# PinHeck_Test_Jig.net
KiCad netlist of a schematic drawn in EAGLE
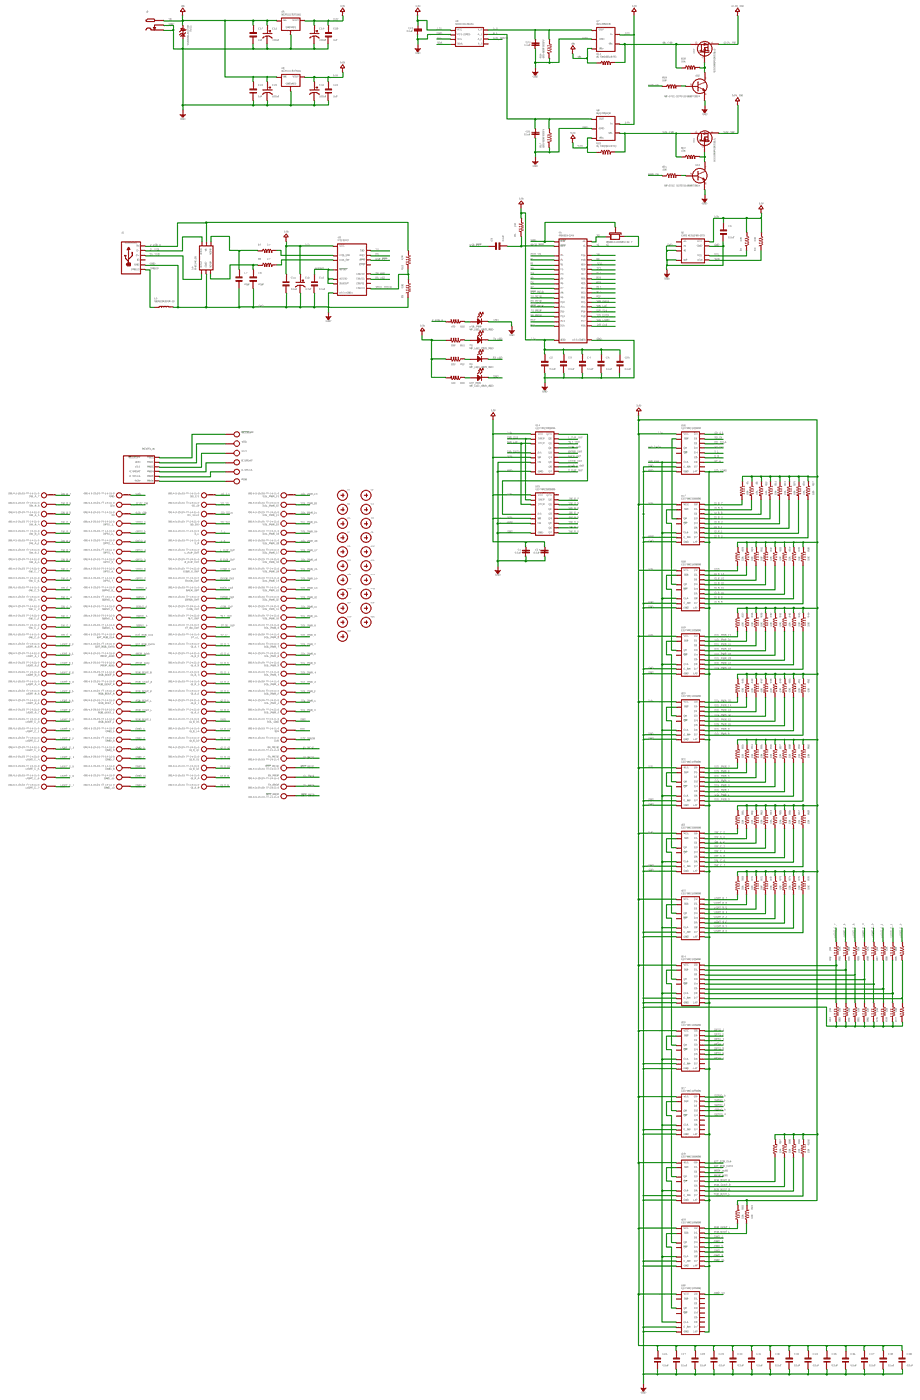
[diagram p0: schematic, sheet 1, overview]
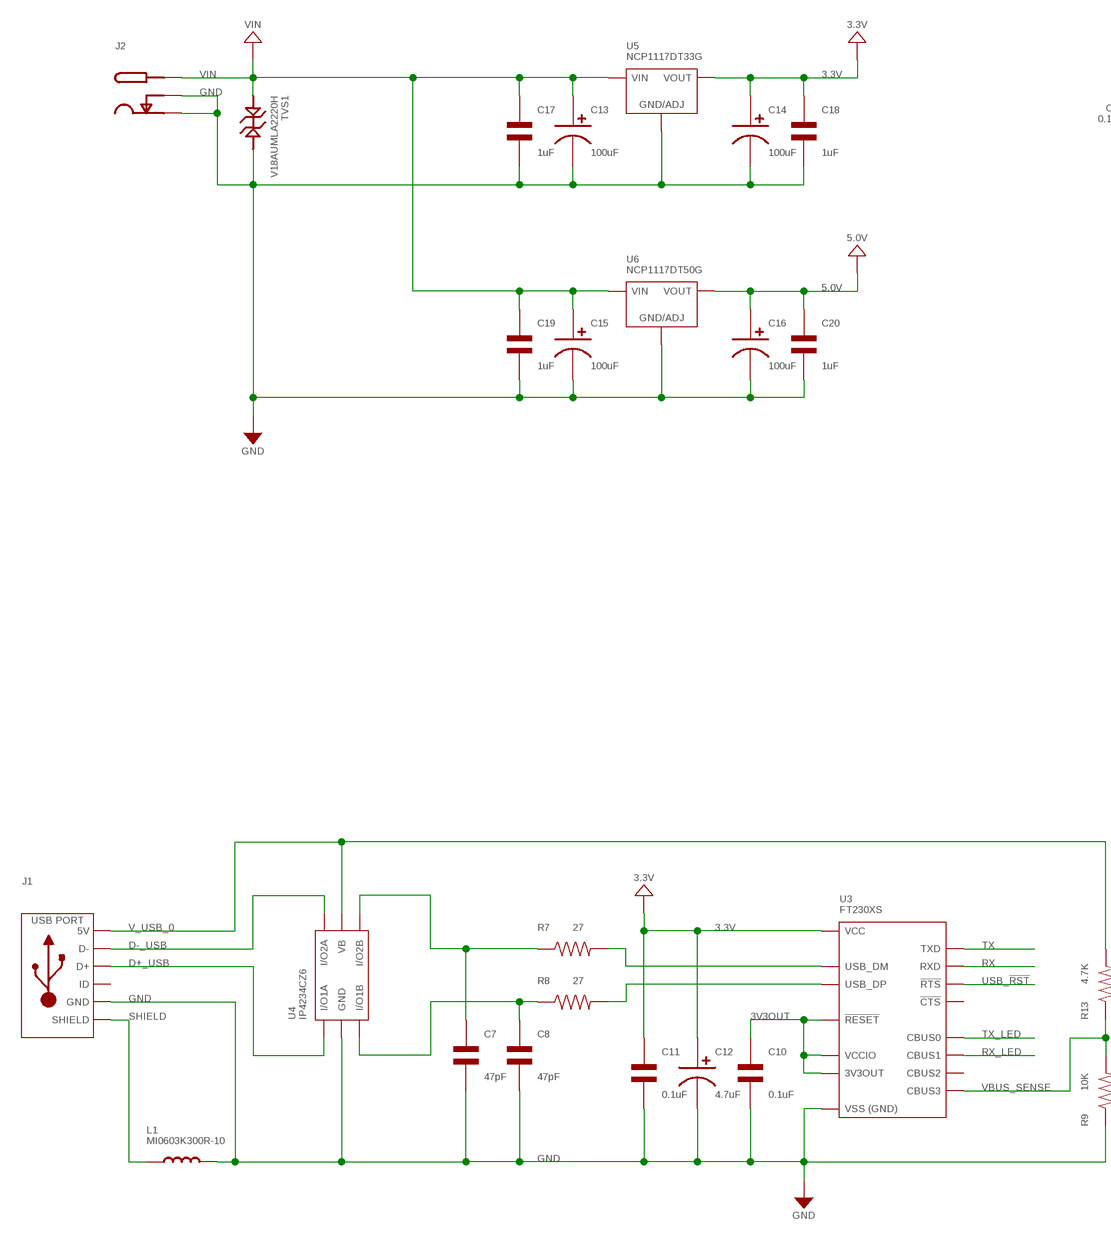
[diagram p1: schematic, sheet 1, part 1 of 7]
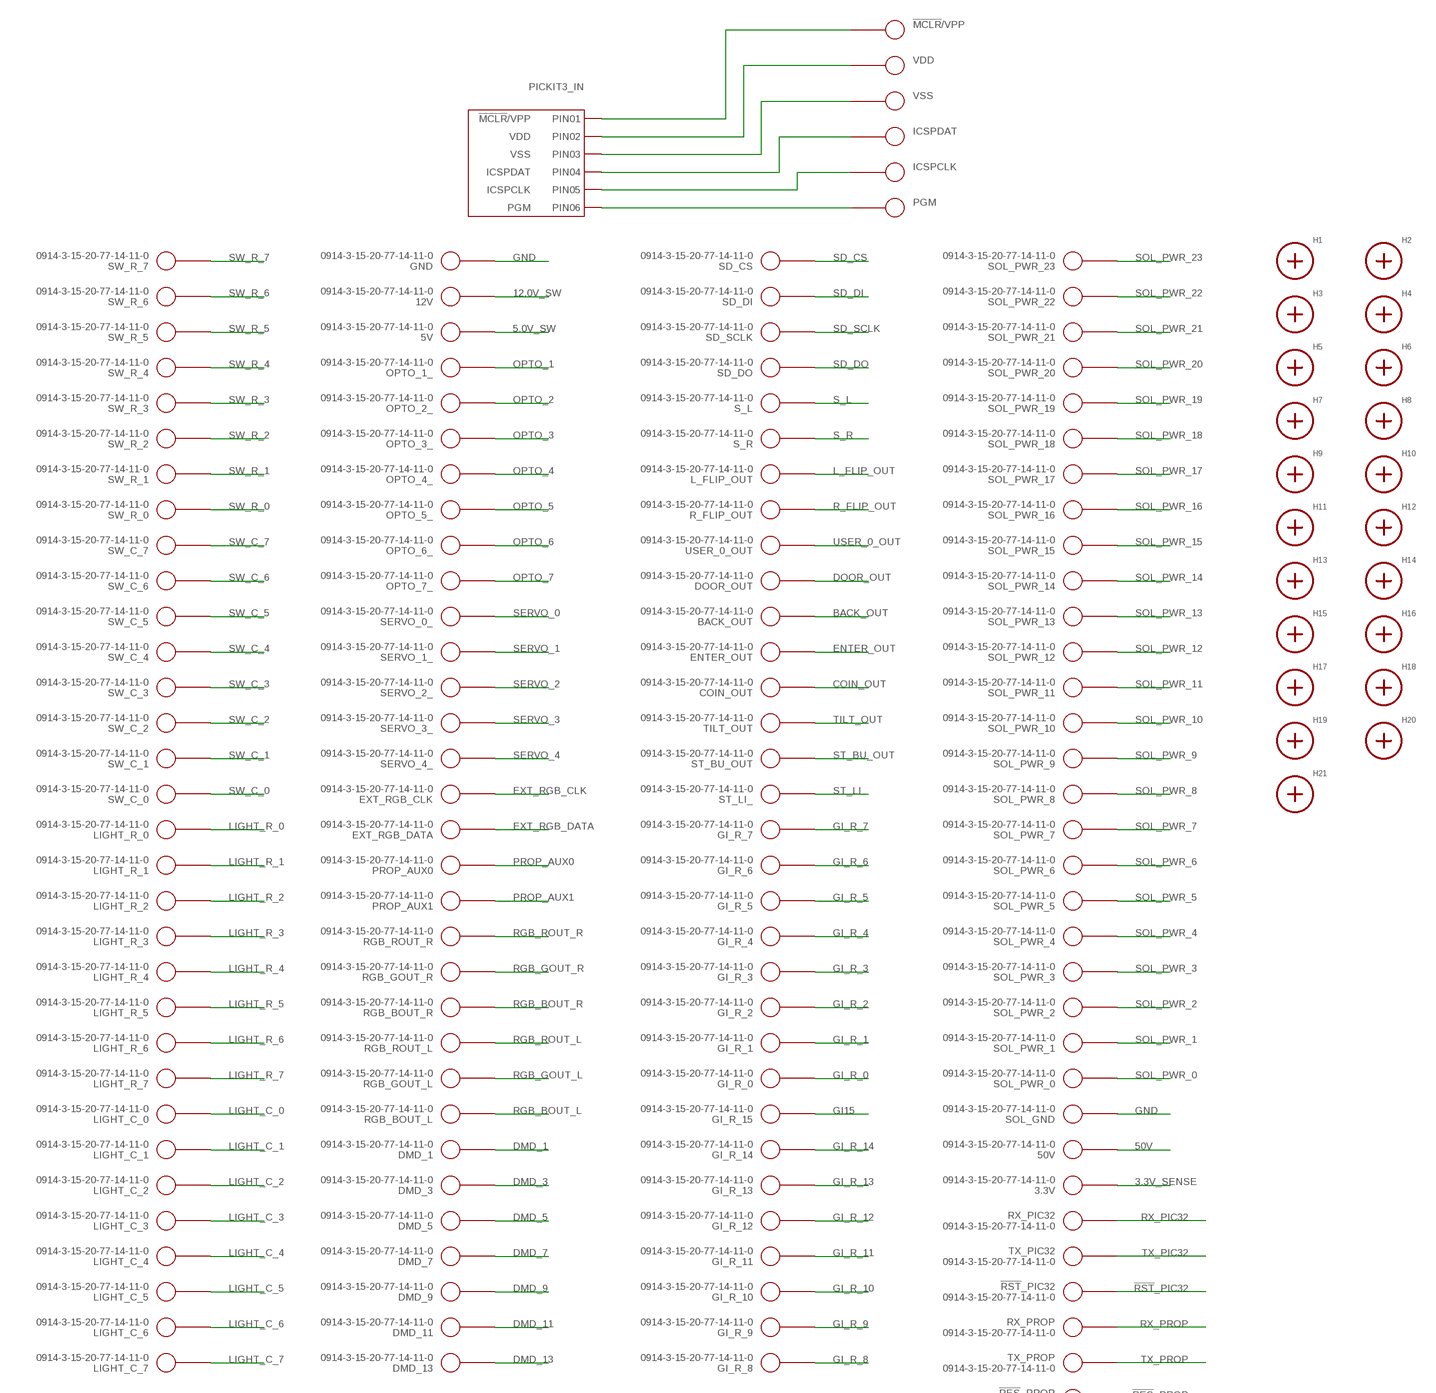
[diagram p2: schematic, sheet 1, part 2 of 7]
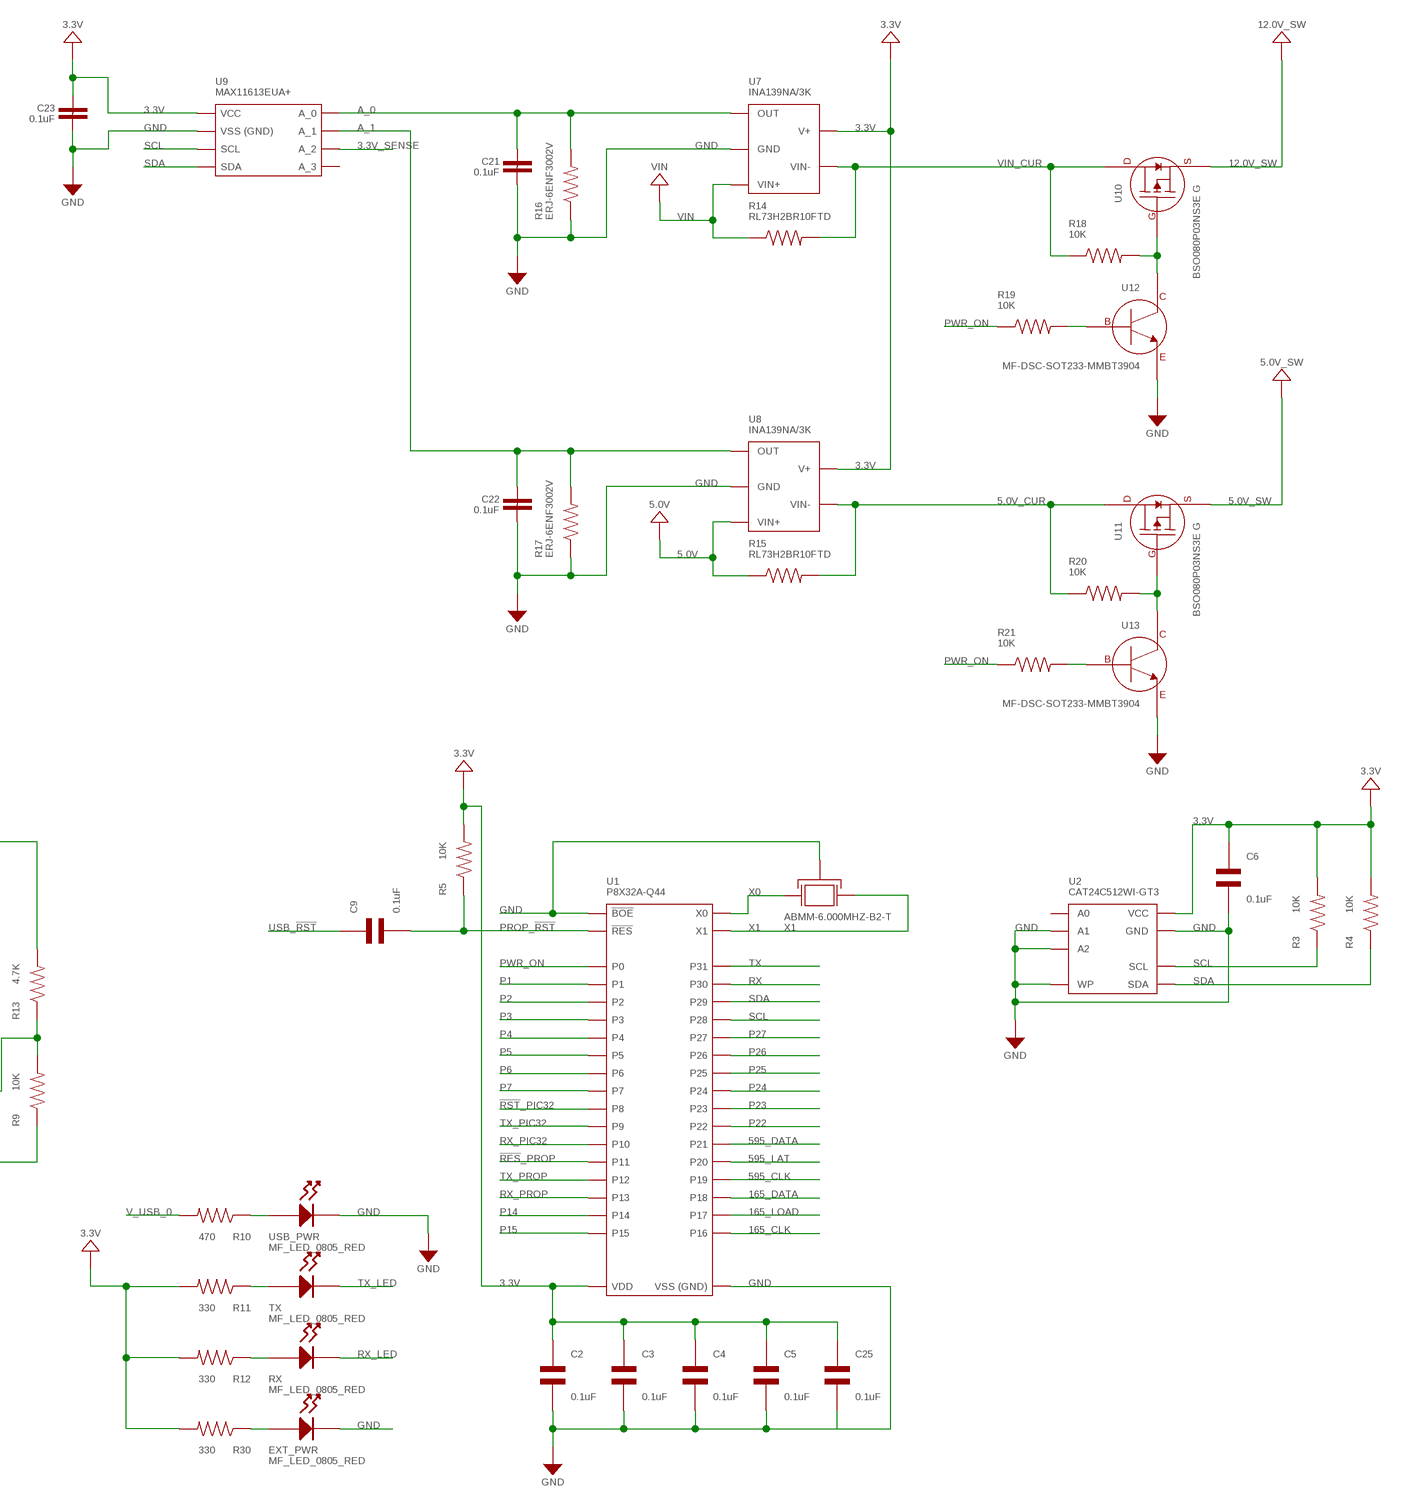
[diagram p3: schematic, sheet 1, part 3 of 7]
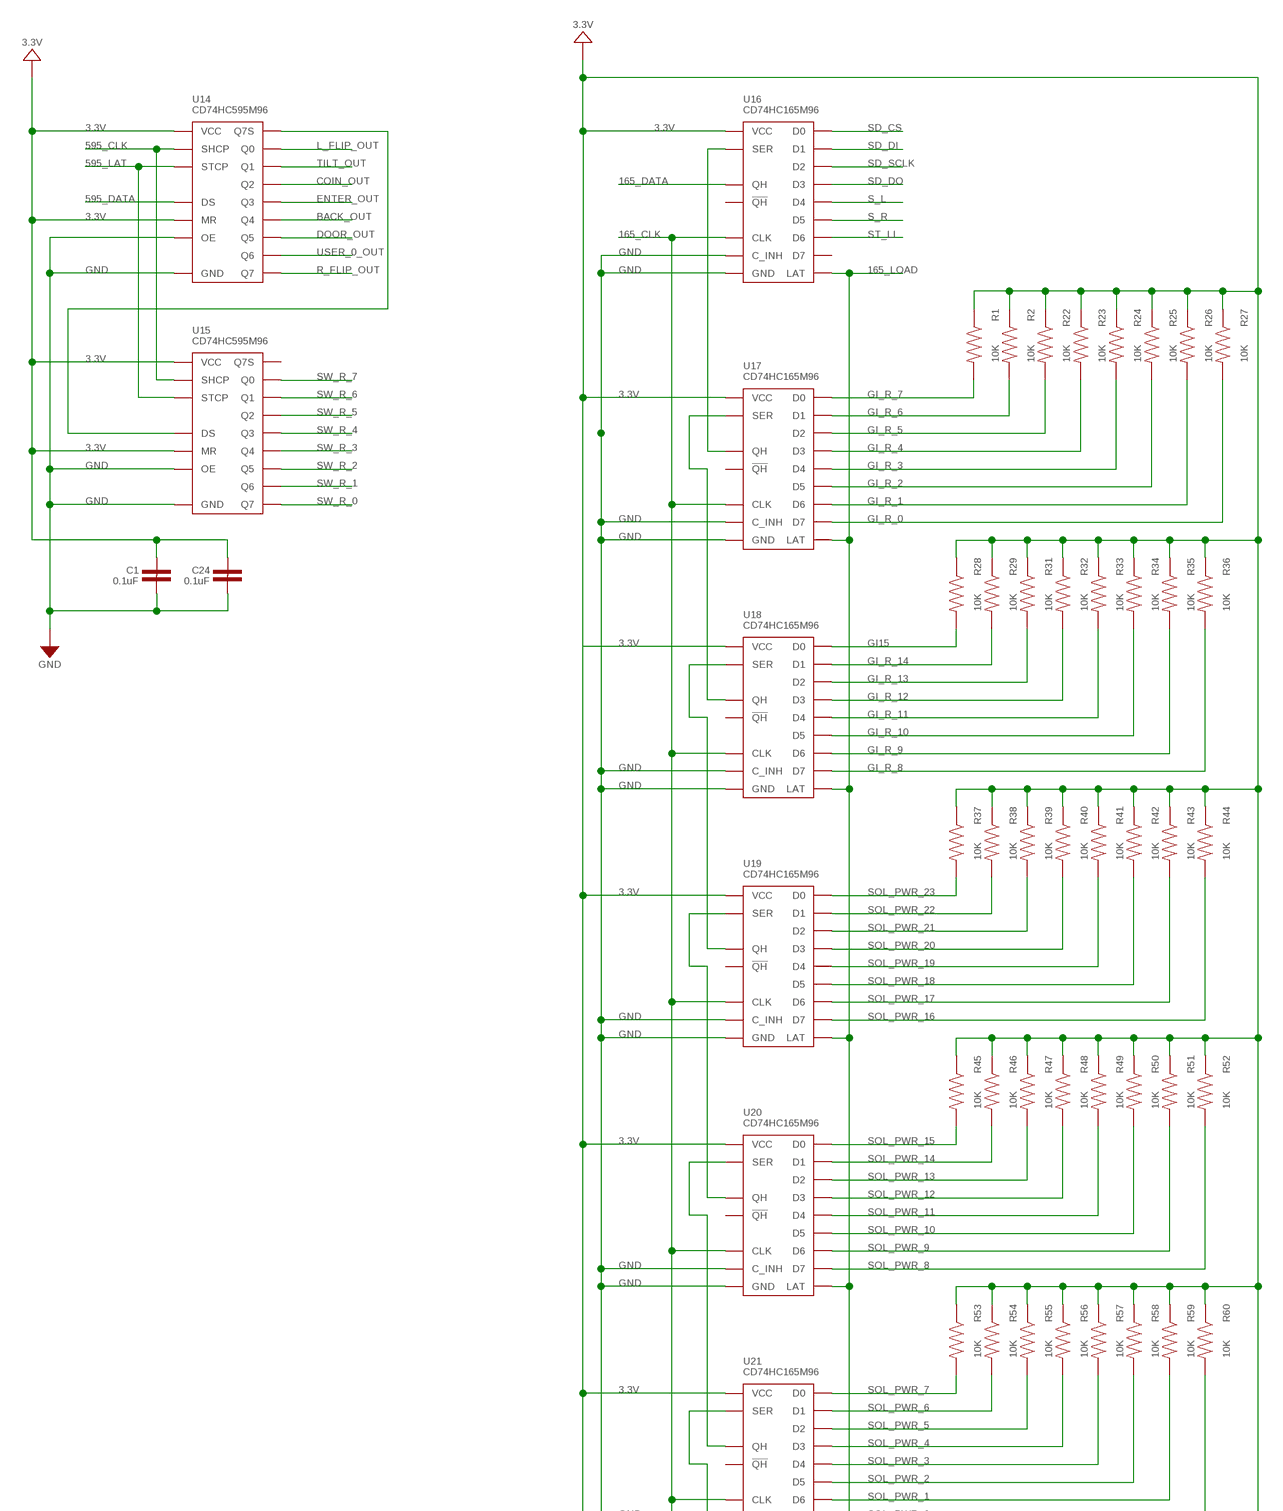
[diagram p4: schematic, sheet 1, part 4 of 7]
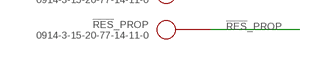
[diagram p5: schematic, sheet 1, part 5 of 7]
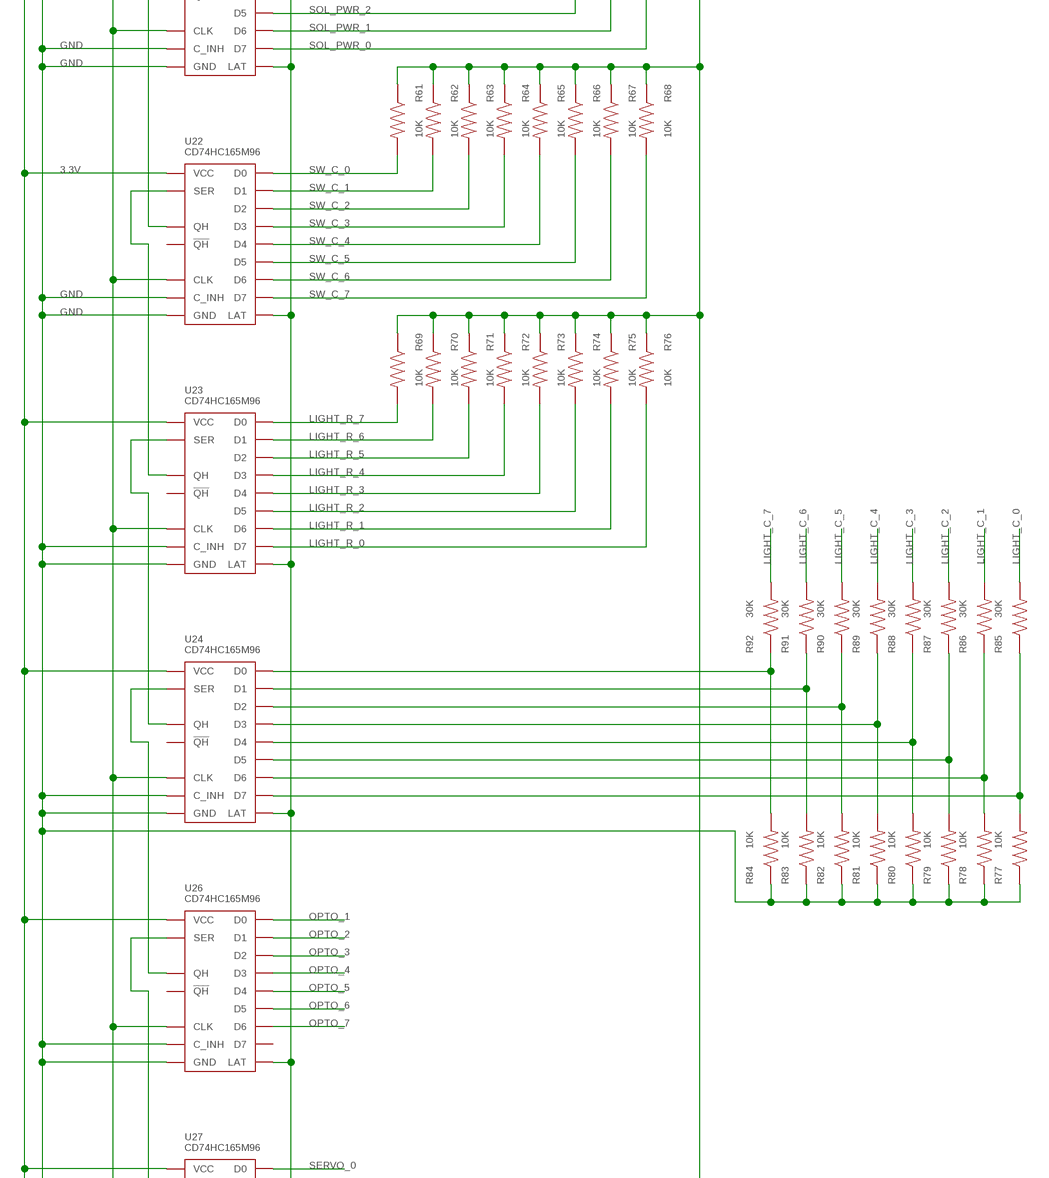
[diagram p6: schematic, sheet 1, part 6 of 7]
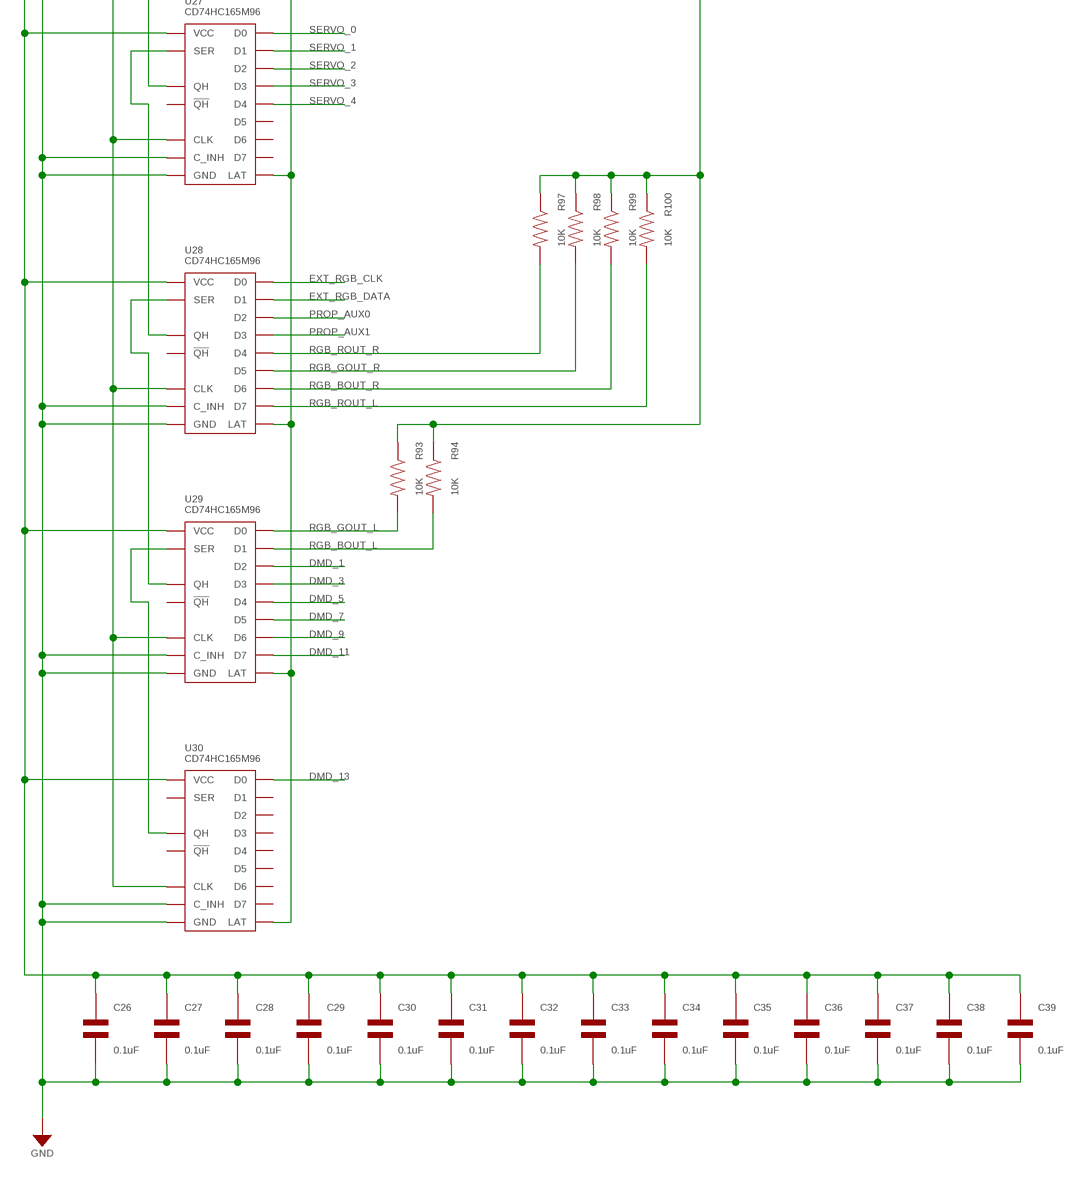
[diagram p7: schematic, sheet 1, part 7 of 7]

(export (version "E")
  (design (tool "Eeschema 10.0.6"))
  (components
    (comp (ref "!MCLR!/VPP")
      (value "POGO_PIN_0914-3-15-20-77-14-11-0")
      (footprint "eagle-import:0914-3-15-20-77-14-11-0")
      (libsource (lib "eagle-import") (part "POGO_PIN_0914-3-15-20-77-14-11-0"))
    )
    (comp (ref "!RES!_PROP")
      (value "0914-3-15-20-77-14-11-0")
      (footprint "eagle-import:0914-3-15-20-77-14-11-0")
      (libsource (lib "eagle-import") (part "POGO_PIN_0914-3-15-20-77-14-11-0"))
    )
    (comp (ref "!RST!_PIC32")
      (value "0914-3-15-20-77-14-11-0")
      (footprint "eagle-import:0914-3-15-20-77-14-11-0")
      (libsource (lib "eagle-import") (part "POGO_PIN_0914-3-15-20-77-14-11-0"))
    )
    (comp (ref "3.3V")
      (value "0914-3-15-20-77-14-11-0")
      (footprint "eagle-import:0914-3-15-20-77-14-11-0")
      (libsource (lib "eagle-import") (part "POGO_PIN_0914-3-15-20-77-14-11-0"))
    )
    (comp (ref "5V")
      (value "0914-3-15-20-77-14-11-0")
      (footprint "eagle-import:0914-3-15-20-77-14-11-0")
      (libsource (lib "eagle-import") (part "POGO_PIN_0914-3-15-20-77-14-11-0"))
    )
    (comp (ref "12V")
      (value "0914-3-15-20-77-14-11-0")
      (footprint "eagle-import:0914-3-15-20-77-14-11-0")
      (libsource (lib "eagle-import") (part "POGO_PIN_0914-3-15-20-77-14-11-0"))
    )
    (comp (ref "50V")
      (value "0914-3-15-20-77-14-11-0")
      (footprint "eagle-import:0914-3-15-20-77-14-11-0")
      (libsource (lib "eagle-import") (part "POGO_PIN_0914-3-15-20-77-14-11-0"))
    )
    (comp (ref "BACK_OUT")
      (value "0914-3-15-20-77-14-11-0")
      (footprint "eagle-import:0914-3-15-20-77-14-11-0")
      (libsource (lib "eagle-import") (part "POGO_PIN_0914-3-15-20-77-14-11-0"))
    )
    (comp (ref "C1")
      (value "0.1uF")
      (footprint "eagle-import:0805")
      (libsource (lib "eagle-import") (part "CAPACITOR_NON_POLAR_0805"))
    )
    (comp (ref "C2")
      (value "0.1uF")
      (footprint "eagle-import:C0603")
      (libsource (lib "eagle-import") (part "CAPACITOR_NP_0603"))
    )
    (comp (ref "C3")
      (value "0.1uF")
      (footprint "eagle-import:C0603")
      (libsource (lib "eagle-import") (part "CAPACITOR_NP_0603"))
    )
    (comp (ref "C4")
      (value "0.1uF")
      (footprint "eagle-import:C0603")
      (libsource (lib "eagle-import") (part "CAPACITOR_NP_0603"))
    )
    (comp (ref "C5")
      (value "0.1uF")
      (footprint "eagle-import:C0603")
      (libsource (lib "eagle-import") (part "CAPACITOR_NP_0603"))
    )
    (comp (ref "C6")
      (value "0.1uF")
      (footprint "eagle-import:C0603")
      (libsource (lib "eagle-import") (part "CAPACITOR_NP_0603"))
    )
    (comp (ref "C7")
      (value "47pF")
      (footprint "eagle-import:C0603")
      (libsource (lib "eagle-import") (part "CAPACITOR_NP_0603"))
    )
    (comp (ref "C8")
      (value "47pF")
      (footprint "eagle-import:C0603")
      (libsource (lib "eagle-import") (part "CAPACITOR_NP_0603"))
    )
    (comp (ref "C9")
      (value "0.1uF")
      (footprint "eagle-import:C0603")
      (libsource (lib "eagle-import") (part "CAPACITOR_NP_0603"))
    )
    (comp (ref "C10")
      (value "0.1uF")
      (footprint "eagle-import:C0603")
      (libsource (lib "eagle-import") (part "CAPACITOR_NP_0603"))
    )
    (comp (ref "C11")
      (value "0.1uF")
      (footprint "eagle-import:C0603")
      (libsource (lib "eagle-import") (part "CAPACITOR_NP_0603"))
    )
    (comp (ref "C12")
      (value "4.7uF")
      (footprint "eagle-import:CP4MM")
      (libsource (lib "eagle-import") (part "CAPACITOR_P_4MM"))
    )
    (comp (ref "C13")
      (value "100uF")
      (footprint "eagle-import:CP6.3MM")
      (libsource (lib "eagle-import") (part "CAPACITOR_P_6.3MM"))
    )
    (comp (ref "C14")
      (value "100uF")
      (footprint "eagle-import:CP6.3MM")
      (libsource (lib "eagle-import") (part "CAPACITOR_P_6.3MM"))
    )
    (comp (ref "C15")
      (value "100uF")
      (footprint "eagle-import:CP6.3MM")
      (libsource (lib "eagle-import") (part "CAPACITOR_P_6.3MM"))
    )
    (comp (ref "C16")
      (value "100uF")
      (footprint "eagle-import:CP6.3MM")
      (libsource (lib "eagle-import") (part "CAPACITOR_P_6.3MM"))
    )
    (comp (ref "C17")
      (value "1uF")
      (footprint "eagle-import:C0805")
      (libsource (lib "eagle-import") (part "CAPACITOR_NP_0805"))
    )
    (comp (ref "C18")
      (value "1uF")
      (footprint "eagle-import:C0805")
      (libsource (lib "eagle-import") (part "CAPACITOR_NP_0805"))
    )
    (comp (ref "C19")
      (value "1uF")
      (footprint "eagle-import:C0805")
      (libsource (lib "eagle-import") (part "CAPACITOR_NP_0805"))
    )
    (comp (ref "C20")
      (value "1uF")
      (footprint "eagle-import:C0805")
      (libsource (lib "eagle-import") (part "CAPACITOR_NP_0805"))
    )
    (comp (ref "C21")
      (value "0.1uF")
      (footprint "eagle-import:0805")
      (libsource (lib "eagle-import") (part "CAPACITOR_NON_POLAR_0805"))
    )
    (comp (ref "C22")
      (value "0.1uF")
      (footprint "eagle-import:0805")
      (libsource (lib "eagle-import") (part "CAPACITOR_NON_POLAR_0805"))
    )
    (comp (ref "C23")
      (value "0.1uF")
      (footprint "eagle-import:0805")
      (libsource (lib "eagle-import") (part "CAPACITOR_NON_POLAR_0805"))
    )
    (comp (ref "C24")
      (value "0.1uF")
      (footprint "eagle-import:0805")
      (libsource (lib "eagle-import") (part "CAPACITOR_NON_POLAR_0805"))
    )
    (comp (ref "C25")
      (value "0.1uF")
      (footprint "eagle-import:C0603")
      (libsource (lib "eagle-import") (part "CAPACITOR_NP_0603"))
    )
    (comp (ref "C26")
      (value "0.1uF")
      (footprint "eagle-import:C0603")
      (libsource (lib "eagle-import") (part "CAPACITOR_NP_0603"))
    )
    (comp (ref "C27")
      (value "0.1uF")
      (footprint "eagle-import:C0603")
      (libsource (lib "eagle-import") (part "CAPACITOR_NP_0603"))
    )
    (comp (ref "C28")
      (value "0.1uF")
      (footprint "eagle-import:C0603")
      (libsource (lib "eagle-import") (part "CAPACITOR_NP_0603"))
    )
    (comp (ref "C29")
      (value "0.1uF")
      (footprint "eagle-import:C0603")
      (libsource (lib "eagle-import") (part "CAPACITOR_NP_0603"))
    )
    (comp (ref "C30")
      (value "0.1uF")
      (footprint "eagle-import:C0603")
      (libsource (lib "eagle-import") (part "CAPACITOR_NP_0603"))
    )
    (comp (ref "C31")
      (value "0.1uF")
      (footprint "eagle-import:C0603")
      (libsource (lib "eagle-import") (part "CAPACITOR_NP_0603"))
    )
    (comp (ref "C32")
      (value "0.1uF")
      (footprint "eagle-import:C0603")
      (libsource (lib "eagle-import") (part "CAPACITOR_NP_0603"))
    )
    (comp (ref "C33")
      (value "0.1uF")
      (footprint "eagle-import:C0603")
      (libsource (lib "eagle-import") (part "CAPACITOR_NP_0603"))
    )
    (comp (ref "C34")
      (value "0.1uF")
      (footprint "eagle-import:C0603")
      (libsource (lib "eagle-import") (part "CAPACITOR_NP_0603"))
    )
    (comp (ref "C35")
      (value "0.1uF")
      (footprint "eagle-import:C0603")
      (libsource (lib "eagle-import") (part "CAPACITOR_NP_0603"))
    )
    (comp (ref "C36")
      (value "0.1uF")
      (footprint "eagle-import:C0603")
      (libsource (lib "eagle-import") (part "CAPACITOR_NP_0603"))
    )
    (comp (ref "C37")
      (value "0.1uF")
      (footprint "eagle-import:C0603")
      (libsource (lib "eagle-import") (part "CAPACITOR_NP_0603"))
    )
    (comp (ref "C38")
      (value "0.1uF")
      (footprint "eagle-import:C0603")
      (libsource (lib "eagle-import") (part "CAPACITOR_NP_0603"))
    )
    (comp (ref "C39")
      (value "0.1uF")
      (footprint "eagle-import:C0603")
      (libsource (lib "eagle-import") (part "CAPACITOR_NP_0603"))
    )
    (comp (ref "COIN_OUT")
      (value "0914-3-15-20-77-14-11-0")
      (footprint "eagle-import:0914-3-15-20-77-14-11-0")
      (libsource (lib "eagle-import") (part "POGO_PIN_0914-3-15-20-77-14-11-0"))
    )
    (comp (ref "DMD_1")
      (value "0914-3-15-20-77-14-11-0")
      (footprint "eagle-import:0914-3-15-20-77-14-11-0")
      (libsource (lib "eagle-import") (part "POGO_PIN_0914-3-15-20-77-14-11-0"))
    )
    (comp (ref "DMD_3")
      (value "0914-3-15-20-77-14-11-0")
      (footprint "eagle-import:0914-3-15-20-77-14-11-0")
      (libsource (lib "eagle-import") (part "POGO_PIN_0914-3-15-20-77-14-11-0"))
    )
    (comp (ref "DMD_5")
      (value "0914-3-15-20-77-14-11-0")
      (footprint "eagle-import:0914-3-15-20-77-14-11-0")
      (libsource (lib "eagle-import") (part "POGO_PIN_0914-3-15-20-77-14-11-0"))
    )
    (comp (ref "DMD_7")
      (value "0914-3-15-20-77-14-11-0")
      (footprint "eagle-import:0914-3-15-20-77-14-11-0")
      (libsource (lib "eagle-import") (part "POGO_PIN_0914-3-15-20-77-14-11-0"))
    )
    (comp (ref "DMD_9")
      (value "0914-3-15-20-77-14-11-0")
      (footprint "eagle-import:0914-3-15-20-77-14-11-0")
      (libsource (lib "eagle-import") (part "POGO_PIN_0914-3-15-20-77-14-11-0"))
    )
    (comp (ref "DMD_11")
      (value "0914-3-15-20-77-14-11-0")
      (footprint "eagle-import:0914-3-15-20-77-14-11-0")
      (libsource (lib "eagle-import") (part "POGO_PIN_0914-3-15-20-77-14-11-0"))
    )
    (comp (ref "DMD_13")
      (value "0914-3-15-20-77-14-11-0")
      (footprint "eagle-import:0914-3-15-20-77-14-11-0")
      (libsource (lib "eagle-import") (part "POGO_PIN_0914-3-15-20-77-14-11-0"))
    )
    (comp (ref "DOOR_OUT")
      (value "0914-3-15-20-77-14-11-0")
      (footprint "eagle-import:0914-3-15-20-77-14-11-0")
      (libsource (lib "eagle-import") (part "POGO_PIN_0914-3-15-20-77-14-11-0"))
    )
    (comp (ref "ENTER_OUT")
      (value "0914-3-15-20-77-14-11-0")
      (footprint "eagle-import:0914-3-15-20-77-14-11-0")
      (libsource (lib "eagle-import") (part "POGO_PIN_0914-3-15-20-77-14-11-0"))
    )
    (comp (ref "EXT_PWR")
      (value "MF_LED_0805_RED")
      (footprint "eagle-import:LED0805")
      (libsource (lib "eagle-import") (part "LED_SINGLE_0805"))
    )
    (comp (ref "EXT_RGB_CLK")
      (value "0914-3-15-20-77-14-11-0")
      (footprint "eagle-import:0914-3-15-20-77-14-11-0")
      (libsource (lib "eagle-import") (part "POGO_PIN_0914-3-15-20-77-14-11-0"))
    )
    (comp (ref "EXT_RGB_DATA")
      (value "0914-3-15-20-77-14-11-0")
      (footprint "eagle-import:0914-3-15-20-77-14-11-0")
      (libsource (lib "eagle-import") (part "POGO_PIN_0914-3-15-20-77-14-11-0"))
    )
    (comp (ref "GI_R_0")
      (value "0914-3-15-20-77-14-11-0")
      (footprint "eagle-import:0914-3-15-20-77-14-11-0")
      (libsource (lib "eagle-import") (part "POGO_PIN_0914-3-15-20-77-14-11-0"))
    )
    (comp (ref "GI_R_1")
      (value "0914-3-15-20-77-14-11-0")
      (footprint "eagle-import:0914-3-15-20-77-14-11-0")
      (libsource (lib "eagle-import") (part "POGO_PIN_0914-3-15-20-77-14-11-0"))
    )
    (comp (ref "GI_R_2")
      (value "0914-3-15-20-77-14-11-0")
      (footprint "eagle-import:0914-3-15-20-77-14-11-0")
      (libsource (lib "eagle-import") (part "POGO_PIN_0914-3-15-20-77-14-11-0"))
    )
    (comp (ref "GI_R_3")
      (value "0914-3-15-20-77-14-11-0")
      (footprint "eagle-import:0914-3-15-20-77-14-11-0")
      (libsource (lib "eagle-import") (part "POGO_PIN_0914-3-15-20-77-14-11-0"))
    )
    (comp (ref "GI_R_4")
      (value "0914-3-15-20-77-14-11-0")
      (footprint "eagle-import:0914-3-15-20-77-14-11-0")
      (libsource (lib "eagle-import") (part "POGO_PIN_0914-3-15-20-77-14-11-0"))
    )
    (comp (ref "GI_R_5")
      (value "0914-3-15-20-77-14-11-0")
      (footprint "eagle-import:0914-3-15-20-77-14-11-0")
      (libsource (lib "eagle-import") (part "POGO_PIN_0914-3-15-20-77-14-11-0"))
    )
    (comp (ref "GI_R_6")
      (value "0914-3-15-20-77-14-11-0")
      (footprint "eagle-import:0914-3-15-20-77-14-11-0")
      (libsource (lib "eagle-import") (part "POGO_PIN_0914-3-15-20-77-14-11-0"))
    )
    (comp (ref "GI_R_7")
      (value "0914-3-15-20-77-14-11-0")
      (footprint "eagle-import:0914-3-15-20-77-14-11-0")
      (libsource (lib "eagle-import") (part "POGO_PIN_0914-3-15-20-77-14-11-0"))
    )
    (comp (ref "GI_R_8")
      (value "0914-3-15-20-77-14-11-0")
      (footprint "eagle-import:0914-3-15-20-77-14-11-0")
      (libsource (lib "eagle-import") (part "POGO_PIN_0914-3-15-20-77-14-11-0"))
    )
    (comp (ref "GI_R_9")
      (value "0914-3-15-20-77-14-11-0")
      (footprint "eagle-import:0914-3-15-20-77-14-11-0")
      (libsource (lib "eagle-import") (part "POGO_PIN_0914-3-15-20-77-14-11-0"))
    )
    (comp (ref "GI_R_10")
      (value "0914-3-15-20-77-14-11-0")
      (footprint "eagle-import:0914-3-15-20-77-14-11-0")
      (libsource (lib "eagle-import") (part "POGO_PIN_0914-3-15-20-77-14-11-0"))
    )
    (comp (ref "GI_R_11")
      (value "0914-3-15-20-77-14-11-0")
      (footprint "eagle-import:0914-3-15-20-77-14-11-0")
      (libsource (lib "eagle-import") (part "POGO_PIN_0914-3-15-20-77-14-11-0"))
    )
    (comp (ref "GI_R_12")
      (value "0914-3-15-20-77-14-11-0")
      (footprint "eagle-import:0914-3-15-20-77-14-11-0")
      (libsource (lib "eagle-import") (part "POGO_PIN_0914-3-15-20-77-14-11-0"))
    )
    (comp (ref "GI_R_13")
      (value "0914-3-15-20-77-14-11-0")
      (footprint "eagle-import:0914-3-15-20-77-14-11-0")
      (libsource (lib "eagle-import") (part "POGO_PIN_0914-3-15-20-77-14-11-0"))
    )
    (comp (ref "GI_R_14")
      (value "0914-3-15-20-77-14-11-0")
      (footprint "eagle-import:0914-3-15-20-77-14-11-0")
      (libsource (lib "eagle-import") (part "POGO_PIN_0914-3-15-20-77-14-11-0"))
    )
    (comp (ref "GI_R_15")
      (value "0914-3-15-20-77-14-11-0")
      (footprint "eagle-import:0914-3-15-20-77-14-11-0")
      (libsource (lib "eagle-import") (part "POGO_PIN_0914-3-15-20-77-14-11-0"))
    )
    (comp (ref "GND")
      (value "0914-3-15-20-77-14-11-0")
      (footprint "eagle-import:0914-3-15-20-77-14-11-0")
      (libsource (lib "eagle-import") (part "POGO_PIN_0914-3-15-20-77-14-11-0"))
    )
    (comp (ref "H1")
      (value "2263-2")
      (footprint "eagle-import:MOUNT_HOLE_120MIL")
      (libsource (lib "eagle-import") (part "MOUNT_HOLE120MIL"))
    )
    (comp (ref "H2")
      (value "2263-2")
      (footprint "eagle-import:MOUNT_HOLE_120MIL")
      (libsource (lib "eagle-import") (part "MOUNT_HOLE120MIL"))
    )
    (comp (ref "H3")
      (value "2263-2")
      (footprint "eagle-import:MOUNT_HOLE_120MIL")
      (libsource (lib "eagle-import") (part "MOUNT_HOLE120MIL"))
    )
    (comp (ref "H4")
      (value "2263-2")
      (footprint "eagle-import:MOUNT_HOLE_120MIL")
      (libsource (lib "eagle-import") (part "MOUNT_HOLE120MIL"))
    )
    (comp (ref "H5")
      (value "2263-2")
      (footprint "eagle-import:MOUNT_HOLE_120MIL")
      (libsource (lib "eagle-import") (part "MOUNT_HOLE120MIL"))
    )
    (comp (ref "H6")
      (value "2263-2")
      (footprint "eagle-import:MOUNT_HOLE_120MIL")
      (libsource (lib "eagle-import") (part "MOUNT_HOLE120MIL"))
    )
    (comp (ref "H7")
      (value "2263-2")
      (footprint "eagle-import:MOUNT_HOLE_120MIL")
      (libsource (lib "eagle-import") (part "MOUNT_HOLE120MIL"))
    )
    (comp (ref "H8")
      (value "2263-2")
      (footprint "eagle-import:MOUNT_HOLE_120MIL")
      (libsource (lib "eagle-import") (part "MOUNT_HOLE120MIL"))
    )
    (comp (ref "H9")
      (value "2263-2")
      (footprint "eagle-import:MOUNT_HOLE_120MIL")
      (libsource (lib "eagle-import") (part "MOUNT_HOLE120MIL"))
    )
    (comp (ref "H10")
      (value "2263-2")
      (footprint "eagle-import:MOUNT_HOLE_120MIL")
      (libsource (lib "eagle-import") (part "MOUNT_HOLE120MIL"))
    )
    (comp (ref "H11")
      (value "2263-2")
      (footprint "eagle-import:MOUNT_HOLE_120MIL")
      (libsource (lib "eagle-import") (part "MOUNT_HOLE120MIL"))
    )
    (comp (ref "H12")
      (value "2263-2")
      (footprint "eagle-import:MOUNT_HOLE_120MIL")
      (libsource (lib "eagle-import") (part "MOUNT_HOLE120MIL"))
    )
    (comp (ref "H13")
      (value "2263-2")
      (footprint "eagle-import:MOUNT_HOLE_120MIL")
      (libsource (lib "eagle-import") (part "MOUNT_HOLE120MIL"))
    )
    (comp (ref "H14")
      (value "2263-2")
      (footprint "eagle-import:MOUNT_HOLE_120MIL")
      (libsource (lib "eagle-import") (part "MOUNT_HOLE120MIL"))
    )
    (comp (ref "H15")
      (value "2263-2")
      (footprint "eagle-import:MOUNT_HOLE_120MIL")
      (libsource (lib "eagle-import") (part "MOUNT_HOLE120MIL"))
    )
    (comp (ref "H16")
      (value "2263-2")
      (footprint "eagle-import:MOUNT_HOLE_120MIL")
      (libsource (lib "eagle-import") (part "MOUNT_HOLE120MIL"))
    )
    (comp (ref "H17")
      (value "2263-2")
      (footprint "eagle-import:MOUNT_HOLE_120MIL")
      (libsource (lib "eagle-import") (part "MOUNT_HOLE120MIL"))
    )
    (comp (ref "H18")
      (value "2263-2")
      (footprint "eagle-import:MOUNT_HOLE_120MIL")
      (libsource (lib "eagle-import") (part "MOUNT_HOLE120MIL"))
    )
    (comp (ref "H19")
      (value "2263-2")
      (footprint "eagle-import:MOUNT_HOLE_120MIL")
      (libsource (lib "eagle-import") (part "MOUNT_HOLE120MIL"))
    )
    (comp (ref "H20")
      (value "2263-2")
      (footprint "eagle-import:MOUNT_HOLE_120MIL")
      (libsource (lib "eagle-import") (part "MOUNT_HOLE120MIL"))
    )
    (comp (ref "H21")
      (value "2263-2")
      (footprint "eagle-import:MOUNT_HOLE_120MIL")
      (libsource (lib "eagle-import") (part "MOUNT_HOLE120MIL"))
    )
    (comp (ref "ICSPCLK")
      (value "POGO_PIN_0914-3-15-20-77-14-11-0")
      (footprint "eagle-import:0914-3-15-20-77-14-11-0")
      (libsource (lib "eagle-import") (part "POGO_PIN_0914-3-15-20-77-14-11-0"))
    )
    (comp (ref "ICSPDAT")
      (value "POGO_PIN_0914-3-15-20-77-14-11-0")
      (footprint "eagle-import:0914-3-15-20-77-14-11-0")
      (libsource (lib "eagle-import") (part "POGO_PIN_0914-3-15-20-77-14-11-0"))
    )
    (comp (ref "J1")
      (value "USB_MICRO_RIGHT")
      (footprint "eagle-import:MICROUSB-RIGHT")
      (libsource (lib "eagle-import") (part "USB_MICRO_RIGHT"))
    )
    (comp (ref "J2")
      (value "DC_PWR_JACK_2.5MM_RIGHT")
      (footprint "eagle-import:DC_PWR_JACK")
      (libsource (lib "eagle-import") (part "DC_PWR_JACK_2.5MM_RIGHT"))
    )
    (comp (ref "L1")
      (value "MI0603K300R-10")
      (footprint "eagle-import:L0603")
      (libsource (lib "eagle-import") (part "INDUCTOR_0603"))
    )
    (comp (ref "LIGHT_C_0")
      (value "0914-3-15-20-77-14-11-0")
      (footprint "eagle-import:0914-3-15-20-77-14-11-0")
      (libsource (lib "eagle-import") (part "POGO_PIN_0914-3-15-20-77-14-11-0"))
    )
    (comp (ref "LIGHT_C_1")
      (value "0914-3-15-20-77-14-11-0")
      (footprint "eagle-import:0914-3-15-20-77-14-11-0")
      (libsource (lib "eagle-import") (part "POGO_PIN_0914-3-15-20-77-14-11-0"))
    )
    (comp (ref "LIGHT_C_2")
      (value "0914-3-15-20-77-14-11-0")
      (footprint "eagle-import:0914-3-15-20-77-14-11-0")
      (libsource (lib "eagle-import") (part "POGO_PIN_0914-3-15-20-77-14-11-0"))
    )
    (comp (ref "LIGHT_C_3")
      (value "0914-3-15-20-77-14-11-0")
      (footprint "eagle-import:0914-3-15-20-77-14-11-0")
      (libsource (lib "eagle-import") (part "POGO_PIN_0914-3-15-20-77-14-11-0"))
    )
    (comp (ref "LIGHT_C_4")
      (value "0914-3-15-20-77-14-11-0")
      (footprint "eagle-import:0914-3-15-20-77-14-11-0")
      (libsource (lib "eagle-import") (part "POGO_PIN_0914-3-15-20-77-14-11-0"))
    )
    (comp (ref "LIGHT_C_5")
      (value "0914-3-15-20-77-14-11-0")
      (footprint "eagle-import:0914-3-15-20-77-14-11-0")
      (libsource (lib "eagle-import") (part "POGO_PIN_0914-3-15-20-77-14-11-0"))
    )
    (comp (ref "LIGHT_C_6")
      (value "0914-3-15-20-77-14-11-0")
      (footprint "eagle-import:0914-3-15-20-77-14-11-0")
      (libsource (lib "eagle-import") (part "POGO_PIN_0914-3-15-20-77-14-11-0"))
    )
    (comp (ref "LIGHT_C_7")
      (value "0914-3-15-20-77-14-11-0")
      (footprint "eagle-import:0914-3-15-20-77-14-11-0")
      (libsource (lib "eagle-import") (part "POGO_PIN_0914-3-15-20-77-14-11-0"))
    )
    (comp (ref "LIGHT_R_0")
      (value "0914-3-15-20-77-14-11-0")
      (footprint "eagle-import:0914-3-15-20-77-14-11-0")
      (libsource (lib "eagle-import") (part "POGO_PIN_0914-3-15-20-77-14-11-0"))
    )
    (comp (ref "LIGHT_R_1")
      (value "0914-3-15-20-77-14-11-0")
      (footprint "eagle-import:0914-3-15-20-77-14-11-0")
      (libsource (lib "eagle-import") (part "POGO_PIN_0914-3-15-20-77-14-11-0"))
    )
    (comp (ref "LIGHT_R_2")
      (value "0914-3-15-20-77-14-11-0")
      (footprint "eagle-import:0914-3-15-20-77-14-11-0")
      (libsource (lib "eagle-import") (part "POGO_PIN_0914-3-15-20-77-14-11-0"))
    )
    (comp (ref "LIGHT_R_3")
      (value "0914-3-15-20-77-14-11-0")
      (footprint "eagle-import:0914-3-15-20-77-14-11-0")
      (libsource (lib "eagle-import") (part "POGO_PIN_0914-3-15-20-77-14-11-0"))
    )
    (comp (ref "LIGHT_R_4")
      (value "0914-3-15-20-77-14-11-0")
      (footprint "eagle-import:0914-3-15-20-77-14-11-0")
      (libsource (lib "eagle-import") (part "POGO_PIN_0914-3-15-20-77-14-11-0"))
    )
    (comp (ref "LIGHT_R_5")
      (value "0914-3-15-20-77-14-11-0")
      (footprint "eagle-import:0914-3-15-20-77-14-11-0")
      (libsource (lib "eagle-import") (part "POGO_PIN_0914-3-15-20-77-14-11-0"))
    )
    (comp (ref "LIGHT_R_6")
      (value "0914-3-15-20-77-14-11-0")
      (footprint "eagle-import:0914-3-15-20-77-14-11-0")
      (libsource (lib "eagle-import") (part "POGO_PIN_0914-3-15-20-77-14-11-0"))
    )
    (comp (ref "LIGHT_R_7")
      (value "0914-3-15-20-77-14-11-0")
      (footprint "eagle-import:0914-3-15-20-77-14-11-0")
      (libsource (lib "eagle-import") (part "POGO_PIN_0914-3-15-20-77-14-11-0"))
    )
    (comp (ref "L_FLIP_OUT")
      (value "0914-3-15-20-77-14-11-0")
      (footprint "eagle-import:0914-3-15-20-77-14-11-0")
      (libsource (lib "eagle-import") (part "POGO_PIN_0914-3-15-20-77-14-11-0"))
    )
    (comp (ref "OPTO_1_")
      (value "0914-3-15-20-77-14-11-0")
      (footprint "eagle-import:0914-3-15-20-77-14-11-0")
      (libsource (lib "eagle-import") (part "POGO_PIN_0914-3-15-20-77-14-11-0"))
    )
    (comp (ref "OPTO_2_")
      (value "0914-3-15-20-77-14-11-0")
      (footprint "eagle-import:0914-3-15-20-77-14-11-0")
      (libsource (lib "eagle-import") (part "POGO_PIN_0914-3-15-20-77-14-11-0"))
    )
    (comp (ref "OPTO_3_")
      (value "0914-3-15-20-77-14-11-0")
      (footprint "eagle-import:0914-3-15-20-77-14-11-0")
      (libsource (lib "eagle-import") (part "POGO_PIN_0914-3-15-20-77-14-11-0"))
    )
    (comp (ref "OPTO_4_")
      (value "0914-3-15-20-77-14-11-0")
      (footprint "eagle-import:0914-3-15-20-77-14-11-0")
      (libsource (lib "eagle-import") (part "POGO_PIN_0914-3-15-20-77-14-11-0"))
    )
    (comp (ref "OPTO_5_")
      (value "0914-3-15-20-77-14-11-0")
      (footprint "eagle-import:0914-3-15-20-77-14-11-0")
      (libsource (lib "eagle-import") (part "POGO_PIN_0914-3-15-20-77-14-11-0"))
    )
    (comp (ref "OPTO_6_")
      (value "0914-3-15-20-77-14-11-0")
      (footprint "eagle-import:0914-3-15-20-77-14-11-0")
      (libsource (lib "eagle-import") (part "POGO_PIN_0914-3-15-20-77-14-11-0"))
    )
    (comp (ref "OPTO_7_")
      (value "0914-3-15-20-77-14-11-0")
      (footprint "eagle-import:0914-3-15-20-77-14-11-0")
      (libsource (lib "eagle-import") (part "POGO_PIN_0914-3-15-20-77-14-11-0"))
    )
    (comp (ref "PGM")
      (value "POGO_PIN_0914-3-15-20-77-14-11-0")
      (footprint "eagle-import:0914-3-15-20-77-14-11-0")
      (libsource (lib "eagle-import") (part "POGO_PIN_0914-3-15-20-77-14-11-0"))
    )
    (comp (ref "PICKIT3_IN")
      (value "CON_01X06_2.54MM_PIN_HEADER")
      (footprint "eagle-import:2.54MM_01X06_PIN_HEADER")
      (fields
        (field (name "LABEL01") "!MCLR!/VPP")
        (field (name "LABEL02") "VDD")
        (field (name "LABEL03") "VSS")
        (field (name "LABEL04") "ICSPDAT")
        (field (name "LABEL05") "ICSPCLK")
        (field (name "LABEL06") "PGM")
      )
      (libsource (lib "eagle-import") (part "CON_01X06_2.54MM_PIN_HEADER"))
    )
    (comp (ref "PROP_AUX0")
      (value "0914-3-15-20-77-14-11-0")
      (footprint "eagle-import:0914-3-15-20-77-14-11-0")
      (libsource (lib "eagle-import") (part "POGO_PIN_0914-3-15-20-77-14-11-0"))
    )
    (comp (ref "PROP_AUX1")
      (value "0914-3-15-20-77-14-11-0")
      (footprint "eagle-import:0914-3-15-20-77-14-11-0")
      (libsource (lib "eagle-import") (part "POGO_PIN_0914-3-15-20-77-14-11-0"))
    )
    (comp (ref "R1")
      (value "10K")
      (footprint "eagle-import:R0603")
      (libsource (lib "eagle-import") (part "RESISTOR_0603"))
    )
    (comp (ref "R2")
      (value "10K")
      (footprint "eagle-import:R0603")
      (libsource (lib "eagle-import") (part "RESISTOR_0603"))
    )
    (comp (ref "R3")
      (value "10K")
      (footprint "eagle-import:R0603")
      (libsource (lib "eagle-import") (part "RESISTOR_0603"))
    )
    (comp (ref "R4")
      (value "10K")
      (footprint "eagle-import:R0603")
      (libsource (lib "eagle-import") (part "RESISTOR_0603"))
    )
    (comp (ref "R5")
      (value "10K")
      (footprint "eagle-import:R0603")
      (libsource (lib "eagle-import") (part "RESISTOR_0603"))
    )
    (comp (ref "R7")
      (value "27")
      (footprint "eagle-import:R0603")
      (libsource (lib "eagle-import") (part "RESISTOR_0603"))
    )
    (comp (ref "R8")
      (value "27")
      (footprint "eagle-import:R0603")
      (libsource (lib "eagle-import") (part "RESISTOR_0603"))
    )
    (comp (ref "R9")
      (value "10K")
      (footprint "eagle-import:R0603")
      (libsource (lib "eagle-import") (part "RESISTOR_0603"))
    )
    (comp (ref "R10")
      (value "470")
      (footprint "eagle-import:R0603")
      (libsource (lib "eagle-import") (part "RESISTOR_0603"))
    )
    (comp (ref "R11")
      (value "330")
      (footprint "eagle-import:R0603")
      (libsource (lib "eagle-import") (part "RESISTOR_0603"))
    )
    (comp (ref "R12")
      (value "330")
      (footprint "eagle-import:R0603")
      (libsource (lib "eagle-import") (part "RESISTOR_0603"))
    )
    (comp (ref "R13")
      (value "4.7K")
      (footprint "eagle-import:R0603")
      (libsource (lib "eagle-import") (part "RESISTOR_0603"))
    )
    (comp (ref "R14")
      (value "RL73H2BR10FTD")
      (footprint "eagle-import:1206")
      (libsource (lib "eagle-import") (part "PP_Passives_RESISTOR_1206"))
    )
    (comp (ref "R15")
      (value "RL73H2BR10FTD")
      (footprint "eagle-import:1206")
      (libsource (lib "eagle-import") (part "PP_Passives_RESISTOR_1206"))
    )
    (comp (ref "R16")
      (value "ERJ-6ENF3002V")
      (footprint "eagle-import:0805")
      (libsource (lib "eagle-import") (part "PP_Passives_RESISTOR_0805"))
    )
    (comp (ref "R17")
      (value "ERJ-6ENF3002V")
      (footprint "eagle-import:0805")
      (libsource (lib "eagle-import") (part "PP_Passives_RESISTOR_0805"))
    )
    (comp (ref "R18")
      (value "10K")
      (footprint "eagle-import:0805")
      (libsource (lib "eagle-import") (part "PP_Passives_RESISTOR_0805"))
    )
    (comp (ref "R19")
      (value "10K")
      (footprint "eagle-import:0805")
      (libsource (lib "eagle-import") (part "PP_Passives_RESISTOR_0805"))
    )
    (comp (ref "R20")
      (value "10K")
      (footprint "eagle-import:0805")
      (libsource (lib "eagle-import") (part "PP_Passives_RESISTOR_0805"))
    )
    (comp (ref "R21")
      (value "10K")
      (footprint "eagle-import:0805")
      (libsource (lib "eagle-import") (part "PP_Passives_RESISTOR_0805"))
    )
    (comp (ref "R22")
      (value "10K")
      (footprint "eagle-import:R0603")
      (libsource (lib "eagle-import") (part "RESISTOR_0603"))
    )
    (comp (ref "R23")
      (value "10K")
      (footprint "eagle-import:R0603")
      (libsource (lib "eagle-import") (part "RESISTOR_0603"))
    )
    (comp (ref "R24")
      (value "10K")
      (footprint "eagle-import:R0603")
      (libsource (lib "eagle-import") (part "RESISTOR_0603"))
    )
    (comp (ref "R25")
      (value "10K")
      (footprint "eagle-import:R0603")
      (libsource (lib "eagle-import") (part "RESISTOR_0603"))
    )
    (comp (ref "R26")
      (value "10K")
      (footprint "eagle-import:R0603")
      (libsource (lib "eagle-import") (part "RESISTOR_0603"))
    )
    (comp (ref "R27")
      (value "10K")
      (footprint "eagle-import:R0603")
      (libsource (lib "eagle-import") (part "RESISTOR_0603"))
    )
    (comp (ref "R28")
      (value "10K")
      (footprint "eagle-import:R0603")
      (libsource (lib "eagle-import") (part "RESISTOR_0603"))
    )
    (comp (ref "R29")
      (value "10K")
      (footprint "eagle-import:R0603")
      (libsource (lib "eagle-import") (part "RESISTOR_0603"))
    )
    (comp (ref "R30")
      (value "330")
      (footprint "eagle-import:R0603")
      (libsource (lib "eagle-import") (part "RESISTOR_0603"))
    )
    (comp (ref "R31")
      (value "10K")
      (footprint "eagle-import:R0603")
      (libsource (lib "eagle-import") (part "RESISTOR_0603"))
    )
    (comp (ref "R32")
      (value "10K")
      (footprint "eagle-import:R0603")
      (libsource (lib "eagle-import") (part "RESISTOR_0603"))
    )
    (comp (ref "R33")
      (value "10K")
      (footprint "eagle-import:R0603")
      (libsource (lib "eagle-import") (part "RESISTOR_0603"))
    )
    (comp (ref "R34")
      (value "10K")
      (footprint "eagle-import:R0603")
      (libsource (lib "eagle-import") (part "RESISTOR_0603"))
    )
    (comp (ref "R35")
      (value "10K")
      (footprint "eagle-import:R0603")
      (libsource (lib "eagle-import") (part "RESISTOR_0603"))
    )
    (comp (ref "R36")
      (value "10K")
      (footprint "eagle-import:R0603")
      (libsource (lib "eagle-import") (part "RESISTOR_0603"))
    )
    (comp (ref "R37")
      (value "10K")
      (footprint "eagle-import:R0603")
      (libsource (lib "eagle-import") (part "RESISTOR_0603"))
    )
    (comp (ref "R38")
      (value "10K")
      (footprint "eagle-import:R0603")
      (libsource (lib "eagle-import") (part "RESISTOR_0603"))
    )
    (comp (ref "R39")
      (value "10K")
      (footprint "eagle-import:R0603")
      (libsource (lib "eagle-import") (part "RESISTOR_0603"))
    )
    (comp (ref "R40")
      (value "10K")
      (footprint "eagle-import:R0603")
      (libsource (lib "eagle-import") (part "RESISTOR_0603"))
    )
    (comp (ref "R41")
      (value "10K")
      (footprint "eagle-import:R0603")
      (libsource (lib "eagle-import") (part "RESISTOR_0603"))
    )
    (comp (ref "R42")
      (value "10K")
      (footprint "eagle-import:R0603")
      (libsource (lib "eagle-import") (part "RESISTOR_0603"))
    )
    (comp (ref "R43")
      (value "10K")
      (footprint "eagle-import:R0603")
      (libsource (lib "eagle-import") (part "RESISTOR_0603"))
    )
    (comp (ref "R44")
      (value "10K")
      (footprint "eagle-import:R0603")
      (libsource (lib "eagle-import") (part "RESISTOR_0603"))
    )
    (comp (ref "R45")
      (value "10K")
      (footprint "eagle-import:R0603")
      (libsource (lib "eagle-import") (part "RESISTOR_0603"))
    )
    (comp (ref "R46")
      (value "10K")
      (footprint "eagle-import:R0603")
      (libsource (lib "eagle-import") (part "RESISTOR_0603"))
    )
    (comp (ref "R47")
      (value "10K")
      (footprint "eagle-import:R0603")
      (libsource (lib "eagle-import") (part "RESISTOR_0603"))
    )
    (comp (ref "R48")
      (value "10K")
      (footprint "eagle-import:R0603")
      (libsource (lib "eagle-import") (part "RESISTOR_0603"))
    )
    (comp (ref "R49")
      (value "10K")
      (footprint "eagle-import:R0603")
      (libsource (lib "eagle-import") (part "RESISTOR_0603"))
    )
    (comp (ref "R50")
      (value "10K")
      (footprint "eagle-import:R0603")
      (libsource (lib "eagle-import") (part "RESISTOR_0603"))
    )
    (comp (ref "R51")
      (value "10K")
      (footprint "eagle-import:R0603")
      (libsource (lib "eagle-import") (part "RESISTOR_0603"))
    )
    (comp (ref "R52")
      (value "10K")
      (footprint "eagle-import:R0603")
      (libsource (lib "eagle-import") (part "RESISTOR_0603"))
    )
    (comp (ref "R53")
      (value "10K")
      (footprint "eagle-import:R0603")
      (libsource (lib "eagle-import") (part "RESISTOR_0603"))
    )
    (comp (ref "R54")
      (value "10K")
      (footprint "eagle-import:R0603")
      (libsource (lib "eagle-import") (part "RESISTOR_0603"))
    )
    (comp (ref "R55")
      (value "10K")
      (footprint "eagle-import:R0603")
      (libsource (lib "eagle-import") (part "RESISTOR_0603"))
    )
    (comp (ref "R56")
      (value "10K")
      (footprint "eagle-import:R0603")
      (libsource (lib "eagle-import") (part "RESISTOR_0603"))
    )
    (comp (ref "R57")
      (value "10K")
      (footprint "eagle-import:R0603")
      (libsource (lib "eagle-import") (part "RESISTOR_0603"))
    )
    (comp (ref "R58")
      (value "10K")
      (footprint "eagle-import:R0603")
      (libsource (lib "eagle-import") (part "RESISTOR_0603"))
    )
    (comp (ref "R59")
      (value "10K")
      (footprint "eagle-import:R0603")
      (libsource (lib "eagle-import") (part "RESISTOR_0603"))
    )
    (comp (ref "R60")
      (value "10K")
      (footprint "eagle-import:R0603")
      (libsource (lib "eagle-import") (part "RESISTOR_0603"))
    )
    (comp (ref "R61")
      (value "10K")
      (footprint "eagle-import:R0603")
      (libsource (lib "eagle-import") (part "RESISTOR_0603"))
    )
    (comp (ref "R62")
      (value "10K")
      (footprint "eagle-import:R0603")
      (libsource (lib "eagle-import") (part "RESISTOR_0603"))
    )
    (comp (ref "R63")
      (value "10K")
      (footprint "eagle-import:R0603")
      (libsource (lib "eagle-import") (part "RESISTOR_0603"))
    )
    (comp (ref "R64")
      (value "10K")
      (footprint "eagle-import:R0603")
      (libsource (lib "eagle-import") (part "RESISTOR_0603"))
    )
    (comp (ref "R65")
      (value "10K")
      (footprint "eagle-import:R0603")
      (libsource (lib "eagle-import") (part "RESISTOR_0603"))
    )
    (comp (ref "R66")
      (value "10K")
      (footprint "eagle-import:R0603")
      (libsource (lib "eagle-import") (part "RESISTOR_0603"))
    )
    (comp (ref "R67")
      (value "10K")
      (footprint "eagle-import:R0603")
      (libsource (lib "eagle-import") (part "RESISTOR_0603"))
    )
    (comp (ref "R68")
      (value "10K")
      (footprint "eagle-import:R0603")
      (libsource (lib "eagle-import") (part "RESISTOR_0603"))
    )
    (comp (ref "R69")
      (value "10K")
      (footprint "eagle-import:R0603")
      (libsource (lib "eagle-import") (part "RESISTOR_0603"))
    )
    (comp (ref "R70")
      (value "10K")
      (footprint "eagle-import:R0603")
      (libsource (lib "eagle-import") (part "RESISTOR_0603"))
    )
    (comp (ref "R71")
      (value "10K")
      (footprint "eagle-import:R0603")
      (libsource (lib "eagle-import") (part "RESISTOR_0603"))
    )
    (comp (ref "R72")
      (value "10K")
      (footprint "eagle-import:R0603")
      (libsource (lib "eagle-import") (part "RESISTOR_0603"))
    )
    (comp (ref "R73")
      (value "10K")
      (footprint "eagle-import:R0603")
      (libsource (lib "eagle-import") (part "RESISTOR_0603"))
    )
    (comp (ref "R74")
      (value "10K")
      (footprint "eagle-import:R0603")
      (libsource (lib "eagle-import") (part "RESISTOR_0603"))
    )
    (comp (ref "R75")
      (value "10K")
      (footprint "eagle-import:R0603")
      (libsource (lib "eagle-import") (part "RESISTOR_0603"))
    )
    (comp (ref "R76")
      (value "10K")
      (footprint "eagle-import:R0603")
      (libsource (lib "eagle-import") (part "RESISTOR_0603"))
    )
    (comp (ref "R77")
      (value "10K")
      (footprint "eagle-import:R0603")
      (libsource (lib "eagle-import") (part "RESISTOR_0603"))
    )
    (comp (ref "R78")
      (value "10K")
      (footprint "eagle-import:R0603")
      (libsource (lib "eagle-import") (part "RESISTOR_0603"))
    )
    (comp (ref "R79")
      (value "10K")
      (footprint "eagle-import:R0603")
      (libsource (lib "eagle-import") (part "RESISTOR_0603"))
    )
    (comp (ref "R80")
      (value "10K")
      (footprint "eagle-import:R0603")
      (libsource (lib "eagle-import") (part "RESISTOR_0603"))
    )
    (comp (ref "R81")
      (value "10K")
      (footprint "eagle-import:R0603")
      (libsource (lib "eagle-import") (part "RESISTOR_0603"))
    )
    (comp (ref "R82")
      (value "10K")
      (footprint "eagle-import:R0603")
      (libsource (lib "eagle-import") (part "RESISTOR_0603"))
    )
    (comp (ref "R83")
      (value "10K")
      (footprint "eagle-import:R0603")
      (libsource (lib "eagle-import") (part "RESISTOR_0603"))
    )
    (comp (ref "R84")
      (value "10K")
      (footprint "eagle-import:R0603")
      (libsource (lib "eagle-import") (part "RESISTOR_0603"))
    )
    (comp (ref "R85")
      (value "30K")
      (footprint "eagle-import:R0603")
      (libsource (lib "eagle-import") (part "RESISTOR_0603"))
    )
    (comp (ref "R86")
      (value "30K")
      (footprint "eagle-import:R0603")
      (libsource (lib "eagle-import") (part "RESISTOR_0603"))
    )
    (comp (ref "R87")
      (value "30K")
      (footprint "eagle-import:R0603")
      (libsource (lib "eagle-import") (part "RESISTOR_0603"))
    )
    (comp (ref "R88")
      (value "30K")
      (footprint "eagle-import:R0603")
      (libsource (lib "eagle-import") (part "RESISTOR_0603"))
    )
    (comp (ref "R89")
      (value "30K")
      (footprint "eagle-import:R0603")
      (libsource (lib "eagle-import") (part "RESISTOR_0603"))
    )
    (comp (ref "R90")
      (value "30K")
      (footprint "eagle-import:R0603")
      (libsource (lib "eagle-import") (part "RESISTOR_0603"))
    )
    (comp (ref "R91")
      (value "30K")
      (footprint "eagle-import:R0603")
      (libsource (lib "eagle-import") (part "RESISTOR_0603"))
    )
    (comp (ref "R92")
      (value "30K")
      (footprint "eagle-import:R0603")
      (libsource (lib "eagle-import") (part "RESISTOR_0603"))
    )
    (comp (ref "R93")
      (value "10K")
      (footprint "eagle-import:R0603")
      (libsource (lib "eagle-import") (part "RESISTOR_0603"))
    )
    (comp (ref "R94")
      (value "10K")
      (footprint "eagle-import:R0603")
      (libsource (lib "eagle-import") (part "RESISTOR_0603"))
    )
    (comp (ref "R97")
      (value "10K")
      (footprint "eagle-import:R0603")
      (libsource (lib "eagle-import") (part "RESISTOR_0603"))
    )
    (comp (ref "R98")
      (value "10K")
      (footprint "eagle-import:R0603")
      (libsource (lib "eagle-import") (part "RESISTOR_0603"))
    )
    (comp (ref "R99")
      (value "10K")
      (footprint "eagle-import:R0603")
      (libsource (lib "eagle-import") (part "RESISTOR_0603"))
    )
    (comp (ref "R100")
      (value "10K")
      (footprint "eagle-import:R0603")
      (libsource (lib "eagle-import") (part "RESISTOR_0603"))
    )
    (comp (ref "RGB_BOUT_L")
      (value "0914-3-15-20-77-14-11-0")
      (footprint "eagle-import:0914-3-15-20-77-14-11-0")
      (libsource (lib "eagle-import") (part "POGO_PIN_0914-3-15-20-77-14-11-0"))
    )
    (comp (ref "RGB_BOUT_R")
      (value "0914-3-15-20-77-14-11-0")
      (footprint "eagle-import:0914-3-15-20-77-14-11-0")
      (libsource (lib "eagle-import") (part "POGO_PIN_0914-3-15-20-77-14-11-0"))
    )
    (comp (ref "RGB_GOUT_L")
      (value "0914-3-15-20-77-14-11-0")
      (footprint "eagle-import:0914-3-15-20-77-14-11-0")
      (libsource (lib "eagle-import") (part "POGO_PIN_0914-3-15-20-77-14-11-0"))
    )
    (comp (ref "RGB_GOUT_R")
      (value "0914-3-15-20-77-14-11-0")
      (footprint "eagle-import:0914-3-15-20-77-14-11-0")
      (libsource (lib "eagle-import") (part "POGO_PIN_0914-3-15-20-77-14-11-0"))
    )
    (comp (ref "RGB_ROUT_L")
      (value "0914-3-15-20-77-14-11-0")
      (footprint "eagle-import:0914-3-15-20-77-14-11-0")
      (libsource (lib "eagle-import") (part "POGO_PIN_0914-3-15-20-77-14-11-0"))
    )
    (comp (ref "RGB_ROUT_R")
      (value "0914-3-15-20-77-14-11-0")
      (footprint "eagle-import:0914-3-15-20-77-14-11-0")
      (libsource (lib "eagle-import") (part "POGO_PIN_0914-3-15-20-77-14-11-0"))
    )
    (comp (ref "RX")
      (value "MF_LED_0805_RED")
      (footprint "eagle-import:LED0805")
      (libsource (lib "eagle-import") (part "LED_SINGLE_0805"))
    )
    (comp (ref "RX_PIC32")
      (value "0914-3-15-20-77-14-11-0")
      (footprint "eagle-import:0914-3-15-20-77-14-11-0")
      (libsource (lib "eagle-import") (part "POGO_PIN_0914-3-15-20-77-14-11-0"))
    )
    (comp (ref "RX_PROP")
      (value "0914-3-15-20-77-14-11-0")
      (footprint "eagle-import:0914-3-15-20-77-14-11-0")
      (libsource (lib "eagle-import") (part "POGO_PIN_0914-3-15-20-77-14-11-0"))
    )
    (comp (ref "R_FLIP_OUT")
      (value "0914-3-15-20-77-14-11-0")
      (footprint "eagle-import:0914-3-15-20-77-14-11-0")
      (libsource (lib "eagle-import") (part "POGO_PIN_0914-3-15-20-77-14-11-0"))
    )
    (comp (ref "SD_CS")
      (value "0914-3-15-20-77-14-11-0")
      (footprint "eagle-import:0914-3-15-20-77-14-11-0")
      (libsource (lib "eagle-import") (part "POGO_PIN_0914-3-15-20-77-14-11-0"))
    )
    (comp (ref "SD_DI")
      (value "0914-3-15-20-77-14-11-0")
      (footprint "eagle-import:0914-3-15-20-77-14-11-0")
      (libsource (lib "eagle-import") (part "POGO_PIN_0914-3-15-20-77-14-11-0"))
    )
    (comp (ref "SD_DO")
      (value "0914-3-15-20-77-14-11-0")
      (footprint "eagle-import:0914-3-15-20-77-14-11-0")
      (libsource (lib "eagle-import") (part "POGO_PIN_0914-3-15-20-77-14-11-0"))
    )
    (comp (ref "SD_SCLK")
      (value "0914-3-15-20-77-14-11-0")
      (footprint "eagle-import:0914-3-15-20-77-14-11-0")
      (libsource (lib "eagle-import") (part "POGO_PIN_0914-3-15-20-77-14-11-0"))
    )
    (comp (ref "SERVO_0_")
      (value "0914-3-15-20-77-14-11-0")
      (footprint "eagle-import:0914-3-15-20-77-14-11-0")
      (libsource (lib "eagle-import") (part "POGO_PIN_0914-3-15-20-77-14-11-0"))
    )
    (comp (ref "SERVO_1_")
      (value "0914-3-15-20-77-14-11-0")
      (footprint "eagle-import:0914-3-15-20-77-14-11-0")
      (libsource (lib "eagle-import") (part "POGO_PIN_0914-3-15-20-77-14-11-0"))
    )
    (comp (ref "SERVO_2_")
      (value "0914-3-15-20-77-14-11-0")
      (footprint "eagle-import:0914-3-15-20-77-14-11-0")
      (libsource (lib "eagle-import") (part "POGO_PIN_0914-3-15-20-77-14-11-0"))
    )
    (comp (ref "SERVO_3_")
      (value "0914-3-15-20-77-14-11-0")
      (footprint "eagle-import:0914-3-15-20-77-14-11-0")
      (libsource (lib "eagle-import") (part "POGO_PIN_0914-3-15-20-77-14-11-0"))
    )
    (comp (ref "SERVO_4_")
      (value "0914-3-15-20-77-14-11-0")
      (footprint "eagle-import:0914-3-15-20-77-14-11-0")
      (libsource (lib "eagle-import") (part "POGO_PIN_0914-3-15-20-77-14-11-0"))
    )
    (comp (ref "SOL_GND")
      (value "0914-3-15-20-77-14-11-0")
      (footprint "eagle-import:0914-3-15-20-77-14-11-0")
      (libsource (lib "eagle-import") (part "POGO_PIN_0914-3-15-20-77-14-11-0"))
    )
    (comp (ref "SOL_PWR_0")
      (value "0914-3-15-20-77-14-11-0")
      (footprint "eagle-import:0914-3-15-20-77-14-11-0")
      (libsource (lib "eagle-import") (part "POGO_PIN_0914-3-15-20-77-14-11-0"))
    )
    (comp (ref "SOL_PWR_1")
      (value "0914-3-15-20-77-14-11-0")
      (footprint "eagle-import:0914-3-15-20-77-14-11-0")
      (libsource (lib "eagle-import") (part "POGO_PIN_0914-3-15-20-77-14-11-0"))
    )
    (comp (ref "SOL_PWR_2")
      (value "0914-3-15-20-77-14-11-0")
      (footprint "eagle-import:0914-3-15-20-77-14-11-0")
      (libsource (lib "eagle-import") (part "POGO_PIN_0914-3-15-20-77-14-11-0"))
    )
    (comp (ref "SOL_PWR_3")
      (value "0914-3-15-20-77-14-11-0")
      (footprint "eagle-import:0914-3-15-20-77-14-11-0")
      (libsource (lib "eagle-import") (part "POGO_PIN_0914-3-15-20-77-14-11-0"))
    )
    (comp (ref "SOL_PWR_4")
      (value "0914-3-15-20-77-14-11-0")
      (footprint "eagle-import:0914-3-15-20-77-14-11-0")
      (libsource (lib "eagle-import") (part "POGO_PIN_0914-3-15-20-77-14-11-0"))
    )
    (comp (ref "SOL_PWR_5")
      (value "0914-3-15-20-77-14-11-0")
      (footprint "eagle-import:0914-3-15-20-77-14-11-0")
      (libsource (lib "eagle-import") (part "POGO_PIN_0914-3-15-20-77-14-11-0"))
    )
    (comp (ref "SOL_PWR_6")
      (value "0914-3-15-20-77-14-11-0")
      (footprint "eagle-import:0914-3-15-20-77-14-11-0")
      (libsource (lib "eagle-import") (part "POGO_PIN_0914-3-15-20-77-14-11-0"))
    )
    (comp (ref "SOL_PWR_7")
      (value "0914-3-15-20-77-14-11-0")
      (footprint "eagle-import:0914-3-15-20-77-14-11-0")
      (libsource (lib "eagle-import") (part "POGO_PIN_0914-3-15-20-77-14-11-0"))
    )
    (comp (ref "SOL_PWR_8")
      (value "0914-3-15-20-77-14-11-0")
      (footprint "eagle-import:0914-3-15-20-77-14-11-0")
      (libsource (lib "eagle-import") (part "POGO_PIN_0914-3-15-20-77-14-11-0"))
    )
    (comp (ref "SOL_PWR_9")
      (value "0914-3-15-20-77-14-11-0")
      (footprint "eagle-import:0914-3-15-20-77-14-11-0")
      (libsource (lib "eagle-import") (part "POGO_PIN_0914-3-15-20-77-14-11-0"))
    )
    (comp (ref "SOL_PWR_10")
      (value "0914-3-15-20-77-14-11-0")
      (footprint "eagle-import:0914-3-15-20-77-14-11-0")
      (libsource (lib "eagle-import") (part "POGO_PIN_0914-3-15-20-77-14-11-0"))
    )
    (comp (ref "SOL_PWR_11")
      (value "0914-3-15-20-77-14-11-0")
      (footprint "eagle-import:0914-3-15-20-77-14-11-0")
      (libsource (lib "eagle-import") (part "POGO_PIN_0914-3-15-20-77-14-11-0"))
    )
    (comp (ref "SOL_PWR_12")
      (value "0914-3-15-20-77-14-11-0")
      (footprint "eagle-import:0914-3-15-20-77-14-11-0")
      (libsource (lib "eagle-import") (part "POGO_PIN_0914-3-15-20-77-14-11-0"))
    )
    (comp (ref "SOL_PWR_13")
      (value "0914-3-15-20-77-14-11-0")
      (footprint "eagle-import:0914-3-15-20-77-14-11-0")
      (libsource (lib "eagle-import") (part "POGO_PIN_0914-3-15-20-77-14-11-0"))
    )
    (comp (ref "SOL_PWR_14")
      (value "0914-3-15-20-77-14-11-0")
      (footprint "eagle-import:0914-3-15-20-77-14-11-0")
      (libsource (lib "eagle-import") (part "POGO_PIN_0914-3-15-20-77-14-11-0"))
    )
    (comp (ref "SOL_PWR_15")
      (value "0914-3-15-20-77-14-11-0")
      (footprint "eagle-import:0914-3-15-20-77-14-11-0")
      (libsource (lib "eagle-import") (part "POGO_PIN_0914-3-15-20-77-14-11-0"))
    )
    (comp (ref "SOL_PWR_16")
      (value "0914-3-15-20-77-14-11-0")
      (footprint "eagle-import:0914-3-15-20-77-14-11-0")
      (libsource (lib "eagle-import") (part "POGO_PIN_0914-3-15-20-77-14-11-0"))
    )
    (comp (ref "SOL_PWR_17")
      (value "0914-3-15-20-77-14-11-0")
      (footprint "eagle-import:0914-3-15-20-77-14-11-0")
      (libsource (lib "eagle-import") (part "POGO_PIN_0914-3-15-20-77-14-11-0"))
    )
    (comp (ref "SOL_PWR_18")
      (value "0914-3-15-20-77-14-11-0")
      (footprint "eagle-import:0914-3-15-20-77-14-11-0")
      (libsource (lib "eagle-import") (part "POGO_PIN_0914-3-15-20-77-14-11-0"))
    )
    (comp (ref "SOL_PWR_19")
      (value "0914-3-15-20-77-14-11-0")
      (footprint "eagle-import:0914-3-15-20-77-14-11-0")
      (libsource (lib "eagle-import") (part "POGO_PIN_0914-3-15-20-77-14-11-0"))
    )
    (comp (ref "SOL_PWR_20")
      (value "0914-3-15-20-77-14-11-0")
      (footprint "eagle-import:0914-3-15-20-77-14-11-0")
      (libsource (lib "eagle-import") (part "POGO_PIN_0914-3-15-20-77-14-11-0"))
    )
    (comp (ref "SOL_PWR_21")
      (value "0914-3-15-20-77-14-11-0")
      (footprint "eagle-import:0914-3-15-20-77-14-11-0")
      (libsource (lib "eagle-import") (part "POGO_PIN_0914-3-15-20-77-14-11-0"))
    )
    (comp (ref "SOL_PWR_22")
      (value "0914-3-15-20-77-14-11-0")
      (footprint "eagle-import:0914-3-15-20-77-14-11-0")
      (libsource (lib "eagle-import") (part "POGO_PIN_0914-3-15-20-77-14-11-0"))
    )
    (comp (ref "SOL_PWR_23")
      (value "0914-3-15-20-77-14-11-0")
      (footprint "eagle-import:0914-3-15-20-77-14-11-0")
      (libsource (lib "eagle-import") (part "POGO_PIN_0914-3-15-20-77-14-11-0"))
    )
    (comp (ref "ST_BU_OUT")
      (value "0914-3-15-20-77-14-11-0")
      (footprint "eagle-import:0914-3-15-20-77-14-11-0")
      (libsource (lib "eagle-import") (part "POGO_PIN_0914-3-15-20-77-14-11-0"))
    )
    (comp (ref "ST_LI_")
      (value "0914-3-15-20-77-14-11-0")
      (footprint "eagle-import:0914-3-15-20-77-14-11-0")
      (libsource (lib "eagle-import") (part "POGO_PIN_0914-3-15-20-77-14-11-0"))
    )
    (comp (ref "SW_C_0")
      (value "0914-3-15-20-77-14-11-0")
      (footprint "eagle-import:0914-3-15-20-77-14-11-0")
      (libsource (lib "eagle-import") (part "POGO_PIN_0914-3-15-20-77-14-11-0"))
    )
    (comp (ref "SW_C_1")
      (value "0914-3-15-20-77-14-11-0")
      (footprint "eagle-import:0914-3-15-20-77-14-11-0")
      (libsource (lib "eagle-import") (part "POGO_PIN_0914-3-15-20-77-14-11-0"))
    )
    (comp (ref "SW_C_2")
      (value "0914-3-15-20-77-14-11-0")
      (footprint "eagle-import:0914-3-15-20-77-14-11-0")
      (libsource (lib "eagle-import") (part "POGO_PIN_0914-3-15-20-77-14-11-0"))
    )
    (comp (ref "SW_C_3")
      (value "0914-3-15-20-77-14-11-0")
      (footprint "eagle-import:0914-3-15-20-77-14-11-0")
      (libsource (lib "eagle-import") (part "POGO_PIN_0914-3-15-20-77-14-11-0"))
    )
    (comp (ref "SW_C_4")
      (value "0914-3-15-20-77-14-11-0")
      (footprint "eagle-import:0914-3-15-20-77-14-11-0")
      (libsource (lib "eagle-import") (part "POGO_PIN_0914-3-15-20-77-14-11-0"))
    )
    (comp (ref "SW_C_5")
      (value "0914-3-15-20-77-14-11-0")
      (footprint "eagle-import:0914-3-15-20-77-14-11-0")
      (libsource (lib "eagle-import") (part "POGO_PIN_0914-3-15-20-77-14-11-0"))
    )
    (comp (ref "SW_C_6")
      (value "0914-3-15-20-77-14-11-0")
      (footprint "eagle-import:0914-3-15-20-77-14-11-0")
      (libsource (lib "eagle-import") (part "POGO_PIN_0914-3-15-20-77-14-11-0"))
    )
    (comp (ref "SW_C_7")
      (value "0914-3-15-20-77-14-11-0")
      (footprint "eagle-import:0914-3-15-20-77-14-11-0")
      (libsource (lib "eagle-import") (part "POGO_PIN_0914-3-15-20-77-14-11-0"))
    )
    (comp (ref "SW_R_0")
      (value "0914-3-15-20-77-14-11-0")
      (footprint "eagle-import:0914-3-15-20-77-14-11-0")
      (libsource (lib "eagle-import") (part "POGO_PIN_0914-3-15-20-77-14-11-0"))
    )
    (comp (ref "SW_R_1")
      (value "0914-3-15-20-77-14-11-0")
      (footprint "eagle-import:0914-3-15-20-77-14-11-0")
      (libsource (lib "eagle-import") (part "POGO_PIN_0914-3-15-20-77-14-11-0"))
    )
    (comp (ref "SW_R_2")
      (value "0914-3-15-20-77-14-11-0")
      (footprint "eagle-import:0914-3-15-20-77-14-11-0")
      (libsource (lib "eagle-import") (part "POGO_PIN_0914-3-15-20-77-14-11-0"))
    )
    (comp (ref "SW_R_3")
      (value "0914-3-15-20-77-14-11-0")
      (footprint "eagle-import:0914-3-15-20-77-14-11-0")
      (libsource (lib "eagle-import") (part "POGO_PIN_0914-3-15-20-77-14-11-0"))
    )
    (comp (ref "SW_R_4")
      (value "0914-3-15-20-77-14-11-0")
      (footprint "eagle-import:0914-3-15-20-77-14-11-0")
      (libsource (lib "eagle-import") (part "POGO_PIN_0914-3-15-20-77-14-11-0"))
    )
    (comp (ref "SW_R_5")
      (value "0914-3-15-20-77-14-11-0")
      (footprint "eagle-import:0914-3-15-20-77-14-11-0")
      (libsource (lib "eagle-import") (part "POGO_PIN_0914-3-15-20-77-14-11-0"))
    )
    (comp (ref "SW_R_6")
      (value "0914-3-15-20-77-14-11-0")
      (footprint "eagle-import:0914-3-15-20-77-14-11-0")
      (libsource (lib "eagle-import") (part "POGO_PIN_0914-3-15-20-77-14-11-0"))
    )
    (comp (ref "SW_R_7")
      (value "0914-3-15-20-77-14-11-0")
      (footprint "eagle-import:0914-3-15-20-77-14-11-0")
      (libsource (lib "eagle-import") (part "POGO_PIN_0914-3-15-20-77-14-11-0"))
    )
    (comp (ref "S_L")
      (value "0914-3-15-20-77-14-11-0")
      (footprint "eagle-import:0914-3-15-20-77-14-11-0")
      (libsource (lib "eagle-import") (part "POGO_PIN_0914-3-15-20-77-14-11-0"))
    )
    (comp (ref "S_R")
      (value "0914-3-15-20-77-14-11-0")
      (footprint "eagle-import:0914-3-15-20-77-14-11-0")
      (libsource (lib "eagle-import") (part "POGO_PIN_0914-3-15-20-77-14-11-0"))
    )
    (comp (ref "TILT_OUT")
      (value "0914-3-15-20-77-14-11-0")
      (footprint "eagle-import:0914-3-15-20-77-14-11-0")
      (libsource (lib "eagle-import") (part "POGO_PIN_0914-3-15-20-77-14-11-0"))
    )
    (comp (ref "TVS1")
      (value "V18AUMLA2220H")
      (footprint "eagle-import:2220")
      (libsource (lib "eagle-import") (part "TVS_DIODE_2220"))
    )
    (comp (ref "TX")
      (value "MF_LED_0805_RED")
      (footprint "eagle-import:LED0805")
      (libsource (lib "eagle-import") (part "LED_SINGLE_0805"))
    )
    (comp (ref "TX_PIC32")
      (value "0914-3-15-20-77-14-11-0")
      (footprint "eagle-import:0914-3-15-20-77-14-11-0")
      (libsource (lib "eagle-import") (part "POGO_PIN_0914-3-15-20-77-14-11-0"))
    )
    (comp (ref "TX_PROP")
      (value "0914-3-15-20-77-14-11-0")
      (footprint "eagle-import:0914-3-15-20-77-14-11-0")
      (libsource (lib "eagle-import") (part "POGO_PIN_0914-3-15-20-77-14-11-0"))
    )
    (comp (ref "U1")
      (value "P8X32A-Q44")
      (footprint "eagle-import:LQFP44")
      (libsource (lib "eagle-import") (part "P8X32A-Q44"))
    )
    (comp (ref "U2")
      (value "CAT24C512WI-GT3")
      (footprint "eagle-import:SOIC-8_W")
      (libsource (lib "eagle-import") (part "EEPROM_I2CSOIC-8_W"))
    )
    (comp (ref "U3")
      (value "FT230XS")
      (footprint "eagle-import:SSOP16")
      (libsource (lib "eagle-import") (part "FT230XS"))
    )
    (comp (ref "U4")
      (value "IP4234CZ6")
      (footprint "eagle-import:IP4234CZ6_SOT-457-6")
      (libsource (lib "eagle-import") (part "IP4234CZ6"))
    )
    (comp (ref "U5")
      (value "NCP1117DT33G")
      (footprint "eagle-import:NCP1117DT_DPAK-3")
      (libsource (lib "eagle-import") (part "LINEAR_VOTLAGE_REGULATORS_NCP1117DT"))
    )
    (comp (ref "U6")
      (value "NCP1117DT50G")
      (footprint "eagle-import:NCP1117DT_DPAK-3")
      (libsource (lib "eagle-import") (part "LINEAR_VOTLAGE_REGULATORS_NCP1117DT"))
    )
    (comp (ref "U7")
      (value "INA139NA/3K")
      (footprint "eagle-import:INA169NA_250_SOT-23-5")
      (libsource (lib "eagle-import") (part "INA169SOT-23-5"))
    )
    (comp (ref "U8")
      (value "INA139NA/3K")
      (footprint "eagle-import:INA169NA_250_SOT-23-5")
      (libsource (lib "eagle-import") (part "INA169SOT-23-5"))
    )
    (comp (ref "U9")
      (value "MAX11613EUA+")
      (footprint "eagle-import:MAX11613_UMAX-8")
      (libsource (lib "eagle-import") (part "MAX11613EUA+"))
    )
    (comp (ref "U10")
      (value "BSO080P03NS3E G")
      (footprint "eagle-import:DSO-8")
      (libsource (lib "eagle-import") (part "MOSFET_P-CHANNEL_SINGLE_P3-POWER"))
    )
    (comp (ref "U11")
      (value "BSO080P03NS3E G")
      (footprint "eagle-import:DSO-8")
      (libsource (lib "eagle-import") (part "MOSFET_P-CHANNEL_SINGLE_P3-POWER"))
    )
    (comp (ref "U12")
      (value "MF-DSC-SOT233-MMBT3904")
      (footprint "eagle-import:SOT-23-3")
      (libsource (lib "eagle-import") (part "BJT_NPN_SINGLE_SOT-23"))
    )
    (comp (ref "U13")
      (value "MF-DSC-SOT233-MMBT3904")
      (footprint "eagle-import:SOT-23-3")
      (libsource (lib "eagle-import") (part "BJT_NPN_SINGLE_SOT-23"))
    )
    (comp (ref "U14")
      (value "CD74HC595M96")
      (footprint "eagle-import:CD74HC595_SOIC-16")
      (libsource (lib "eagle-import") (part "CD74HC595M96"))
    )
    (comp (ref "U15")
      (value "CD74HC595M96")
      (footprint "eagle-import:CD74HC595_SOIC-16")
      (libsource (lib "eagle-import") (part "CD74HC595M96"))
    )
    (comp (ref "U16")
      (value "CD74HC165M96")
      (footprint "eagle-import:CD74HC165_SOIC-16")
      (libsource (lib "eagle-import") (part "CD74HC165M96"))
    )
    (comp (ref "U17")
      (value "CD74HC165M96")
      (footprint "eagle-import:CD74HC165_SOIC-16")
      (libsource (lib "eagle-import") (part "CD74HC165M96"))
    )
    (comp (ref "U18")
      (value "CD74HC165M96")
      (footprint "eagle-import:CD74HC165_SOIC-16")
      (libsource (lib "eagle-import") (part "CD74HC165M96"))
    )
    (comp (ref "U19")
      (value "CD74HC165M96")
      (footprint "eagle-import:CD74HC165_SOIC-16")
      (libsource (lib "eagle-import") (part "CD74HC165M96"))
    )
    (comp (ref "U20")
      (value "CD74HC165M96")
      (footprint "eagle-import:CD74HC165_SOIC-16")
      (libsource (lib "eagle-import") (part "CD74HC165M96"))
    )
    (comp (ref "U21")
      (value "CD74HC165M96")
      (footprint "eagle-import:CD74HC165_SOIC-16")
      (libsource (lib "eagle-import") (part "CD74HC165M96"))
    )
    (comp (ref "U22")
      (value "CD74HC165M96")
      (footprint "eagle-import:CD74HC165_SOIC-16")
      (libsource (lib "eagle-import") (part "CD74HC165M96"))
    )
    (comp (ref "U23")
      (value "CD74HC165M96")
      (footprint "eagle-import:CD74HC165_SOIC-16")
      (libsource (lib "eagle-import") (part "CD74HC165M96"))
    )
    (comp (ref "U24")
      (value "CD74HC165M96")
      (footprint "eagle-import:CD74HC165_SOIC-16")
      (libsource (lib "eagle-import") (part "CD74HC165M96"))
    )
    (comp (ref "U26")
      (value "CD74HC165M96")
      (footprint "eagle-import:CD74HC165_SOIC-16")
      (libsource (lib "eagle-import") (part "CD74HC165M96"))
    )
    (comp (ref "U27")
      (value "CD74HC165M96")
      (footprint "eagle-import:CD74HC165_SOIC-16")
      (libsource (lib "eagle-import") (part "CD74HC165M96"))
    )
    (comp (ref "U28")
      (value "CD74HC165M96")
      (footprint "eagle-import:CD74HC165_SOIC-16")
      (libsource (lib "eagle-import") (part "CD74HC165M96"))
    )
    (comp (ref "U29")
      (value "CD74HC165M96")
      (footprint "eagle-import:CD74HC165_SOIC-16")
      (libsource (lib "eagle-import") (part "CD74HC165M96"))
    )
    (comp (ref "U30")
      (value "CD74HC165M96")
      (footprint "eagle-import:CD74HC165_SOIC-16")
      (libsource (lib "eagle-import") (part "CD74HC165M96"))
    )
    (comp (ref "USB_PWR")
      (value "MF_LED_0805_RED")
      (footprint "eagle-import:LED0805")
      (libsource (lib "eagle-import") (part "LED_SINGLE_0805"))
    )
    (comp (ref "USER_0_OUT")
      (value "0914-3-15-20-77-14-11-0")
      (footprint "eagle-import:0914-3-15-20-77-14-11-0")
      (libsource (lib "eagle-import") (part "POGO_PIN_0914-3-15-20-77-14-11-0"))
    )
    (comp (ref "VDD")
      (value "POGO_PIN_0914-3-15-20-77-14-11-0")
      (footprint "eagle-import:0914-3-15-20-77-14-11-0")
      (libsource (lib "eagle-import") (part "POGO_PIN_0914-3-15-20-77-14-11-0"))
    )
    (comp (ref "VSS")
      (value "POGO_PIN_0914-3-15-20-77-14-11-0")
      (footprint "eagle-import:0914-3-15-20-77-14-11-0")
      (libsource (lib "eagle-import") (part "POGO_PIN_0914-3-15-20-77-14-11-0"))
    )
    (comp (ref "X1")
      (value "ABMM-6.000MHZ-B2-T")
      (footprint "eagle-import:7MMX5MM")
      (libsource (lib "eagle-import") (part "XTL_7MMX5MM"))
    )
  )
  (nets
    (net (code "1") (name "/3.3V_SENSE") (class "Default")
      (node (ref "3.3V") (pin "P$1") (pinfunction "P$1_P$1") (pintype "bidirectional"))
      (node (ref "U9") (pin "P$3") (pinfunction "A_2_P$3") (pintype "bidirectional"))
    )
    (net (code "2") (name "/3V3OUT") (class "Default")
      (node (ref "C10") (pin "P$1") (pinfunction "P$1_P$1") (pintype "passive"))
      (node (ref "U3") (pin "10") (pinfunction "3V3OUT_10") (pintype "bidirectional"))
      (node (ref "U3") (pin "11") (pinfunction "~{RESET}_11") (pintype "bidirectional"))
      (node (ref "U3") (pin "3") (pinfunction "VCCIO_3") (pintype "bidirectional"))
    )
    (net (code "3") (name "/5.0V_CUR") (class "Default")
      (node (ref "R15") (pin "2") (pinfunction "2_2") (pintype "passive"))
      (node (ref "R20") (pin "1") (pinfunction "1_1") (pintype "passive"))
      (node (ref "U11") (pin "5") (pinfunction "DRAIN_5") (pintype "bidirectional"))
      (node (ref "U11") (pin "6") (pinfunction "DRAIN_6") (pintype "bidirectional"))
      (node (ref "U11") (pin "7") (pinfunction "DRAIN_7") (pintype "bidirectional"))
      (node (ref "U11") (pin "8") (pinfunction "DRAIN_8") (pintype "bidirectional"))
      (node (ref "U8") (pin "4") (pinfunction "VIN-_4") (pintype "bidirectional"))
    )
    (net (code "4") (name "/50V") (class "Default")
      (node (ref "50V") (pin "P$1") (pinfunction "P$1_P$1") (pintype "bidirectional"))
    )
    (net (code "5") (name "/165_CLK") (class "Default")
      (node (ref "U1") (pin "19") (pinfunction "P16_19") (pintype "bidirectional"))
      (node (ref "U16") (pin "2") (pinfunction "CLK_2") (pintype "bidirectional"))
      (node (ref "U17") (pin "2") (pinfunction "CLK_2") (pintype "bidirectional"))
      (node (ref "U18") (pin "2") (pinfunction "CLK_2") (pintype "bidirectional"))
      (node (ref "U19") (pin "2") (pinfunction "CLK_2") (pintype "bidirectional"))
      (node (ref "U20") (pin "2") (pinfunction "CLK_2") (pintype "bidirectional"))
      (node (ref "U21") (pin "2") (pinfunction "CLK_2") (pintype "bidirectional"))
      (node (ref "U22") (pin "2") (pinfunction "CLK_2") (pintype "bidirectional"))
      (node (ref "U23") (pin "2") (pinfunction "CLK_2") (pintype "bidirectional"))
      (node (ref "U24") (pin "2") (pinfunction "CLK_2") (pintype "bidirectional"))
      (node (ref "U26") (pin "2") (pinfunction "CLK_2") (pintype "bidirectional"))
      (node (ref "U27") (pin "2") (pinfunction "CLK_2") (pintype "bidirectional"))
      (node (ref "U28") (pin "2") (pinfunction "CLK_2") (pintype "bidirectional"))
      (node (ref "U29") (pin "2") (pinfunction "CLK_2") (pintype "bidirectional"))
      (node (ref "U30") (pin "2") (pinfunction "CLK_2") (pintype "bidirectional"))
    )
    (net (code "6") (name "/165_DATA") (class "Default")
      (node (ref "U1") (pin "21") (pinfunction "P18_21") (pintype "bidirectional"))
      (node (ref "U16") (pin "9") (pinfunction "QH_9") (pintype "bidirectional"))
    )
    (net (code "7") (name "/165_LOAD") (class "Default")
      (node (ref "U1") (pin "20") (pinfunction "P17_20") (pintype "bidirectional"))
      (node (ref "U16") (pin "1") (pinfunction "LAT_1") (pintype "bidirectional"))
      (node (ref "U17") (pin "1") (pinfunction "LAT_1") (pintype "bidirectional"))
      (node (ref "U18") (pin "1") (pinfunction "LAT_1") (pintype "bidirectional"))
      (node (ref "U19") (pin "1") (pinfunction "LAT_1") (pintype "bidirectional"))
      (node (ref "U20") (pin "1") (pinfunction "LAT_1") (pintype "bidirectional"))
      (node (ref "U21") (pin "1") (pinfunction "LAT_1") (pintype "bidirectional"))
      (node (ref "U22") (pin "1") (pinfunction "LAT_1") (pintype "bidirectional"))
      (node (ref "U23") (pin "1") (pinfunction "LAT_1") (pintype "bidirectional"))
      (node (ref "U24") (pin "1") (pinfunction "LAT_1") (pintype "bidirectional"))
      (node (ref "U26") (pin "1") (pinfunction "LAT_1") (pintype "bidirectional"))
      (node (ref "U27") (pin "1") (pinfunction "LAT_1") (pintype "bidirectional"))
      (node (ref "U28") (pin "1") (pinfunction "LAT_1") (pintype "bidirectional"))
      (node (ref "U29") (pin "1") (pinfunction "LAT_1") (pintype "bidirectional"))
      (node (ref "U30") (pin "1") (pinfunction "LAT_1") (pintype "bidirectional"))
    )
    (net (code "8") (name "/595_CLK") (class "Default")
      (node (ref "U1") (pin "22") (pinfunction "P19_22") (pintype "bidirectional"))
      (node (ref "U14") (pin "11") (pinfunction "SHCP_11") (pintype "bidirectional"))
      (node (ref "U15") (pin "11") (pinfunction "SHCP_11") (pintype "bidirectional"))
    )
    (net (code "9") (name "/595_DATA") (class "Default")
      (node (ref "U1") (pin "24") (pinfunction "P21_24") (pintype "bidirectional"))
      (node (ref "U14") (pin "14") (pinfunction "DS_14") (pintype "bidirectional"))
    )
    (net (code "10") (name "/595_LAT") (class "Default")
      (node (ref "U1") (pin "23") (pinfunction "P20_23") (pintype "bidirectional"))
      (node (ref "U14") (pin "12") (pinfunction "STCP_12") (pintype "bidirectional"))
      (node (ref "U15") (pin "12") (pinfunction "STCP_12") (pintype "bidirectional"))
    )
    (net (code "11") (name "/A_0") (class "Default")
      (node (ref "C21") (pin "1") (pinfunction "1_1") (pintype "passive"))
      (node (ref "R16") (pin "2") (pinfunction "2_2") (pintype "passive"))
      (node (ref "U7") (pin "1") (pinfunction "OUT_1") (pintype "bidirectional"))
      (node (ref "U9") (pin "P$1") (pinfunction "A_0_P$1") (pintype "bidirectional"))
    )
    (net (code "12") (name "/A_1") (class "Default")
      (node (ref "C22") (pin "1") (pinfunction "1_1") (pintype "passive"))
      (node (ref "R17") (pin "2") (pinfunction "2_2") (pintype "passive"))
      (node (ref "U8") (pin "1") (pinfunction "OUT_1") (pintype "bidirectional"))
      (node (ref "U9") (pin "P$2") (pinfunction "A_1_P$2") (pintype "bidirectional"))
    )
    (net (code "13") (name "/BACK_OUT") (class "Default")
      (node (ref "BACK_OUT") (pin "P$1") (pinfunction "P$1_P$1") (pintype "bidirectional"))
      (node (ref "U14") (pin "4") (pinfunction "Q4_4") (pintype "bidirectional"))
    )
    (net (code "14") (name "/COIN_OUT") (class "Default")
      (node (ref "COIN_OUT") (pin "P$1") (pinfunction "P$1_P$1") (pintype "bidirectional"))
      (node (ref "U14") (pin "2") (pinfunction "Q2_2") (pintype "bidirectional"))
    )
    (net (code "15") (name "/D+_USB") (class "Default")
      (node (ref "J1") (pin "3") (pinfunction "D+_3") (pintype "bidirectional"))
      (node (ref "U4") (pin "1") (pinfunction "I/O1A_1") (pintype "bidirectional"))
    )
    (net (code "16") (name "/D-_USB") (class "Default")
      (node (ref "J1") (pin "2") (pinfunction "D-_2") (pintype "bidirectional"))
      (node (ref "U4") (pin "6") (pinfunction "I/O2A_6") (pintype "bidirectional"))
    )
    (net (code "17") (name "/DMD_1") (class "Default")
      (node (ref "DMD_1") (pin "P$1") (pinfunction "P$1_P$1") (pintype "bidirectional"))
      (node (ref "U29") (pin "13") (pinfunction "D2_13") (pintype "bidirectional"))
    )
    (net (code "18") (name "/DMD_3") (class "Default")
      (node (ref "DMD_3") (pin "P$1") (pinfunction "P$1_P$1") (pintype "bidirectional"))
      (node (ref "U29") (pin "14") (pinfunction "D3_14") (pintype "bidirectional"))
    )
    (net (code "19") (name "/DMD_5") (class "Default")
      (node (ref "DMD_5") (pin "P$1") (pinfunction "P$1_P$1") (pintype "bidirectional"))
      (node (ref "U29") (pin "3") (pinfunction "D4_3") (pintype "bidirectional"))
    )
    (net (code "20") (name "/DMD_7") (class "Default")
      (node (ref "DMD_7") (pin "P$1") (pinfunction "P$1_P$1") (pintype "bidirectional"))
      (node (ref "U29") (pin "4") (pinfunction "D5_4") (pintype "bidirectional"))
    )
    (net (code "21") (name "/DMD_9") (class "Default")
      (node (ref "DMD_9") (pin "P$1") (pinfunction "P$1_P$1") (pintype "bidirectional"))
      (node (ref "U29") (pin "5") (pinfunction "D6_5") (pintype "bidirectional"))
    )
    (net (code "22") (name "/DMD_11") (class "Default")
      (node (ref "DMD_11") (pin "P$1") (pinfunction "P$1_P$1") (pintype "bidirectional"))
      (node (ref "U29") (pin "6") (pinfunction "D7_6") (pintype "bidirectional"))
    )
    (net (code "23") (name "/DMD_13") (class "Default")
      (node (ref "DMD_13") (pin "P$1") (pinfunction "P$1_P$1") (pintype "bidirectional"))
      (node (ref "U30") (pin "11") (pinfunction "D0_11") (pintype "bidirectional"))
    )
    (net (code "24") (name "/DOOR_OUT") (class "Default")
      (node (ref "DOOR_OUT") (pin "P$1") (pinfunction "P$1_P$1") (pintype "bidirectional"))
      (node (ref "U14") (pin "5") (pinfunction "Q5_5") (pintype "bidirectional"))
    )
    (net (code "25") (name "/ENTER_OUT") (class "Default")
      (node (ref "ENTER_OUT") (pin "P$1") (pinfunction "P$1_P$1") (pintype "bidirectional"))
      (node (ref "U14") (pin "3") (pinfunction "Q3_3") (pintype "bidirectional"))
    )
    (net (code "26") (name "/EXT_RGB_CLK") (class "Default")
      (node (ref "EXT_RGB_CLK") (pin "P$1") (pinfunction "P$1_P$1") (pintype "bidirectional"))
      (node (ref "U28") (pin "11") (pinfunction "D0_11") (pintype "bidirectional"))
    )
    (net (code "27") (name "/EXT_RGB_DATA") (class "Default")
      (node (ref "EXT_RGB_DATA") (pin "P$1") (pinfunction "P$1_P$1") (pintype "bidirectional"))
      (node (ref "U28") (pin "12") (pinfunction "D1_12") (pintype "bidirectional"))
    )
    (net (code "28") (name "/GI15") (class "Default")
      (node (ref "GI_R_15") (pin "P$1") (pinfunction "P$1_P$1") (pintype "bidirectional"))
      (node (ref "R28") (pin "P$2") (pinfunction "P$2_P$2") (pintype "passive"))
      (node (ref "U18") (pin "11") (pinfunction "D0_11") (pintype "bidirectional"))
    )
    (net (code "29") (name "/GI_R_0") (class "Default")
      (node (ref "GI_R_0") (pin "P$1") (pinfunction "P$1_P$1") (pintype "bidirectional"))
      (node (ref "R27") (pin "P$2") (pinfunction "P$2_P$2") (pintype "passive"))
      (node (ref "U17") (pin "6") (pinfunction "D7_6") (pintype "bidirectional"))
    )
    (net (code "30") (name "/GI_R_1") (class "Default")
      (node (ref "GI_R_1") (pin "P$1") (pinfunction "P$1_P$1") (pintype "bidirectional"))
      (node (ref "R26") (pin "P$2") (pinfunction "P$2_P$2") (pintype "passive"))
      (node (ref "U17") (pin "5") (pinfunction "D6_5") (pintype "bidirectional"))
    )
    (net (code "31") (name "/GI_R_2") (class "Default")
      (node (ref "GI_R_2") (pin "P$1") (pinfunction "P$1_P$1") (pintype "bidirectional"))
      (node (ref "R25") (pin "P$2") (pinfunction "P$2_P$2") (pintype "passive"))
      (node (ref "U17") (pin "4") (pinfunction "D5_4") (pintype "bidirectional"))
    )
    (net (code "32") (name "/GI_R_3") (class "Default")
      (node (ref "GI_R_3") (pin "P$1") (pinfunction "P$1_P$1") (pintype "bidirectional"))
      (node (ref "R24") (pin "P$2") (pinfunction "P$2_P$2") (pintype "passive"))
      (node (ref "U17") (pin "3") (pinfunction "D4_3") (pintype "bidirectional"))
    )
    (net (code "33") (name "/GI_R_4") (class "Default")
      (node (ref "GI_R_4") (pin "P$1") (pinfunction "P$1_P$1") (pintype "bidirectional"))
      (node (ref "R23") (pin "P$2") (pinfunction "P$2_P$2") (pintype "passive"))
      (node (ref "U17") (pin "14") (pinfunction "D3_14") (pintype "bidirectional"))
    )
    (net (code "34") (name "/GI_R_5") (class "Default")
      (node (ref "GI_R_5") (pin "P$1") (pinfunction "P$1_P$1") (pintype "bidirectional"))
      (node (ref "R22") (pin "P$2") (pinfunction "P$2_P$2") (pintype "passive"))
      (node (ref "U17") (pin "13") (pinfunction "D2_13") (pintype "bidirectional"))
    )
    (net (code "35") (name "/GI_R_6") (class "Default")
      (node (ref "GI_R_6") (pin "P$1") (pinfunction "P$1_P$1") (pintype "bidirectional"))
      (node (ref "R2") (pin "P$2") (pinfunction "P$2_P$2") (pintype "passive"))
      (node (ref "U17") (pin "12") (pinfunction "D1_12") (pintype "bidirectional"))
    )
    (net (code "36") (name "/GI_R_7") (class "Default")
      (node (ref "GI_R_7") (pin "P$1") (pinfunction "P$1_P$1") (pintype "bidirectional"))
      (node (ref "R1") (pin "P$2") (pinfunction "P$2_P$2") (pintype "passive"))
      (node (ref "U17") (pin "11") (pinfunction "D0_11") (pintype "bidirectional"))
    )
    (net (code "37") (name "/GI_R_8") (class "Default")
      (node (ref "GI_R_8") (pin "P$1") (pinfunction "P$1_P$1") (pintype "bidirectional"))
      (node (ref "R36") (pin "P$2") (pinfunction "P$2_P$2") (pintype "passive"))
      (node (ref "U18") (pin "6") (pinfunction "D7_6") (pintype "bidirectional"))
    )
    (net (code "38") (name "/GI_R_9") (class "Default")
      (node (ref "GI_R_9") (pin "P$1") (pinfunction "P$1_P$1") (pintype "bidirectional"))
      (node (ref "R35") (pin "P$2") (pinfunction "P$2_P$2") (pintype "passive"))
      (node (ref "U18") (pin "5") (pinfunction "D6_5") (pintype "bidirectional"))
    )
    (net (code "39") (name "/GI_R_10") (class "Default")
      (node (ref "GI_R_10") (pin "P$1") (pinfunction "P$1_P$1") (pintype "bidirectional"))
      (node (ref "R34") (pin "P$2") (pinfunction "P$2_P$2") (pintype "passive"))
      (node (ref "U18") (pin "4") (pinfunction "D5_4") (pintype "bidirectional"))
    )
    (net (code "40") (name "/GI_R_11") (class "Default")
      (node (ref "GI_R_11") (pin "P$1") (pinfunction "P$1_P$1") (pintype "bidirectional"))
      (node (ref "R33") (pin "P$2") (pinfunction "P$2_P$2") (pintype "passive"))
      (node (ref "U18") (pin "3") (pinfunction "D4_3") (pintype "bidirectional"))
    )
    (net (code "41") (name "/GI_R_12") (class "Default")
      (node (ref "GI_R_12") (pin "P$1") (pinfunction "P$1_P$1") (pintype "bidirectional"))
      (node (ref "R32") (pin "P$2") (pinfunction "P$2_P$2") (pintype "passive"))
      (node (ref "U18") (pin "14") (pinfunction "D3_14") (pintype "bidirectional"))
    )
    (net (code "42") (name "/GI_R_13") (class "Default")
      (node (ref "GI_R_13") (pin "P$1") (pinfunction "P$1_P$1") (pintype "bidirectional"))
      (node (ref "R31") (pin "P$2") (pinfunction "P$2_P$2") (pintype "passive"))
      (node (ref "U18") (pin "13") (pinfunction "D2_13") (pintype "bidirectional"))
    )
    (net (code "43") (name "/GI_R_14") (class "Default")
      (node (ref "GI_R_14") (pin "P$1") (pinfunction "P$1_P$1") (pintype "bidirectional"))
      (node (ref "R29") (pin "P$2") (pinfunction "P$2_P$2") (pintype "passive"))
      (node (ref "U18") (pin "12") (pinfunction "D1_12") (pintype "bidirectional"))
    )
    (net (code "44") (name "/LIGHT_C_0") (class "Default")
      (node (ref "LIGHT_C_0") (pin "P$1") (pinfunction "P$1_P$1") (pintype "bidirectional"))
      (node (ref "R85") (pin "P$2") (pinfunction "P$2_P$2") (pintype "passive"))
    )
    (net (code "45") (name "/LIGHT_C_1") (class "Default")
      (node (ref "LIGHT_C_1") (pin "P$1") (pinfunction "P$1_P$1") (pintype "bidirectional"))
      (node (ref "R86") (pin "P$2") (pinfunction "P$2_P$2") (pintype "passive"))
    )
    (net (code "46") (name "/LIGHT_C_2") (class "Default")
      (node (ref "LIGHT_C_2") (pin "P$1") (pinfunction "P$1_P$1") (pintype "bidirectional"))
      (node (ref "R87") (pin "P$2") (pinfunction "P$2_P$2") (pintype "passive"))
    )
    (net (code "47") (name "/LIGHT_C_3") (class "Default")
      (node (ref "LIGHT_C_3") (pin "P$1") (pinfunction "P$1_P$1") (pintype "bidirectional"))
      (node (ref "R88") (pin "P$2") (pinfunction "P$2_P$2") (pintype "passive"))
    )
    (net (code "48") (name "/LIGHT_C_4") (class "Default")
      (node (ref "LIGHT_C_4") (pin "P$1") (pinfunction "P$1_P$1") (pintype "bidirectional"))
      (node (ref "R89") (pin "P$2") (pinfunction "P$2_P$2") (pintype "passive"))
    )
    (net (code "49") (name "/LIGHT_C_5") (class "Default")
      (node (ref "LIGHT_C_5") (pin "P$1") (pinfunction "P$1_P$1") (pintype "bidirectional"))
      (node (ref "R90") (pin "P$2") (pinfunction "P$2_P$2") (pintype "passive"))
    )
    (net (code "50") (name "/LIGHT_C_6") (class "Default")
      (node (ref "LIGHT_C_6") (pin "P$1") (pinfunction "P$1_P$1") (pintype "bidirectional"))
      (node (ref "R91") (pin "P$2") (pinfunction "P$2_P$2") (pintype "passive"))
    )
    (net (code "51") (name "/LIGHT_C_7") (class "Default")
      (node (ref "LIGHT_C_7") (pin "P$1") (pinfunction "P$1_P$1") (pintype "bidirectional"))
      (node (ref "R92") (pin "P$2") (pinfunction "P$2_P$2") (pintype "passive"))
    )
    (net (code "52") (name "/LIGHT_R_0") (class "Default")
      (node (ref "LIGHT_R_0") (pin "P$1") (pinfunction "P$1_P$1") (pintype "bidirectional"))
      (node (ref "R76") (pin "P$2") (pinfunction "P$2_P$2") (pintype "passive"))
      (node (ref "U23") (pin "6") (pinfunction "D7_6") (pintype "bidirectional"))
    )
    (net (code "53") (name "/LIGHT_R_1") (class "Default")
      (node (ref "LIGHT_R_1") (pin "P$1") (pinfunction "P$1_P$1") (pintype "bidirectional"))
      (node (ref "R75") (pin "P$2") (pinfunction "P$2_P$2") (pintype "passive"))
      (node (ref "U23") (pin "5") (pinfunction "D6_5") (pintype "bidirectional"))
    )
    (net (code "54") (name "/LIGHT_R_2") (class "Default")
      (node (ref "LIGHT_R_2") (pin "P$1") (pinfunction "P$1_P$1") (pintype "bidirectional"))
      (node (ref "R74") (pin "P$2") (pinfunction "P$2_P$2") (pintype "passive"))
      (node (ref "U23") (pin "4") (pinfunction "D5_4") (pintype "bidirectional"))
    )
    (net (code "55") (name "/LIGHT_R_3") (class "Default")
      (node (ref "LIGHT_R_3") (pin "P$1") (pinfunction "P$1_P$1") (pintype "bidirectional"))
      (node (ref "R73") (pin "P$2") (pinfunction "P$2_P$2") (pintype "passive"))
      (node (ref "U23") (pin "3") (pinfunction "D4_3") (pintype "bidirectional"))
    )
    (net (code "56") (name "/LIGHT_R_4") (class "Default")
      (node (ref "LIGHT_R_4") (pin "P$1") (pinfunction "P$1_P$1") (pintype "bidirectional"))
      (node (ref "R72") (pin "P$2") (pinfunction "P$2_P$2") (pintype "passive"))
      (node (ref "U23") (pin "14") (pinfunction "D3_14") (pintype "bidirectional"))
    )
    (net (code "57") (name "/LIGHT_R_5") (class "Default")
      (node (ref "LIGHT_R_5") (pin "P$1") (pinfunction "P$1_P$1") (pintype "bidirectional"))
      (node (ref "R71") (pin "P$2") (pinfunction "P$2_P$2") (pintype "passive"))
      (node (ref "U23") (pin "13") (pinfunction "D2_13") (pintype "bidirectional"))
    )
    (net (code "58") (name "/LIGHT_R_6") (class "Default")
      (node (ref "LIGHT_R_6") (pin "P$1") (pinfunction "P$1_P$1") (pintype "bidirectional"))
      (node (ref "R70") (pin "P$2") (pinfunction "P$2_P$2") (pintype "passive"))
      (node (ref "U23") (pin "12") (pinfunction "D1_12") (pintype "bidirectional"))
    )
    (net (code "59") (name "/LIGHT_R_7") (class "Default")
      (node (ref "LIGHT_R_7") (pin "P$1") (pinfunction "P$1_P$1") (pintype "bidirectional"))
      (node (ref "R69") (pin "P$2") (pinfunction "P$2_P$2") (pintype "passive"))
      (node (ref "U23") (pin "11") (pinfunction "D0_11") (pintype "bidirectional"))
    )
    (net (code "60") (name "/L_FLIP_OUT") (class "Default")
      (node (ref "L_FLIP_OUT") (pin "P$1") (pinfunction "P$1_P$1") (pintype "bidirectional"))
      (node (ref "U14") (pin "15") (pinfunction "Q0_15") (pintype "bidirectional"))
    )
    (net (code "61") (name "/OPTO_1") (class "Default")
      (node (ref "OPTO_1_") (pin "P$1") (pinfunction "P$1_P$1") (pintype "bidirectional"))
      (node (ref "U26") (pin "11") (pinfunction "D0_11") (pintype "bidirectional"))
    )
    (net (code "62") (name "/OPTO_2") (class "Default")
      (node (ref "OPTO_2_") (pin "P$1") (pinfunction "P$1_P$1") (pintype "bidirectional"))
      (node (ref "U26") (pin "12") (pinfunction "D1_12") (pintype "bidirectional"))
    )
    (net (code "63") (name "/OPTO_3") (class "Default")
      (node (ref "OPTO_3_") (pin "P$1") (pinfunction "P$1_P$1") (pintype "bidirectional"))
      (node (ref "U26") (pin "13") (pinfunction "D2_13") (pintype "bidirectional"))
    )
    (net (code "64") (name "/OPTO_4") (class "Default")
      (node (ref "OPTO_4_") (pin "P$1") (pinfunction "P$1_P$1") (pintype "bidirectional"))
      (node (ref "U26") (pin "14") (pinfunction "D3_14") (pintype "bidirectional"))
    )
    (net (code "65") (name "/OPTO_5") (class "Default")
      (node (ref "OPTO_5_") (pin "P$1") (pinfunction "P$1_P$1") (pintype "bidirectional"))
      (node (ref "U26") (pin "3") (pinfunction "D4_3") (pintype "bidirectional"))
    )
    (net (code "66") (name "/OPTO_6") (class "Default")
      (node (ref "OPTO_6_") (pin "P$1") (pinfunction "P$1_P$1") (pintype "bidirectional"))
      (node (ref "U26") (pin "4") (pinfunction "D5_4") (pintype "bidirectional"))
    )
    (net (code "67") (name "/OPTO_7") (class "Default")
      (node (ref "OPTO_7_") (pin "P$1") (pinfunction "P$1_P$1") (pintype "bidirectional"))
      (node (ref "U26") (pin "5") (pinfunction "D6_5") (pintype "bidirectional"))
    )
    (net (code "68") (name "/P1") (class "Default")
      (node (ref "U1") (pin "42") (pinfunction "P1_42") (pintype "bidirectional"))
    )
    (net (code "69") (name "/P2") (class "Default")
      (node (ref "U1") (pin "43") (pinfunction "P2_43") (pintype "bidirectional"))
    )
    (net (code "70") (name "/P3") (class "Default")
      (node (ref "U1") (pin "44") (pinfunction "P3_44") (pintype "bidirectional"))
    )
    (net (code "71") (name "/P4") (class "Default")
      (node (ref "U1") (pin "1") (pinfunction "P4_1") (pintype "bidirectional"))
    )
    (net (code "72") (name "/P5") (class "Default")
      (node (ref "U1") (pin "2") (pinfunction "P5_2") (pintype "bidirectional"))
    )
    (net (code "73") (name "/P6") (class "Default")
      (node (ref "U1") (pin "3") (pinfunction "P6_3") (pintype "bidirectional"))
    )
    (net (code "74") (name "/P7") (class "Default")
      (node (ref "U1") (pin "4") (pinfunction "P7_4") (pintype "bidirectional"))
    )
    (net (code "75") (name "/P14") (class "Default")
      (node (ref "U1") (pin "15") (pinfunction "P14_15") (pintype "bidirectional"))
    )
    (net (code "76") (name "/P15") (class "Default")
      (node (ref "U1") (pin "16") (pinfunction "P15_16") (pintype "bidirectional"))
    )
    (net (code "77") (name "/P22") (class "Default")
      (node (ref "U1") (pin "25") (pinfunction "P22_25") (pintype "bidirectional"))
    )
    (net (code "78") (name "/P23") (class "Default")
      (node (ref "U1") (pin "26") (pinfunction "P23_26") (pintype "bidirectional"))
    )
    (net (code "79") (name "/P24") (class "Default")
      (node (ref "U1") (pin "31") (pinfunction "P24_31") (pintype "bidirectional"))
    )
    (net (code "80") (name "/P25") (class "Default")
      (node (ref "U1") (pin "32") (pinfunction "P25_32") (pintype "bidirectional"))
    )
    (net (code "81") (name "/P26") (class "Default")
      (node (ref "U1") (pin "33") (pinfunction "P26_33") (pintype "bidirectional"))
    )
    (net (code "82") (name "/P27") (class "Default")
      (node (ref "U1") (pin "34") (pinfunction "P27_34") (pintype "bidirectional"))
    )
    (net (code "83") (name "/PROP_AUX0") (class "Default")
      (node (ref "PROP_AUX0") (pin "P$1") (pinfunction "P$1_P$1") (pintype "bidirectional"))
      (node (ref "U28") (pin "13") (pinfunction "D2_13") (pintype "bidirectional"))
    )
    (net (code "84") (name "/PROP_AUX1") (class "Default")
      (node (ref "PROP_AUX1") (pin "P$1") (pinfunction "P$1_P$1") (pintype "bidirectional"))
      (node (ref "U28") (pin "14") (pinfunction "D3_14") (pintype "bidirectional"))
    )
    (net (code "85") (name "/PROP_~{RST}") (class "Default")
      (node (ref "C9") (pin "P$2") (pinfunction "P$2_P$2") (pintype "passive"))
      (node (ref "R5") (pin "P$1") (pinfunction "P$1_P$1") (pintype "passive"))
      (node (ref "U1") (pin "7") (pinfunction "RES'_7") (pintype "bidirectional"))
    )
    (net (code "86") (name "/PWR_ON") (class "Default")
      (node (ref "R19") (pin "1") (pinfunction "1_1") (pintype "passive"))
      (node (ref "R21") (pin "1") (pinfunction "1_1") (pintype "passive"))
      (node (ref "U1") (pin "41") (pinfunction "P0_41") (pintype "bidirectional"))
    )
    (net (code "87") (name "/RGB_BOUT_L") (class "Default")
      (node (ref "R94") (pin "P$2") (pinfunction "P$2_P$2") (pintype "passive"))
      (node (ref "RGB_BOUT_L") (pin "P$1") (pinfunction "P$1_P$1") (pintype "bidirectional"))
      (node (ref "U29") (pin "12") (pinfunction "D1_12") (pintype "bidirectional"))
    )
    (net (code "88") (name "/RGB_BOUT_R") (class "Default")
      (node (ref "R99") (pin "P$2") (pinfunction "P$2_P$2") (pintype "passive"))
      (node (ref "RGB_BOUT_R") (pin "P$1") (pinfunction "P$1_P$1") (pintype "bidirectional"))
      (node (ref "U28") (pin "5") (pinfunction "D6_5") (pintype "bidirectional"))
    )
    (net (code "89") (name "/RGB_GOUT_L") (class "Default")
      (node (ref "R93") (pin "P$2") (pinfunction "P$2_P$2") (pintype "passive"))
      (node (ref "RGB_GOUT_L") (pin "P$1") (pinfunction "P$1_P$1") (pintype "bidirectional"))
      (node (ref "U29") (pin "11") (pinfunction "D0_11") (pintype "bidirectional"))
    )
    (net (code "90") (name "/RGB_GOUT_R") (class "Default")
      (node (ref "R98") (pin "P$2") (pinfunction "P$2_P$2") (pintype "passive"))
      (node (ref "RGB_GOUT_R") (pin "P$1") (pinfunction "P$1_P$1") (pintype "bidirectional"))
      (node (ref "U28") (pin "4") (pinfunction "D5_4") (pintype "bidirectional"))
    )
    (net (code "91") (name "/RGB_ROUT_L") (class "Default")
      (node (ref "R100") (pin "P$2") (pinfunction "P$2_P$2") (pintype "passive"))
      (node (ref "RGB_ROUT_L") (pin "P$1") (pinfunction "P$1_P$1") (pintype "bidirectional"))
      (node (ref "U28") (pin "6") (pinfunction "D7_6") (pintype "bidirectional"))
    )
    (net (code "92") (name "/RGB_ROUT_R") (class "Default")
      (node (ref "R97") (pin "P$2") (pinfunction "P$2_P$2") (pintype "passive"))
      (node (ref "RGB_ROUT_R") (pin "P$1") (pinfunction "P$1_P$1") (pintype "bidirectional"))
      (node (ref "U28") (pin "3") (pinfunction "D4_3") (pintype "bidirectional"))
    )
    (net (code "93") (name "/RX") (class "Default")
      (node (ref "U1") (pin "37") (pinfunction "P30_37") (pintype "bidirectional"))
      (node (ref "U3") (pin "4") (pinfunction "RXD_4") (pintype "bidirectional"))
    )
    (net (code "94") (name "/RX_LED") (class "Default")
      (node (ref "RX") (pin "CATHODE") (pinfunction "CATHODE_CATHODE") (pintype "power_in"))
      (node (ref "U3") (pin "14") (pinfunction "CBUS1_14") (pintype "bidirectional"))
    )
    (net (code "95") (name "/RX_PIC32") (class "Default")
      (node (ref "RX_PIC32") (pin "P$1") (pinfunction "P$1_P$1") (pintype "bidirectional"))
      (node (ref "U1") (pin "11") (pinfunction "P10_11") (pintype "bidirectional"))
    )
    (net (code "96") (name "/RX_PROP") (class "Default")
      (node (ref "RX_PROP") (pin "P$1") (pinfunction "P$1_P$1") (pintype "bidirectional"))
      (node (ref "U1") (pin "14") (pinfunction "P13_14") (pintype "bidirectional"))
    )
    (net (code "97") (name "/R_FLIP_OUT") (class "Default")
      (node (ref "R_FLIP_OUT") (pin "P$1") (pinfunction "P$1_P$1") (pintype "bidirectional"))
      (node (ref "U14") (pin "7") (pinfunction "Q7_7") (pintype "bidirectional"))
    )
    (net (code "98") (name "/SCL") (class "Default")
      (node (ref "R3") (pin "P$1") (pinfunction "P$1_P$1") (pintype "passive"))
      (node (ref "U1") (pin "35") (pinfunction "P28_35") (pintype "bidirectional"))
      (node (ref "U2") (pin "6") (pinfunction "SCL_6") (pintype "bidirectional"))
      (node (ref "U9") (pin "P$5") (pinfunction "SCL_P$5") (pintype "bidirectional"))
    )
    (net (code "99") (name "/SDA") (class "Default")
      (node (ref "R4") (pin "P$1") (pinfunction "P$1_P$1") (pintype "passive"))
      (node (ref "U1") (pin "36") (pinfunction "P29_36") (pintype "bidirectional"))
      (node (ref "U2") (pin "5") (pinfunction "SDA_5") (pintype "bidirectional"))
      (node (ref "U9") (pin "P$6") (pinfunction "SDA_P$6") (pintype "bidirectional"))
    )
    (net (code "100") (name "/SD_CS") (class "Default")
      (node (ref "SD_CS") (pin "P$1") (pinfunction "P$1_P$1") (pintype "bidirectional"))
      (node (ref "U16") (pin "11") (pinfunction "D0_11") (pintype "bidirectional"))
    )
    (net (code "101") (name "/SD_DI") (class "Default")
      (node (ref "SD_DI") (pin "P$1") (pinfunction "P$1_P$1") (pintype "bidirectional"))
      (node (ref "U16") (pin "12") (pinfunction "D1_12") (pintype "bidirectional"))
    )
    (net (code "102") (name "/SD_DO") (class "Default")
      (node (ref "SD_DO") (pin "P$1") (pinfunction "P$1_P$1") (pintype "bidirectional"))
      (node (ref "U16") (pin "14") (pinfunction "D3_14") (pintype "bidirectional"))
    )
    (net (code "103") (name "/SD_SCLK") (class "Default")
      (node (ref "SD_SCLK") (pin "P$1") (pinfunction "P$1_P$1") (pintype "bidirectional"))
      (node (ref "U16") (pin "13") (pinfunction "D2_13") (pintype "bidirectional"))
    )
    (net (code "104") (name "/SERVO_0") (class "Default")
      (node (ref "SERVO_0_") (pin "P$1") (pinfunction "P$1_P$1") (pintype "bidirectional"))
      (node (ref "U27") (pin "11") (pinfunction "D0_11") (pintype "bidirectional"))
    )
    (net (code "105") (name "/SERVO_1") (class "Default")
      (node (ref "SERVO_1_") (pin "P$1") (pinfunction "P$1_P$1") (pintype "bidirectional"))
      (node (ref "U27") (pin "12") (pinfunction "D1_12") (pintype "bidirectional"))
    )
    (net (code "106") (name "/SERVO_2") (class "Default")
      (node (ref "SERVO_2_") (pin "P$1") (pinfunction "P$1_P$1") (pintype "bidirectional"))
      (node (ref "U27") (pin "13") (pinfunction "D2_13") (pintype "bidirectional"))
    )
    (net (code "107") (name "/SERVO_3") (class "Default")
      (node (ref "SERVO_3_") (pin "P$1") (pinfunction "P$1_P$1") (pintype "bidirectional"))
      (node (ref "U27") (pin "14") (pinfunction "D3_14") (pintype "bidirectional"))
    )
    (net (code "108") (name "/SERVO_4") (class "Default")
      (node (ref "SERVO_4_") (pin "P$1") (pinfunction "P$1_P$1") (pintype "bidirectional"))
      (node (ref "U27") (pin "3") (pinfunction "D4_3") (pintype "bidirectional"))
    )
    (net (code "109") (name "/SHIELD") (class "Default")
      (node (ref "J1") (pin "S3") (pinfunction "SLD_S3") (pintype "power_in"))
      (node (ref "J1") (pin "S4") (pinfunction "SLD_S4") (pintype "power_in"))
      (node (ref "J1") (pin "S5") (pinfunction "SLD_S5") (pintype "power_in"))
      (node (ref "J1") (pin "S6") (pinfunction "SLD_S6") (pintype "power_in"))
      (node (ref "L1") (pin "P$1") (pinfunction "P$1_P$1") (pintype "passive"))
    )
    (net (code "110") (name "/SOL_PWR_0") (class "Default")
      (node (ref "R60") (pin "P$2") (pinfunction "P$2_P$2") (pintype "passive"))
      (node (ref "SOL_PWR_0") (pin "P$1") (pinfunction "P$1_P$1") (pintype "bidirectional"))
      (node (ref "U21") (pin "6") (pinfunction "D7_6") (pintype "bidirectional"))
    )
    (net (code "111") (name "/SOL_PWR_1") (class "Default")
      (node (ref "R59") (pin "P$2") (pinfunction "P$2_P$2") (pintype "passive"))
      (node (ref "SOL_PWR_1") (pin "P$1") (pinfunction "P$1_P$1") (pintype "bidirectional"))
      (node (ref "U21") (pin "5") (pinfunction "D6_5") (pintype "bidirectional"))
    )
    (net (code "112") (name "/SOL_PWR_2") (class "Default")
      (node (ref "R58") (pin "P$2") (pinfunction "P$2_P$2") (pintype "passive"))
      (node (ref "SOL_PWR_2") (pin "P$1") (pinfunction "P$1_P$1") (pintype "bidirectional"))
      (node (ref "U21") (pin "4") (pinfunction "D5_4") (pintype "bidirectional"))
    )
    (net (code "113") (name "/SOL_PWR_3") (class "Default")
      (node (ref "R57") (pin "P$2") (pinfunction "P$2_P$2") (pintype "passive"))
      (node (ref "SOL_PWR_3") (pin "P$1") (pinfunction "P$1_P$1") (pintype "bidirectional"))
      (node (ref "U21") (pin "3") (pinfunction "D4_3") (pintype "bidirectional"))
    )
    (net (code "114") (name "/SOL_PWR_4") (class "Default")
      (node (ref "R56") (pin "P$2") (pinfunction "P$2_P$2") (pintype "passive"))
      (node (ref "SOL_PWR_4") (pin "P$1") (pinfunction "P$1_P$1") (pintype "bidirectional"))
      (node (ref "U21") (pin "14") (pinfunction "D3_14") (pintype "bidirectional"))
    )
    (net (code "115") (name "/SOL_PWR_5") (class "Default")
      (node (ref "R55") (pin "P$2") (pinfunction "P$2_P$2") (pintype "passive"))
      (node (ref "SOL_PWR_5") (pin "P$1") (pinfunction "P$1_P$1") (pintype "bidirectional"))
      (node (ref "U21") (pin "13") (pinfunction "D2_13") (pintype "bidirectional"))
    )
    (net (code "116") (name "/SOL_PWR_6") (class "Default")
      (node (ref "R54") (pin "P$2") (pinfunction "P$2_P$2") (pintype "passive"))
      (node (ref "SOL_PWR_6") (pin "P$1") (pinfunction "P$1_P$1") (pintype "bidirectional"))
      (node (ref "U21") (pin "12") (pinfunction "D1_12") (pintype "bidirectional"))
    )
    (net (code "117") (name "/SOL_PWR_7") (class "Default")
      (node (ref "R53") (pin "P$2") (pinfunction "P$2_P$2") (pintype "passive"))
      (node (ref "SOL_PWR_7") (pin "P$1") (pinfunction "P$1_P$1") (pintype "bidirectional"))
      (node (ref "U21") (pin "11") (pinfunction "D0_11") (pintype "bidirectional"))
    )
    (net (code "118") (name "/SOL_PWR_8") (class "Default")
      (node (ref "R52") (pin "P$2") (pinfunction "P$2_P$2") (pintype "passive"))
      (node (ref "SOL_PWR_8") (pin "P$1") (pinfunction "P$1_P$1") (pintype "bidirectional"))
      (node (ref "U20") (pin "6") (pinfunction "D7_6") (pintype "bidirectional"))
    )
    (net (code "119") (name "/SOL_PWR_9") (class "Default")
      (node (ref "R51") (pin "P$2") (pinfunction "P$2_P$2") (pintype "passive"))
      (node (ref "SOL_PWR_9") (pin "P$1") (pinfunction "P$1_P$1") (pintype "bidirectional"))
      (node (ref "U20") (pin "5") (pinfunction "D6_5") (pintype "bidirectional"))
    )
    (net (code "120") (name "/SOL_PWR_10") (class "Default")
      (node (ref "R50") (pin "P$2") (pinfunction "P$2_P$2") (pintype "passive"))
      (node (ref "SOL_PWR_10") (pin "P$1") (pinfunction "P$1_P$1") (pintype "bidirectional"))
      (node (ref "U20") (pin "4") (pinfunction "D5_4") (pintype "bidirectional"))
    )
    (net (code "121") (name "/SOL_PWR_11") (class "Default")
      (node (ref "R49") (pin "P$2") (pinfunction "P$2_P$2") (pintype "passive"))
      (node (ref "SOL_PWR_11") (pin "P$1") (pinfunction "P$1_P$1") (pintype "bidirectional"))
      (node (ref "U20") (pin "3") (pinfunction "D4_3") (pintype "bidirectional"))
    )
    (net (code "122") (name "/SOL_PWR_12") (class "Default")
      (node (ref "R48") (pin "P$2") (pinfunction "P$2_P$2") (pintype "passive"))
      (node (ref "SOL_PWR_12") (pin "P$1") (pinfunction "P$1_P$1") (pintype "bidirectional"))
      (node (ref "U20") (pin "14") (pinfunction "D3_14") (pintype "bidirectional"))
    )
    (net (code "123") (name "/SOL_PWR_13") (class "Default")
      (node (ref "R47") (pin "P$2") (pinfunction "P$2_P$2") (pintype "passive"))
      (node (ref "SOL_PWR_13") (pin "P$1") (pinfunction "P$1_P$1") (pintype "bidirectional"))
      (node (ref "U20") (pin "13") (pinfunction "D2_13") (pintype "bidirectional"))
    )
    (net (code "124") (name "/SOL_PWR_14") (class "Default")
      (node (ref "R46") (pin "P$2") (pinfunction "P$2_P$2") (pintype "passive"))
      (node (ref "SOL_PWR_14") (pin "P$1") (pinfunction "P$1_P$1") (pintype "bidirectional"))
      (node (ref "U20") (pin "12") (pinfunction "D1_12") (pintype "bidirectional"))
    )
    (net (code "125") (name "/SOL_PWR_15") (class "Default")
      (node (ref "R45") (pin "P$2") (pinfunction "P$2_P$2") (pintype "passive"))
      (node (ref "SOL_PWR_15") (pin "P$1") (pinfunction "P$1_P$1") (pintype "bidirectional"))
      (node (ref "U20") (pin "11") (pinfunction "D0_11") (pintype "bidirectional"))
    )
    (net (code "126") (name "/SOL_PWR_16") (class "Default")
      (node (ref "R44") (pin "P$2") (pinfunction "P$2_P$2") (pintype "passive"))
      (node (ref "SOL_PWR_16") (pin "P$1") (pinfunction "P$1_P$1") (pintype "bidirectional"))
      (node (ref "U19") (pin "6") (pinfunction "D7_6") (pintype "bidirectional"))
    )
    (net (code "127") (name "/SOL_PWR_17") (class "Default")
      (node (ref "R43") (pin "P$2") (pinfunction "P$2_P$2") (pintype "passive"))
      (node (ref "SOL_PWR_17") (pin "P$1") (pinfunction "P$1_P$1") (pintype "bidirectional"))
      (node (ref "U19") (pin "5") (pinfunction "D6_5") (pintype "bidirectional"))
    )
    (net (code "128") (name "/SOL_PWR_18") (class "Default")
      (node (ref "R42") (pin "P$2") (pinfunction "P$2_P$2") (pintype "passive"))
      (node (ref "SOL_PWR_18") (pin "P$1") (pinfunction "P$1_P$1") (pintype "bidirectional"))
      (node (ref "U19") (pin "4") (pinfunction "D5_4") (pintype "bidirectional"))
    )
    (net (code "129") (name "/SOL_PWR_19") (class "Default")
      (node (ref "R41") (pin "P$2") (pinfunction "P$2_P$2") (pintype "passive"))
      (node (ref "SOL_PWR_19") (pin "P$1") (pinfunction "P$1_P$1") (pintype "bidirectional"))
      (node (ref "U19") (pin "3") (pinfunction "D4_3") (pintype "bidirectional"))
    )
    (net (code "130") (name "/SOL_PWR_20") (class "Default")
      (node (ref "R40") (pin "P$2") (pinfunction "P$2_P$2") (pintype "passive"))
      (node (ref "SOL_PWR_20") (pin "P$1") (pinfunction "P$1_P$1") (pintype "bidirectional"))
      (node (ref "U19") (pin "14") (pinfunction "D3_14") (pintype "bidirectional"))
    )
    (net (code "131") (name "/SOL_PWR_21") (class "Default")
      (node (ref "R39") (pin "P$2") (pinfunction "P$2_P$2") (pintype "passive"))
      (node (ref "SOL_PWR_21") (pin "P$1") (pinfunction "P$1_P$1") (pintype "bidirectional"))
      (node (ref "U19") (pin "13") (pinfunction "D2_13") (pintype "bidirectional"))
    )
    (net (code "132") (name "/SOL_PWR_22") (class "Default")
      (node (ref "R38") (pin "P$2") (pinfunction "P$2_P$2") (pintype "passive"))
      (node (ref "SOL_PWR_22") (pin "P$1") (pinfunction "P$1_P$1") (pintype "bidirectional"))
      (node (ref "U19") (pin "12") (pinfunction "D1_12") (pintype "bidirectional"))
    )
    (net (code "133") (name "/SOL_PWR_23") (class "Default")
      (node (ref "R37") (pin "P$2") (pinfunction "P$2_P$2") (pintype "passive"))
      (node (ref "SOL_PWR_23") (pin "P$1") (pinfunction "P$1_P$1") (pintype "bidirectional"))
      (node (ref "U19") (pin "11") (pinfunction "D0_11") (pintype "bidirectional"))
    )
    (net (code "134") (name "/ST_BU_OUT") (class "Default")
      (node (ref "ST_BU_OUT") (pin "P$1") (pinfunction "P$1_P$1") (pintype "bidirectional"))
    )
    (net (code "135") (name "/ST_LI") (class "Default")
      (node (ref "ST_LI_") (pin "P$1") (pinfunction "P$1_P$1") (pintype "bidirectional"))
      (node (ref "U16") (pin "5") (pinfunction "D6_5") (pintype "bidirectional"))
    )
    (net (code "136") (name "/SW_C_0") (class "Default")
      (node (ref "R61") (pin "P$2") (pinfunction "P$2_P$2") (pintype "passive"))
      (node (ref "SW_C_0") (pin "P$1") (pinfunction "P$1_P$1") (pintype "bidirectional"))
      (node (ref "U22") (pin "11") (pinfunction "D0_11") (pintype "bidirectional"))
    )
    (net (code "137") (name "/SW_C_1") (class "Default")
      (node (ref "R62") (pin "P$2") (pinfunction "P$2_P$2") (pintype "passive"))
      (node (ref "SW_C_1") (pin "P$1") (pinfunction "P$1_P$1") (pintype "bidirectional"))
      (node (ref "U22") (pin "12") (pinfunction "D1_12") (pintype "bidirectional"))
    )
    (net (code "138") (name "/SW_C_2") (class "Default")
      (node (ref "R63") (pin "P$2") (pinfunction "P$2_P$2") (pintype "passive"))
      (node (ref "SW_C_2") (pin "P$1") (pinfunction "P$1_P$1") (pintype "bidirectional"))
      (node (ref "U22") (pin "13") (pinfunction "D2_13") (pintype "bidirectional"))
    )
    (net (code "139") (name "/SW_C_3") (class "Default")
      (node (ref "R64") (pin "P$2") (pinfunction "P$2_P$2") (pintype "passive"))
      (node (ref "SW_C_3") (pin "P$1") (pinfunction "P$1_P$1") (pintype "bidirectional"))
      (node (ref "U22") (pin "14") (pinfunction "D3_14") (pintype "bidirectional"))
    )
    (net (code "140") (name "/SW_C_4") (class "Default")
      (node (ref "R65") (pin "P$2") (pinfunction "P$2_P$2") (pintype "passive"))
      (node (ref "SW_C_4") (pin "P$1") (pinfunction "P$1_P$1") (pintype "bidirectional"))
      (node (ref "U22") (pin "3") (pinfunction "D4_3") (pintype "bidirectional"))
    )
    (net (code "141") (name "/SW_C_5") (class "Default")
      (node (ref "R66") (pin "P$2") (pinfunction "P$2_P$2") (pintype "passive"))
      (node (ref "SW_C_5") (pin "P$1") (pinfunction "P$1_P$1") (pintype "bidirectional"))
      (node (ref "U22") (pin "4") (pinfunction "D5_4") (pintype "bidirectional"))
    )
    (net (code "142") (name "/SW_C_6") (class "Default")
      (node (ref "R67") (pin "P$2") (pinfunction "P$2_P$2") (pintype "passive"))
      (node (ref "SW_C_6") (pin "P$1") (pinfunction "P$1_P$1") (pintype "bidirectional"))
      (node (ref "U22") (pin "5") (pinfunction "D6_5") (pintype "bidirectional"))
    )
    (net (code "143") (name "/SW_C_7") (class "Default")
      (node (ref "R68") (pin "P$2") (pinfunction "P$2_P$2") (pintype "passive"))
      (node (ref "SW_C_7") (pin "P$1") (pinfunction "P$1_P$1") (pintype "bidirectional"))
      (node (ref "U22") (pin "6") (pinfunction "D7_6") (pintype "bidirectional"))
    )
    (net (code "144") (name "/SW_R_0") (class "Default")
      (node (ref "SW_R_0") (pin "P$1") (pinfunction "P$1_P$1") (pintype "bidirectional"))
      (node (ref "U15") (pin "7") (pinfunction "Q7_7") (pintype "bidirectional"))
    )
    (net (code "145") (name "/SW_R_1") (class "Default")
      (node (ref "SW_R_1") (pin "P$1") (pinfunction "P$1_P$1") (pintype "bidirectional"))
      (node (ref "U15") (pin "6") (pinfunction "Q6_6") (pintype "bidirectional"))
    )
    (net (code "146") (name "/SW_R_2") (class "Default")
      (node (ref "SW_R_2") (pin "P$1") (pinfunction "P$1_P$1") (pintype "bidirectional"))
      (node (ref "U15") (pin "5") (pinfunction "Q5_5") (pintype "bidirectional"))
    )
    (net (code "147") (name "/SW_R_3") (class "Default")
      (node (ref "SW_R_3") (pin "P$1") (pinfunction "P$1_P$1") (pintype "bidirectional"))
      (node (ref "U15") (pin "4") (pinfunction "Q4_4") (pintype "bidirectional"))
    )
    (net (code "148") (name "/SW_R_4") (class "Default")
      (node (ref "SW_R_4") (pin "P$1") (pinfunction "P$1_P$1") (pintype "bidirectional"))
      (node (ref "U15") (pin "3") (pinfunction "Q3_3") (pintype "bidirectional"))
    )
    (net (code "149") (name "/SW_R_5") (class "Default")
      (node (ref "SW_R_5") (pin "P$1") (pinfunction "P$1_P$1") (pintype "bidirectional"))
      (node (ref "U15") (pin "2") (pinfunction "Q2_2") (pintype "bidirectional"))
    )
    (net (code "150") (name "/SW_R_6") (class "Default")
      (node (ref "SW_R_6") (pin "P$1") (pinfunction "P$1_P$1") (pintype "bidirectional"))
      (node (ref "U15") (pin "1") (pinfunction "Q1_1") (pintype "bidirectional"))
    )
    (net (code "151") (name "/SW_R_7") (class "Default")
      (node (ref "SW_R_7") (pin "P$1") (pinfunction "P$1_P$1") (pintype "bidirectional"))
      (node (ref "U15") (pin "15") (pinfunction "Q0_15") (pintype "bidirectional"))
    )
    (net (code "152") (name "/S_L") (class "Default")
      (node (ref "S_L") (pin "P$1") (pinfunction "P$1_P$1") (pintype "bidirectional"))
      (node (ref "U16") (pin "3") (pinfunction "D4_3") (pintype "bidirectional"))
    )
    (net (code "153") (name "/S_R") (class "Default")
      (node (ref "S_R") (pin "P$1") (pinfunction "P$1_P$1") (pintype "bidirectional"))
      (node (ref "U16") (pin "4") (pinfunction "D5_4") (pintype "bidirectional"))
    )
    (net (code "154") (name "/TILT_OUT") (class "Default")
      (node (ref "TILT_OUT") (pin "P$1") (pinfunction "P$1_P$1") (pintype "bidirectional"))
      (node (ref "U14") (pin "1") (pinfunction "Q1_1") (pintype "bidirectional"))
    )
    (net (code "155") (name "/TX") (class "Default")
      (node (ref "U1") (pin "38") (pinfunction "P31_38") (pintype "bidirectional"))
      (node (ref "U3") (pin "1") (pinfunction "TXD_1") (pintype "bidirectional"))
    )
    (net (code "156") (name "/TX_LED") (class "Default")
      (node (ref "TX") (pin "CATHODE") (pinfunction "CATHODE_CATHODE") (pintype "power_in"))
      (node (ref "U3") (pin "15") (pinfunction "CBUS0_15") (pintype "bidirectional"))
    )
    (net (code "157") (name "/TX_PIC32") (class "Default")
      (node (ref "TX_PIC32") (pin "P$1") (pinfunction "P$1_P$1") (pintype "bidirectional"))
      (node (ref "U1") (pin "10") (pinfunction "P9_10") (pintype "bidirectional"))
    )
    (net (code "158") (name "/TX_PROP") (class "Default")
      (node (ref "TX_PROP") (pin "P$1") (pinfunction "P$1_P$1") (pintype "bidirectional"))
      (node (ref "U1") (pin "13") (pinfunction "P12_13") (pintype "bidirectional"))
    )
    (net (code "159") (name "/USB_~{RST}") (class "Default")
      (node (ref "C9") (pin "P$1") (pinfunction "P$1_P$1") (pintype "passive"))
      (node (ref "U3") (pin "2") (pinfunction "~{RTS}_2") (pintype "bidirectional"))
    )
    (net (code "160") (name "/USER_0_OUT") (class "Default")
      (node (ref "U14") (pin "6") (pinfunction "Q6_6") (pintype "bidirectional"))
      (node (ref "USER_0_OUT") (pin "P$1") (pinfunction "P$1_P$1") (pintype "bidirectional"))
    )
    (net (code "161") (name "/VBUS_SENSE") (class "Default")
      (node (ref "R13") (pin "P$1") (pinfunction "P$1_P$1") (pintype "passive"))
      (node (ref "R9") (pin "P$2") (pinfunction "P$2_P$2") (pintype "passive"))
      (node (ref "U3") (pin "16") (pinfunction "CBUS3_16") (pintype "bidirectional"))
    )
    (net (code "162") (name "/VIN_CUR") (class "Default")
      (node (ref "R14") (pin "2") (pinfunction "2_2") (pintype "passive"))
      (node (ref "R18") (pin "1") (pinfunction "1_1") (pintype "passive"))
      (node (ref "U10") (pin "5") (pinfunction "DRAIN_5") (pintype "bidirectional"))
      (node (ref "U10") (pin "6") (pinfunction "DRAIN_6") (pintype "bidirectional"))
      (node (ref "U10") (pin "7") (pinfunction "DRAIN_7") (pintype "bidirectional"))
      (node (ref "U10") (pin "8") (pinfunction "DRAIN_8") (pintype "bidirectional"))
      (node (ref "U7") (pin "4") (pinfunction "VIN-_4") (pintype "bidirectional"))
    )
    (net (code "163") (name "/V_USB_0") (class "Default")
      (node (ref "J1") (pin "1") (pinfunction "5V_1") (pintype "power_in"))
      (node (ref "R10") (pin "P$2") (pinfunction "P$2_P$2") (pintype "passive"))
      (node (ref "R13") (pin "P$2") (pinfunction "P$2_P$2") (pintype "passive"))
      (node (ref "U4") (pin "5") (pinfunction "VB_5") (pintype "bidirectional"))
    )
    (net (code "164") (name "/X0") (class "Default")
      (node (ref "U1") (pin "29") (pinfunction "X0_29") (pintype "bidirectional"))
      (node (ref "X1") (pin "P$1") (pinfunction "X0_P$1") (pintype "bidirectional"))
    )
    (net (code "165") (name "/X1") (class "Default")
      (node (ref "U1") (pin "28") (pinfunction "X1_28") (pintype "bidirectional"))
      (node (ref "X1") (pin "P$3") (pinfunction "X1_P$3") (pintype "bidirectional"))
    )
    (net (code "166") (name "/~{RES}_PROP") (class "Default")
      (node (ref "!RES!_PROP") (pin "P$1") (pinfunction "P$1_P$1") (pintype "bidirectional"))
      (node (ref "U1") (pin "12") (pinfunction "P11_12") (pintype "bidirectional"))
    )
    (net (code "167") (name "/~{RST}_PIC32") (class "Default")
      (node (ref "!RST!_PIC32") (pin "P$1") (pinfunction "P$1_P$1") (pintype "bidirectional"))
      (node (ref "U1") (pin "9") (pinfunction "P8_9") (pintype "bidirectional"))
    )
    (net (code "168") (name "3.3V") (class "Default")
      (node (ref "C1") (pin "1") (pinfunction "1_1") (pintype "passive"))
      (node (ref "C11") (pin "P$1") (pinfunction "P$1_P$1") (pintype "passive"))
      (node (ref "C12") (pin "P$1") (pinfunction "P$1_P$1") (pintype "passive"))
      (node (ref "C14") (pin "P$1") (pinfunction "P$1_P$1") (pintype "passive"))
      (node (ref "C18") (pin "P$1") (pinfunction "P$1_P$1") (pintype "passive"))
      (node (ref "C2") (pin "P$1") (pinfunction "P$1_P$1") (pintype "passive"))
      (node (ref "C23") (pin "1") (pinfunction "1_1") (pintype "passive"))
      (node (ref "C24") (pin "1") (pinfunction "1_1") (pintype "passive"))
      (node (ref "C25") (pin "P$1") (pinfunction "P$1_P$1") (pintype "passive"))
      (node (ref "C26") (pin "P$1") (pinfunction "P$1_P$1") (pintype "passive"))
      (node (ref "C27") (pin "P$1") (pinfunction "P$1_P$1") (pintype "passive"))
      (node (ref "C28") (pin "P$1") (pinfunction "P$1_P$1") (pintype "passive"))
      (node (ref "C29") (pin "P$1") (pinfunction "P$1_P$1") (pintype "passive"))
      (node (ref "C3") (pin "P$1") (pinfunction "P$1_P$1") (pintype "passive"))
      (node (ref "C30") (pin "P$1") (pinfunction "P$1_P$1") (pintype "passive"))
      (node (ref "C31") (pin "P$1") (pinfunction "P$1_P$1") (pintype "passive"))
      (node (ref "C32") (pin "P$1") (pinfunction "P$1_P$1") (pintype "passive"))
      (node (ref "C33") (pin "P$1") (pinfunction "P$1_P$1") (pintype "passive"))
      (node (ref "C34") (pin "P$1") (pinfunction "P$1_P$1") (pintype "passive"))
      (node (ref "C35") (pin "P$1") (pinfunction "P$1_P$1") (pintype "passive"))
      (node (ref "C36") (pin "P$1") (pinfunction "P$1_P$1") (pintype "passive"))
      (node (ref "C37") (pin "P$1") (pinfunction "P$1_P$1") (pintype "passive"))
      (node (ref "C38") (pin "P$1") (pinfunction "P$1_P$1") (pintype "passive"))
      (node (ref "C39") (pin "P$1") (pinfunction "P$1_P$1") (pintype "passive"))
      (node (ref "C4") (pin "P$1") (pinfunction "P$1_P$1") (pintype "passive"))
      (node (ref "C5") (pin "P$1") (pinfunction "P$1_P$1") (pintype "passive"))
      (node (ref "C6") (pin "P$1") (pinfunction "P$1_P$1") (pintype "passive"))
      (node (ref "R1") (pin "P$1") (pinfunction "P$1_P$1") (pintype "passive"))
      (node (ref "R100") (pin "P$1") (pinfunction "P$1_P$1") (pintype "passive"))
      (node (ref "R11") (pin "P$2") (pinfunction "P$2_P$2") (pintype "passive"))
      (node (ref "R12") (pin "P$2") (pinfunction "P$2_P$2") (pintype "passive"))
      (node (ref "R2") (pin "P$1") (pinfunction "P$1_P$1") (pintype "passive"))
      (node (ref "R22") (pin "P$1") (pinfunction "P$1_P$1") (pintype "passive"))
      (node (ref "R23") (pin "P$1") (pinfunction "P$1_P$1") (pintype "passive"))
      (node (ref "R24") (pin "P$1") (pinfunction "P$1_P$1") (pintype "passive"))
      (node (ref "R25") (pin "P$1") (pinfunction "P$1_P$1") (pintype "passive"))
      (node (ref "R26") (pin "P$1") (pinfunction "P$1_P$1") (pintype "passive"))
      (node (ref "R27") (pin "P$1") (pinfunction "P$1_P$1") (pintype "passive"))
      (node (ref "R28") (pin "P$1") (pinfunction "P$1_P$1") (pintype "passive"))
      (node (ref "R29") (pin "P$1") (pinfunction "P$1_P$1") (pintype "passive"))
      (node (ref "R3") (pin "P$2") (pinfunction "P$2_P$2") (pintype "passive"))
      (node (ref "R30") (pin "P$2") (pinfunction "P$2_P$2") (pintype "passive"))
      (node (ref "R31") (pin "P$1") (pinfunction "P$1_P$1") (pintype "passive"))
      (node (ref "R32") (pin "P$1") (pinfunction "P$1_P$1") (pintype "passive"))
      (node (ref "R33") (pin "P$1") (pinfunction "P$1_P$1") (pintype "passive"))
      (node (ref "R34") (pin "P$1") (pinfunction "P$1_P$1") (pintype "passive"))
      (node (ref "R35") (pin "P$1") (pinfunction "P$1_P$1") (pintype "passive"))
      (node (ref "R36") (pin "P$1") (pinfunction "P$1_P$1") (pintype "passive"))
      (node (ref "R37") (pin "P$1") (pinfunction "P$1_P$1") (pintype "passive"))
      (node (ref "R38") (pin "P$1") (pinfunction "P$1_P$1") (pintype "passive"))
      (node (ref "R39") (pin "P$1") (pinfunction "P$1_P$1") (pintype "passive"))
      (node (ref "R4") (pin "P$2") (pinfunction "P$2_P$2") (pintype "passive"))
      (node (ref "R40") (pin "P$1") (pinfunction "P$1_P$1") (pintype "passive"))
      (node (ref "R41") (pin "P$1") (pinfunction "P$1_P$1") (pintype "passive"))
      (node (ref "R42") (pin "P$1") (pinfunction "P$1_P$1") (pintype "passive"))
      (node (ref "R43") (pin "P$1") (pinfunction "P$1_P$1") (pintype "passive"))
      (node (ref "R44") (pin "P$1") (pinfunction "P$1_P$1") (pintype "passive"))
      (node (ref "R45") (pin "P$1") (pinfunction "P$1_P$1") (pintype "passive"))
      (node (ref "R46") (pin "P$1") (pinfunction "P$1_P$1") (pintype "passive"))
      (node (ref "R47") (pin "P$1") (pinfunction "P$1_P$1") (pintype "passive"))
      (node (ref "R48") (pin "P$1") (pinfunction "P$1_P$1") (pintype "passive"))
      (node (ref "R49") (pin "P$1") (pinfunction "P$1_P$1") (pintype "passive"))
      (node (ref "R5") (pin "P$2") (pinfunction "P$2_P$2") (pintype "passive"))
      (node (ref "R50") (pin "P$1") (pinfunction "P$1_P$1") (pintype "passive"))
      (node (ref "R51") (pin "P$1") (pinfunction "P$1_P$1") (pintype "passive"))
      (node (ref "R52") (pin "P$1") (pinfunction "P$1_P$1") (pintype "passive"))
      (node (ref "R53") (pin "P$1") (pinfunction "P$1_P$1") (pintype "passive"))
      (node (ref "R54") (pin "P$1") (pinfunction "P$1_P$1") (pintype "passive"))
      (node (ref "R55") (pin "P$1") (pinfunction "P$1_P$1") (pintype "passive"))
      (node (ref "R56") (pin "P$1") (pinfunction "P$1_P$1") (pintype "passive"))
      (node (ref "R57") (pin "P$1") (pinfunction "P$1_P$1") (pintype "passive"))
      (node (ref "R58") (pin "P$1") (pinfunction "P$1_P$1") (pintype "passive"))
      (node (ref "R59") (pin "P$1") (pinfunction "P$1_P$1") (pintype "passive"))
      (node (ref "R60") (pin "P$1") (pinfunction "P$1_P$1") (pintype "passive"))
      (node (ref "R61") (pin "P$1") (pinfunction "P$1_P$1") (pintype "passive"))
      (node (ref "R62") (pin "P$1") (pinfunction "P$1_P$1") (pintype "passive"))
      (node (ref "R63") (pin "P$1") (pinfunction "P$1_P$1") (pintype "passive"))
      (node (ref "R64") (pin "P$1") (pinfunction "P$1_P$1") (pintype "passive"))
      (node (ref "R65") (pin "P$1") (pinfunction "P$1_P$1") (pintype "passive"))
      (node (ref "R66") (pin "P$1") (pinfunction "P$1_P$1") (pintype "passive"))
      (node (ref "R67") (pin "P$1") (pinfunction "P$1_P$1") (pintype "passive"))
      (node (ref "R68") (pin "P$1") (pinfunction "P$1_P$1") (pintype "passive"))
      (node (ref "R69") (pin "P$1") (pinfunction "P$1_P$1") (pintype "passive"))
      (node (ref "R70") (pin "P$1") (pinfunction "P$1_P$1") (pintype "passive"))
      (node (ref "R71") (pin "P$1") (pinfunction "P$1_P$1") (pintype "passive"))
      (node (ref "R72") (pin "P$1") (pinfunction "P$1_P$1") (pintype "passive"))
      (node (ref "R73") (pin "P$1") (pinfunction "P$1_P$1") (pintype "passive"))
      (node (ref "R74") (pin "P$1") (pinfunction "P$1_P$1") (pintype "passive"))
      (node (ref "R75") (pin "P$1") (pinfunction "P$1_P$1") (pintype "passive"))
      (node (ref "R76") (pin "P$1") (pinfunction "P$1_P$1") (pintype "passive"))
      (node (ref "R93") (pin "P$1") (pinfunction "P$1_P$1") (pintype "passive"))
      (node (ref "R94") (pin "P$1") (pinfunction "P$1_P$1") (pintype "passive"))
      (node (ref "R97") (pin "P$1") (pinfunction "P$1_P$1") (pintype "passive"))
      (node (ref "R98") (pin "P$1") (pinfunction "P$1_P$1") (pintype "passive"))
      (node (ref "R99") (pin "P$1") (pinfunction "P$1_P$1") (pintype "passive"))
      (node (ref "U1") (pin "18") (pinfunction "VDD_18") (pintype "power_in"))
      (node (ref "U1") (pin "30") (pinfunction "VDD_30") (pintype "power_in"))
      (node (ref "U1") (pin "40") (pinfunction "VDD_40") (pintype "power_in"))
      (node (ref "U1") (pin "8") (pinfunction "VDD_8") (pintype "power_in"))
      (node (ref "U14") (pin "10") (pinfunction "MR_10") (pintype "bidirectional"))
      (node (ref "U14") (pin "16") (pinfunction "VCC_16") (pintype "bidirectional"))
      (node (ref "U15") (pin "10") (pinfunction "MR_10") (pintype "bidirectional"))
      (node (ref "U15") (pin "16") (pinfunction "VCC_16") (pintype "bidirectional"))
      (node (ref "U16") (pin "16") (pinfunction "VCC_16") (pintype "bidirectional"))
      (node (ref "U17") (pin "16") (pinfunction "VCC_16") (pintype "bidirectional"))
      (node (ref "U18") (pin "16") (pinfunction "VCC_16") (pintype "bidirectional"))
      (node (ref "U19") (pin "16") (pinfunction "VCC_16") (pintype "bidirectional"))
      (node (ref "U2") (pin "8") (pinfunction "VCC_8") (pintype "bidirectional"))
      (node (ref "U20") (pin "16") (pinfunction "VCC_16") (pintype "bidirectional"))
      (node (ref "U21") (pin "16") (pinfunction "VCC_16") (pintype "bidirectional"))
      (node (ref "U22") (pin "16") (pinfunction "VCC_16") (pintype "bidirectional"))
      (node (ref "U23") (pin "16") (pinfunction "VCC_16") (pintype "bidirectional"))
      (node (ref "U24") (pin "16") (pinfunction "VCC_16") (pintype "bidirectional"))
      (node (ref "U26") (pin "16") (pinfunction "VCC_16") (pintype "bidirectional"))
      (node (ref "U27") (pin "16") (pinfunction "VCC_16") (pintype "bidirectional"))
      (node (ref "U28") (pin "16") (pinfunction "VCC_16") (pintype "bidirectional"))
      (node (ref "U29") (pin "16") (pinfunction "VCC_16") (pintype "bidirectional"))
      (node (ref "U3") (pin "12") (pinfunction "VCC_12") (pintype "bidirectional"))
      (node (ref "U30") (pin "16") (pinfunction "VCC_16") (pintype "bidirectional"))
      (node (ref "U5") (pin "TAB") (pinfunction "OUT_TAB") (pintype "bidirectional"))
      (node (ref "U7") (pin "5") (pinfunction "V+_5") (pintype "bidirectional"))
      (node (ref "U8") (pin "5") (pinfunction "V+_5") (pintype "bidirectional"))
      (node (ref "U9") (pin "P$8") (pinfunction "VCC_P$8") (pintype "bidirectional"))
    )
    (net (code "169") (name "5.0V") (class "Default")
      (node (ref "C16") (pin "P$1") (pinfunction "P$1_P$1") (pintype "passive"))
      (node (ref "C20") (pin "P$1") (pinfunction "P$1_P$1") (pintype "passive"))
      (node (ref "R15") (pin "1") (pinfunction "1_1") (pintype "passive"))
      (node (ref "U6") (pin "TAB") (pinfunction "OUT_TAB") (pintype "bidirectional"))
      (node (ref "U8") (pin "3") (pinfunction "VIN+_3") (pintype "bidirectional"))
    )
    (net (code "170") (name "5.0V_SW") (class "Default")
      (node (ref "5V") (pin "P$1") (pinfunction "P$1_P$1") (pintype "bidirectional"))
      (node (ref "U11") (pin "1") (pinfunction "SOURCE_1") (pintype "bidirectional"))
      (node (ref "U11") (pin "2") (pinfunction "SOURCE_2") (pintype "bidirectional"))
      (node (ref "U11") (pin "3") (pinfunction "SOURCE_3") (pintype "bidirectional"))
    )
    (net (code "171") (name "12.0V_SW") (class "Default")
      (node (ref "12V") (pin "P$1") (pinfunction "P$1_P$1") (pintype "bidirectional"))
      (node (ref "U10") (pin "1") (pinfunction "SOURCE_1") (pintype "bidirectional"))
      (node (ref "U10") (pin "2") (pinfunction "SOURCE_2") (pintype "bidirectional"))
      (node (ref "U10") (pin "3") (pinfunction "SOURCE_3") (pintype "bidirectional"))
    )
    (net (code "172") (name "GND") (class "Default")
      (node (ref "C1") (pin "2") (pinfunction "2_2") (pintype "passive"))
      (node (ref "C10") (pin "P$2") (pinfunction "P$2_P$2") (pintype "passive"))
      (node (ref "C11") (pin "P$2") (pinfunction "P$2_P$2") (pintype "passive"))
      (node (ref "C12") (pin "P$2") (pinfunction "P$2_P$2") (pintype "passive"))
      (node (ref "C13") (pin "P$2") (pinfunction "P$2_P$2") (pintype "passive"))
      (node (ref "C14") (pin "P$2") (pinfunction "P$2_P$2") (pintype "passive"))
      (node (ref "C15") (pin "P$2") (pinfunction "P$2_P$2") (pintype "passive"))
      (node (ref "C16") (pin "P$2") (pinfunction "P$2_P$2") (pintype "passive"))
      (node (ref "C17") (pin "P$2") (pinfunction "P$2_P$2") (pintype "passive"))
      (node (ref "C18") (pin "P$2") (pinfunction "P$2_P$2") (pintype "passive"))
      (node (ref "C19") (pin "P$2") (pinfunction "P$2_P$2") (pintype "passive"))
      (node (ref "C2") (pin "P$2") (pinfunction "P$2_P$2") (pintype "passive"))
      (node (ref "C20") (pin "P$2") (pinfunction "P$2_P$2") (pintype "passive"))
      (node (ref "C21") (pin "2") (pinfunction "2_2") (pintype "passive"))
      (node (ref "C22") (pin "2") (pinfunction "2_2") (pintype "passive"))
      (node (ref "C23") (pin "2") (pinfunction "2_2") (pintype "passive"))
      (node (ref "C24") (pin "2") (pinfunction "2_2") (pintype "passive"))
      (node (ref "C25") (pin "P$2") (pinfunction "P$2_P$2") (pintype "passive"))
      (node (ref "C26") (pin "P$2") (pinfunction "P$2_P$2") (pintype "passive"))
      (node (ref "C27") (pin "P$2") (pinfunction "P$2_P$2") (pintype "passive"))
      (node (ref "C28") (pin "P$2") (pinfunction "P$2_P$2") (pintype "passive"))
      (node (ref "C29") (pin "P$2") (pinfunction "P$2_P$2") (pintype "passive"))
      (node (ref "C3") (pin "P$2") (pinfunction "P$2_P$2") (pintype "passive"))
      (node (ref "C30") (pin "P$2") (pinfunction "P$2_P$2") (pintype "passive"))
      (node (ref "C31") (pin "P$2") (pinfunction "P$2_P$2") (pintype "passive"))
      (node (ref "C32") (pin "P$2") (pinfunction "P$2_P$2") (pintype "passive"))
      (node (ref "C33") (pin "P$2") (pinfunction "P$2_P$2") (pintype "passive"))
      (node (ref "C34") (pin "P$2") (pinfunction "P$2_P$2") (pintype "passive"))
      (node (ref "C35") (pin "P$2") (pinfunction "P$2_P$2") (pintype "passive"))
      (node (ref "C36") (pin "P$2") (pinfunction "P$2_P$2") (pintype "passive"))
      (node (ref "C37") (pin "P$2") (pinfunction "P$2_P$2") (pintype "passive"))
      (node (ref "C38") (pin "P$2") (pinfunction "P$2_P$2") (pintype "passive"))
      (node (ref "C39") (pin "P$2") (pinfunction "P$2_P$2") (pintype "passive"))
      (node (ref "C4") (pin "P$2") (pinfunction "P$2_P$2") (pintype "passive"))
      (node (ref "C5") (pin "P$2") (pinfunction "P$2_P$2") (pintype "passive"))
      (node (ref "C6") (pin "P$2") (pinfunction "P$2_P$2") (pintype "passive"))
      (node (ref "C7") (pin "P$2") (pinfunction "P$2_P$2") (pintype "passive"))
      (node (ref "C8") (pin "P$2") (pinfunction "P$2_P$2") (pintype "passive"))
      (node (ref "EXT_PWR") (pin "CATHODE") (pinfunction "CATHODE_CATHODE") (pintype "power_in"))
      (node (ref "GND") (pin "P$1") (pinfunction "P$1_P$1") (pintype "bidirectional"))
      (node (ref "J1") (pin "5") (pinfunction "GND_5") (pintype "power_in"))
      (node (ref "J2") (pin "SLEEVE1") (pinfunction "SLEEVE_SLEEVE1") (pintype "power_in"))
      (node (ref "J2") (pin "SLEEVE2") (pinfunction "SLEEVE_SHUNT_SLEEVE2") (pintype "power_in"))
      (node (ref "L1") (pin "P$2") (pinfunction "P$2_P$2") (pintype "passive"))
      (node (ref "R16") (pin "1") (pinfunction "1_1") (pintype "passive"))
      (node (ref "R17") (pin "1") (pinfunction "1_1") (pintype "passive"))
      (node (ref "R77") (pin "P$1") (pinfunction "P$1_P$1") (pintype "passive"))
      (node (ref "R78") (pin "P$1") (pinfunction "P$1_P$1") (pintype "passive"))
      (node (ref "R79") (pin "P$1") (pinfunction "P$1_P$1") (pintype "passive"))
      (node (ref "R80") (pin "P$1") (pinfunction "P$1_P$1") (pintype "passive"))
      (node (ref "R81") (pin "P$1") (pinfunction "P$1_P$1") (pintype "passive"))
      (node (ref "R82") (pin "P$1") (pinfunction "P$1_P$1") (pintype "passive"))
      (node (ref "R83") (pin "P$1") (pinfunction "P$1_P$1") (pintype "passive"))
      (node (ref "R84") (pin "P$1") (pinfunction "P$1_P$1") (pintype "passive"))
      (node (ref "R9") (pin "P$1") (pinfunction "P$1_P$1") (pintype "passive"))
      (node (ref "SOL_GND") (pin "P$1") (pinfunction "P$1_P$1") (pintype "bidirectional"))
      (node (ref "TVS1") (pin "P$2") (pinfunction "P$2_P$2") (pintype "bidirectional"))
      (node (ref "U1") (pin "17") (pinfunction "VSS_17") (pintype "power_in"))
      (node (ref "U1") (pin "27") (pinfunction "VSS_27") (pintype "power_in"))
      (node (ref "U1") (pin "39") (pinfunction "VSS_39") (pintype "power_in"))
      (node (ref "U1") (pin "5") (pinfunction "VSS_5") (pintype "power_in"))
      (node (ref "U1") (pin "6") (pinfunction "BOE'_6") (pintype "bidirectional"))
      (node (ref "U12") (pin "2") (pinfunction "EMITTER_2") (pintype "bidirectional"))
      (node (ref "U13") (pin "2") (pinfunction "EMITTER_2") (pintype "bidirectional"))
      (node (ref "U14") (pin "13") (pinfunction "OE_13") (pintype "bidirectional"))
      (node (ref "U14") (pin "8") (pinfunction "GND_8") (pintype "bidirectional"))
      (node (ref "U15") (pin "13") (pinfunction "OE_13") (pintype "bidirectional"))
      (node (ref "U15") (pin "8") (pinfunction "GND_8") (pintype "bidirectional"))
      (node (ref "U16") (pin "15") (pinfunction "C_INH_15") (pintype "bidirectional"))
      (node (ref "U16") (pin "8") (pinfunction "GND_8") (pintype "bidirectional"))
      (node (ref "U17") (pin "15") (pinfunction "C_INH_15") (pintype "bidirectional"))
      (node (ref "U17") (pin "8") (pinfunction "GND_8") (pintype "bidirectional"))
      (node (ref "U18") (pin "15") (pinfunction "C_INH_15") (pintype "bidirectional"))
      (node (ref "U18") (pin "8") (pinfunction "GND_8") (pintype "bidirectional"))
      (node (ref "U19") (pin "15") (pinfunction "C_INH_15") (pintype "bidirectional"))
      (node (ref "U19") (pin "8") (pinfunction "GND_8") (pintype "bidirectional"))
      (node (ref "U2") (pin "2") (pinfunction "A1_2") (pintype "bidirectional"))
      (node (ref "U2") (pin "3") (pinfunction "A2_3") (pintype "bidirectional"))
      (node (ref "U2") (pin "4") (pinfunction "GND_4") (pintype "bidirectional"))
      (node (ref "U2") (pin "7") (pinfunction "WP_7") (pintype "bidirectional"))
      (node (ref "U20") (pin "15") (pinfunction "C_INH_15") (pintype "bidirectional"))
      (node (ref "U20") (pin "8") (pinfunction "GND_8") (pintype "bidirectional"))
      (node (ref "U21") (pin "15") (pinfunction "C_INH_15") (pintype "bidirectional"))
      (node (ref "U21") (pin "8") (pinfunction "GND_8") (pintype "bidirectional"))
      (node (ref "U22") (pin "15") (pinfunction "C_INH_15") (pintype "bidirectional"))
      (node (ref "U22") (pin "8") (pinfunction "GND_8") (pintype "bidirectional"))
      (node (ref "U23") (pin "15") (pinfunction "C_INH_15") (pintype "bidirectional"))
      (node (ref "U23") (pin "8") (pinfunction "GND_8") (pintype "bidirectional"))
      (node (ref "U24") (pin "15") (pinfunction "C_INH_15") (pintype "bidirectional"))
      (node (ref "U24") (pin "8") (pinfunction "GND_8") (pintype "bidirectional"))
      (node (ref "U26") (pin "15") (pinfunction "C_INH_15") (pintype "bidirectional"))
      (node (ref "U26") (pin "8") (pinfunction "GND_8") (pintype "bidirectional"))
      (node (ref "U27") (pin "15") (pinfunction "C_INH_15") (pintype "bidirectional"))
      (node (ref "U27") (pin "8") (pinfunction "GND_8") (pintype "bidirectional"))
      (node (ref "U28") (pin "15") (pinfunction "C_INH_15") (pintype "bidirectional"))
      (node (ref "U28") (pin "8") (pinfunction "GND_8") (pintype "bidirectional"))
      (node (ref "U29") (pin "15") (pinfunction "C_INH_15") (pintype "bidirectional"))
      (node (ref "U29") (pin "8") (pinfunction "GND_8") (pintype "bidirectional"))
      (node (ref "U3") (pin "13") (pinfunction "GND_13") (pintype "bidirectional"))
      (node (ref "U3") (pin "5") (pinfunction "GND_5") (pintype "bidirectional"))
      (node (ref "U30") (pin "15") (pinfunction "C_INH_15") (pintype "bidirectional"))
      (node (ref "U30") (pin "8") (pinfunction "GND_8") (pintype "bidirectional"))
      (node (ref "U4") (pin "2") (pinfunction "GND_2") (pintype "bidirectional"))
      (node (ref "U5") (pin "1") (pinfunction "GND_1") (pintype "bidirectional"))
      (node (ref "U6") (pin "1") (pinfunction "GND_1") (pintype "bidirectional"))
      (node (ref "U7") (pin "2") (pinfunction "GND_2") (pintype "bidirectional"))
      (node (ref "U8") (pin "2") (pinfunction "GND_2") (pintype "bidirectional"))
      (node (ref "U9") (pin "P$7") (pinfunction "GND_P$7") (pintype "bidirectional"))
      (node (ref "USB_PWR") (pin "CATHODE") (pinfunction "CATHODE_CATHODE") (pintype "power_in"))
      (node (ref "X1") (pin "P$2") (pinfunction "GND_P$2") (pintype "bidirectional"))
      (node (ref "X1") (pin "P$4") (pinfunction "GND_P$4") (pintype "bidirectional"))
    )
    (net (code "173") (name "Net-(!MCLR!/VPP-PadP$1)") (class "Default")
      (node (ref "!MCLR!/VPP") (pin "P$1") (pinfunction "P$1_P$1") (pintype "bidirectional"))
      (node (ref "PICKIT3_IN") (pin "1") (pinfunction "1_1") (pintype "passive"))
    )
    (net (code "174") (name "Net-(EXT_PWR-PadANODE)") (class "Default")
      (node (ref "EXT_PWR") (pin "ANODE") (pinfunction "ANODE_ANODE") (pintype "power_in"))
      (node (ref "R30") (pin "P$1") (pinfunction "P$1_P$1") (pintype "passive"))
    )
    (net (code "175") (name "Net-(ICSPCLK-PadP$1)") (class "Default")
      (node (ref "ICSPCLK") (pin "P$1") (pinfunction "P$1_P$1") (pintype "bidirectional"))
      (node (ref "PICKIT3_IN") (pin "5") (pinfunction "5_5") (pintype "passive"))
    )
    (net (code "176") (name "Net-(ICSPDAT-PadP$1)") (class "Default")
      (node (ref "ICSPDAT") (pin "P$1") (pinfunction "P$1_P$1") (pintype "bidirectional"))
      (node (ref "PICKIT3_IN") (pin "4") (pinfunction "4_4") (pintype "passive"))
    )
    (net (code "177") (name "Net-(PGM-PadP$1)") (class "Default")
      (node (ref "PGM") (pin "P$1") (pinfunction "P$1_P$1") (pintype "bidirectional"))
      (node (ref "PICKIT3_IN") (pin "6") (pinfunction "6_6") (pintype "passive"))
    )
    (net (code "178") (name "Net-(PICKIT3_IN-Pad2)") (class "Default")
      (node (ref "PICKIT3_IN") (pin "2") (pinfunction "2_2") (pintype "passive"))
      (node (ref "VDD") (pin "P$1") (pinfunction "P$1_P$1") (pintype "bidirectional"))
    )
    (net (code "179") (name "Net-(PICKIT3_IN-Pad3)") (class "Default")
      (node (ref "PICKIT3_IN") (pin "3") (pinfunction "3_3") (pintype "passive"))
      (node (ref "VSS") (pin "P$1") (pinfunction "P$1_P$1") (pintype "bidirectional"))
    )
    (net (code "180") (name "Net-(R10-PadP$1)") (class "Default")
      (node (ref "R10") (pin "P$1") (pinfunction "P$1_P$1") (pintype "passive"))
      (node (ref "USB_PWR") (pin "ANODE") (pinfunction "ANODE_ANODE") (pintype "power_in"))
    )
    (net (code "181") (name "Net-(R11-PadP$1)") (class "Default")
      (node (ref "R11") (pin "P$1") (pinfunction "P$1_P$1") (pintype "passive"))
      (node (ref "TX") (pin "ANODE") (pinfunction "ANODE_ANODE") (pintype "power_in"))
    )
    (net (code "182") (name "Net-(R12-PadP$1)") (class "Default")
      (node (ref "R12") (pin "P$1") (pinfunction "P$1_P$1") (pintype "passive"))
      (node (ref "RX") (pin "ANODE") (pinfunction "ANODE_ANODE") (pintype "power_in"))
    )
    (net (code "183") (name "Net-(U3-USBDM)") (class "Default")
      (node (ref "R7") (pin "P$2") (pinfunction "P$2_P$2") (pintype "passive"))
      (node (ref "U3") (pin "9") (pinfunction "USBDM_9") (pintype "bidirectional"))
    )
    (net (code "184") (name "Net-(U3-USBDP)") (class "Default")
      (node (ref "R8") (pin "P$2") (pinfunction "P$2_P$2") (pintype "passive"))
      (node (ref "U3") (pin "8") (pinfunction "USBDP_8") (pintype "bidirectional"))
    )
    (net (code "185") (name "Net-(U4-I{slash}O1B)") (class "Default")
      (node (ref "C8") (pin "P$1") (pinfunction "P$1_P$1") (pintype "passive"))
      (node (ref "R8") (pin "P$1") (pinfunction "P$1_P$1") (pintype "passive"))
      (node (ref "U4") (pin "3") (pinfunction "I/O1B_3") (pintype "bidirectional"))
    )
    (net (code "186") (name "Net-(U4-I{slash}O2B)") (class "Default")
      (node (ref "C7") (pin "P$1") (pinfunction "P$1_P$1") (pintype "passive"))
      (node (ref "R7") (pin "P$1") (pinfunction "P$1_P$1") (pintype "passive"))
      (node (ref "U4") (pin "4") (pinfunction "I/O2B_4") (pintype "bidirectional"))
    )
    (net (code "187") (name "Net-(U10-GATE)") (class "Default")
      (node (ref "R18") (pin "2") (pinfunction "2_2") (pintype "passive"))
      (node (ref "U10") (pin "4") (pinfunction "GATE_4") (pintype "bidirectional"))
      (node (ref "U12") (pin "3") (pinfunction "COLLECTOR_3") (pintype "bidirectional"))
    )
    (net (code "188") (name "Net-(U11-GATE)") (class "Default")
      (node (ref "R20") (pin "2") (pinfunction "2_2") (pintype "passive"))
      (node (ref "U11") (pin "4") (pinfunction "GATE_4") (pintype "bidirectional"))
      (node (ref "U13") (pin "3") (pinfunction "COLLECTOR_3") (pintype "bidirectional"))
    )
    (net (code "189") (name "Net-(U12-BASE)") (class "Default")
      (node (ref "R19") (pin "2") (pinfunction "2_2") (pintype "passive"))
      (node (ref "U12") (pin "1") (pinfunction "BASE_1") (pintype "bidirectional"))
    )
    (net (code "190") (name "Net-(U13-BASE)") (class "Default")
      (node (ref "R21") (pin "2") (pinfunction "2_2") (pintype "passive"))
      (node (ref "U13") (pin "1") (pinfunction "BASE_1") (pintype "bidirectional"))
    )
    (net (code "191") (name "Net-(U14-Q7S)") (class "Default")
      (node (ref "U14") (pin "9") (pinfunction "Q7S_9") (pintype "bidirectional"))
      (node (ref "U15") (pin "14") (pinfunction "DS_14") (pintype "bidirectional"))
    )
    (net (code "192") (name "Net-(U16-SER)") (class "Default")
      (node (ref "U16") (pin "10") (pinfunction "SER_10") (pintype "bidirectional"))
      (node (ref "U17") (pin "9") (pinfunction "QH_9") (pintype "bidirectional"))
    )
    (net (code "193") (name "Net-(U17-SER)") (class "Default")
      (node (ref "U17") (pin "10") (pinfunction "SER_10") (pintype "bidirectional"))
      (node (ref "U18") (pin "9") (pinfunction "QH_9") (pintype "bidirectional"))
    )
    (net (code "194") (name "Net-(U18-SER)") (class "Default")
      (node (ref "U18") (pin "10") (pinfunction "SER_10") (pintype "bidirectional"))
      (node (ref "U19") (pin "9") (pinfunction "QH_9") (pintype "bidirectional"))
    )
    (net (code "195") (name "Net-(U19-SER)") (class "Default")
      (node (ref "U19") (pin "10") (pinfunction "SER_10") (pintype "bidirectional"))
      (node (ref "U20") (pin "9") (pinfunction "QH_9") (pintype "bidirectional"))
    )
    (net (code "196") (name "Net-(U20-SER)") (class "Default")
      (node (ref "U20") (pin "10") (pinfunction "SER_10") (pintype "bidirectional"))
      (node (ref "U21") (pin "9") (pinfunction "QH_9") (pintype "bidirectional"))
    )
    (net (code "197") (name "Net-(U21-SER)") (class "Default")
      (node (ref "U21") (pin "10") (pinfunction "SER_10") (pintype "bidirectional"))
      (node (ref "U22") (pin "9") (pinfunction "QH_9") (pintype "bidirectional"))
    )
    (net (code "198") (name "Net-(U22-SER)") (class "Default")
      (node (ref "U22") (pin "10") (pinfunction "SER_10") (pintype "bidirectional"))
      (node (ref "U23") (pin "9") (pinfunction "QH_9") (pintype "bidirectional"))
    )
    (net (code "199") (name "Net-(U23-SER)") (class "Default")
      (node (ref "U23") (pin "10") (pinfunction "SER_10") (pintype "bidirectional"))
      (node (ref "U24") (pin "9") (pinfunction "QH_9") (pintype "bidirectional"))
    )
    (net (code "200") (name "Net-(U24-D0)") (class "Default")
      (node (ref "R84") (pin "P$2") (pinfunction "P$2_P$2") (pintype "passive"))
      (node (ref "R92") (pin "P$1") (pinfunction "P$1_P$1") (pintype "passive"))
      (node (ref "U24") (pin "11") (pinfunction "D0_11") (pintype "bidirectional"))
    )
    (net (code "201") (name "Net-(U24-D1)") (class "Default")
      (node (ref "R83") (pin "P$2") (pinfunction "P$2_P$2") (pintype "passive"))
      (node (ref "R91") (pin "P$1") (pinfunction "P$1_P$1") (pintype "passive"))
      (node (ref "U24") (pin "12") (pinfunction "D1_12") (pintype "bidirectional"))
    )
    (net (code "202") (name "Net-(U24-D2)") (class "Default")
      (node (ref "R82") (pin "P$2") (pinfunction "P$2_P$2") (pintype "passive"))
      (node (ref "R90") (pin "P$1") (pinfunction "P$1_P$1") (pintype "passive"))
      (node (ref "U24") (pin "13") (pinfunction "D2_13") (pintype "bidirectional"))
    )
    (net (code "203") (name "Net-(U24-D3)") (class "Default")
      (node (ref "R81") (pin "P$2") (pinfunction "P$2_P$2") (pintype "passive"))
      (node (ref "R89") (pin "P$1") (pinfunction "P$1_P$1") (pintype "passive"))
      (node (ref "U24") (pin "14") (pinfunction "D3_14") (pintype "bidirectional"))
    )
    (net (code "204") (name "Net-(U24-D4)") (class "Default")
      (node (ref "R80") (pin "P$2") (pinfunction "P$2_P$2") (pintype "passive"))
      (node (ref "R88") (pin "P$1") (pinfunction "P$1_P$1") (pintype "passive"))
      (node (ref "U24") (pin "3") (pinfunction "D4_3") (pintype "bidirectional"))
    )
    (net (code "205") (name "Net-(U24-D5)") (class "Default")
      (node (ref "R79") (pin "P$2") (pinfunction "P$2_P$2") (pintype "passive"))
      (node (ref "R87") (pin "P$1") (pinfunction "P$1_P$1") (pintype "passive"))
      (node (ref "U24") (pin "4") (pinfunction "D5_4") (pintype "bidirectional"))
    )
    (net (code "206") (name "Net-(U24-D6)") (class "Default")
      (node (ref "R78") (pin "P$2") (pinfunction "P$2_P$2") (pintype "passive"))
      (node (ref "R86") (pin "P$1") (pinfunction "P$1_P$1") (pintype "passive"))
      (node (ref "U24") (pin "5") (pinfunction "D6_5") (pintype "bidirectional"))
    )
    (net (code "207") (name "Net-(U24-D7)") (class "Default")
      (node (ref "R77") (pin "P$2") (pinfunction "P$2_P$2") (pintype "passive"))
      (node (ref "R85") (pin "P$1") (pinfunction "P$1_P$1") (pintype "passive"))
      (node (ref "U24") (pin "6") (pinfunction "D7_6") (pintype "bidirectional"))
    )
    (net (code "208") (name "Net-(U24-SER)") (class "Default")
      (node (ref "U24") (pin "10") (pinfunction "SER_10") (pintype "bidirectional"))
      (node (ref "U26") (pin "9") (pinfunction "QH_9") (pintype "bidirectional"))
    )
    (net (code "209") (name "Net-(U26-SER)") (class "Default")
      (node (ref "U26") (pin "10") (pinfunction "SER_10") (pintype "bidirectional"))
      (node (ref "U27") (pin "9") (pinfunction "QH_9") (pintype "bidirectional"))
    )
    (net (code "210") (name "Net-(U27-SER)") (class "Default")
      (node (ref "U27") (pin "10") (pinfunction "SER_10") (pintype "bidirectional"))
      (node (ref "U28") (pin "9") (pinfunction "QH_9") (pintype "bidirectional"))
    )
    (net (code "211") (name "Net-(U28-SER)") (class "Default")
      (node (ref "U28") (pin "10") (pinfunction "SER_10") (pintype "bidirectional"))
      (node (ref "U29") (pin "9") (pinfunction "QH_9") (pintype "bidirectional"))
    )
    (net (code "212") (name "Net-(U29-SER)") (class "Default")
      (node (ref "U29") (pin "10") (pinfunction "SER_10") (pintype "bidirectional"))
      (node (ref "U30") (pin "9") (pinfunction "QH_9") (pintype "bidirectional"))
    )
    (net (code "213") (name "VIN") (class "Default")
      (node (ref "C13") (pin "P$1") (pinfunction "P$1_P$1") (pintype "passive"))
      (node (ref "C15") (pin "P$1") (pinfunction "P$1_P$1") (pintype "passive"))
      (node (ref "C17") (pin "P$1") (pinfunction "P$1_P$1") (pintype "passive"))
      (node (ref "C19") (pin "P$1") (pinfunction "P$1_P$1") (pintype "passive"))
      (node (ref "J2") (pin "PIN") (pinfunction "PIN_PIN") (pintype "power_in"))
      (node (ref "R14") (pin "1") (pinfunction "1_1") (pintype "passive"))
      (node (ref "TVS1") (pin "P$1") (pinfunction "P$1_P$1") (pintype "bidirectional"))
      (node (ref "U5") (pin "3") (pinfunction "IN_3") (pintype "bidirectional"))
      (node (ref "U6") (pin "3") (pinfunction "IN_3") (pintype "bidirectional"))
      (node (ref "U7") (pin "3") (pinfunction "VIN+_3") (pintype "bidirectional"))
    )
    (net (code "214") (name "unconnected-(J1-ID-Pad4)") (class "Default")
      (node (ref "J1") (pin "4") (pinfunction "ID_4") (pintype "bidirectional"))
    )
    (net (code "215") (name "unconnected-(U2-A0-Pad1)") (class "Default")
      (node (ref "U2") (pin "1") (pinfunction "A0_1") (pintype "bidirectional"))
    )
    (net (code "216") (name "unconnected-(U3-CBUS2-Pad7)") (class "Default")
      (node (ref "U3") (pin "7") (pinfunction "CBUS2_7") (pintype "bidirectional"))
    )
    (net (code "217") (name "unconnected-(U3-~{CTS}-Pad6)") (class "Default")
      (node (ref "U3") (pin "6") (pinfunction "~{CTS}_6") (pintype "bidirectional"))
    )
    (net (code "218") (name "unconnected-(U9-A_3-PadP$4)") (class "Default")
      (node (ref "U9") (pin "P$4") (pinfunction "A_3_P$4") (pintype "bidirectional"))
    )
    (net (code "219") (name "unconnected-(U15-Q7S-Pad9)") (class "Default")
      (node (ref "U15") (pin "9") (pinfunction "Q7S_9") (pintype "bidirectional"))
    )
    (net (code "220") (name "unconnected-(U16-D7-Pad6)") (class "Default")
      (node (ref "U16") (pin "6") (pinfunction "D7_6") (pintype "bidirectional"))
    )
    (net (code "221") (name "unconnected-(U16-QH'-Pad7)") (class "Default")
      (node (ref "U16") (pin "7") (pinfunction "QH'_7") (pintype "bidirectional"))
    )
    (net (code "222") (name "unconnected-(U17-QH'-Pad7)") (class "Default")
      (node (ref "U17") (pin "7") (pinfunction "QH'_7") (pintype "bidirectional"))
    )
    (net (code "223") (name "unconnected-(U18-QH'-Pad7)") (class "Default")
      (node (ref "U18") (pin "7") (pinfunction "QH'_7") (pintype "bidirectional"))
    )
    (net (code "224") (name "unconnected-(U19-QH'-Pad7)") (class "Default")
      (node (ref "U19") (pin "7") (pinfunction "QH'_7") (pintype "bidirectional"))
    )
    (net (code "225") (name "unconnected-(U20-QH'-Pad7)") (class "Default")
      (node (ref "U20") (pin "7") (pinfunction "QH'_7") (pintype "bidirectional"))
    )
    (net (code "226") (name "unconnected-(U21-QH'-Pad7)") (class "Default")
      (node (ref "U21") (pin "7") (pinfunction "QH'_7") (pintype "bidirectional"))
    )
    (net (code "227") (name "unconnected-(U22-QH'-Pad7)") (class "Default")
      (node (ref "U22") (pin "7") (pinfunction "QH'_7") (pintype "bidirectional"))
    )
    (net (code "228") (name "unconnected-(U23-QH'-Pad7)") (class "Default")
      (node (ref "U23") (pin "7") (pinfunction "QH'_7") (pintype "bidirectional"))
    )
    (net (code "229") (name "unconnected-(U24-QH'-Pad7)") (class "Default")
      (node (ref "U24") (pin "7") (pinfunction "QH'_7") (pintype "bidirectional"))
    )
    (net (code "230") (name "unconnected-(U26-D7-Pad6)") (class "Default")
      (node (ref "U26") (pin "6") (pinfunction "D7_6") (pintype "bidirectional"))
    )
    (net (code "231") (name "unconnected-(U26-QH'-Pad7)") (class "Default")
      (node (ref "U26") (pin "7") (pinfunction "QH'_7") (pintype "bidirectional"))
    )
    (net (code "232") (name "unconnected-(U27-D5-Pad4)") (class "Default")
      (node (ref "U27") (pin "4") (pinfunction "D5_4") (pintype "bidirectional"))
    )
    (net (code "233") (name "unconnected-(U27-D6-Pad5)") (class "Default")
      (node (ref "U27") (pin "5") (pinfunction "D6_5") (pintype "bidirectional"))
    )
    (net (code "234") (name "unconnected-(U27-D7-Pad6)") (class "Default")
      (node (ref "U27") (pin "6") (pinfunction "D7_6") (pintype "bidirectional"))
    )
    (net (code "235") (name "unconnected-(U27-QH'-Pad7)") (class "Default")
      (node (ref "U27") (pin "7") (pinfunction "QH'_7") (pintype "bidirectional"))
    )
    (net (code "236") (name "unconnected-(U28-QH'-Pad7)") (class "Default")
      (node (ref "U28") (pin "7") (pinfunction "QH'_7") (pintype "bidirectional"))
    )
    (net (code "237") (name "unconnected-(U29-QH'-Pad7)") (class "Default")
      (node (ref "U29") (pin "7") (pinfunction "QH'_7") (pintype "bidirectional"))
    )
    (net (code "238") (name "unconnected-(U30-D1-Pad12)") (class "Default")
      (node (ref "U30") (pin "12") (pinfunction "D1_12") (pintype "bidirectional"))
    )
    (net (code "239") (name "unconnected-(U30-D2-Pad13)") (class "Default")
      (node (ref "U30") (pin "13") (pinfunction "D2_13") (pintype "bidirectional"))
    )
    (net (code "240") (name "unconnected-(U30-D3-Pad14)") (class "Default")
      (node (ref "U30") (pin "14") (pinfunction "D3_14") (pintype "bidirectional"))
    )
    (net (code "241") (name "unconnected-(U30-D4-Pad3)") (class "Default")
      (node (ref "U30") (pin "3") (pinfunction "D4_3") (pintype "bidirectional"))
    )
    (net (code "242") (name "unconnected-(U30-D5-Pad4)") (class "Default")
      (node (ref "U30") (pin "4") (pinfunction "D5_4") (pintype "bidirectional"))
    )
    (net (code "243") (name "unconnected-(U30-D6-Pad5)") (class "Default")
      (node (ref "U30") (pin "5") (pinfunction "D6_5") (pintype "bidirectional"))
    )
    (net (code "244") (name "unconnected-(U30-D7-Pad6)") (class "Default")
      (node (ref "U30") (pin "6") (pinfunction "D7_6") (pintype "bidirectional"))
    )
    (net (code "245") (name "unconnected-(U30-QH'-Pad7)") (class "Default")
      (node (ref "U30") (pin "7") (pinfunction "QH'_7") (pintype "bidirectional"))
    )
    (net (code "246") (name "unconnected-(U30-SER-Pad10)") (class "Default")
      (node (ref "U30") (pin "10") (pinfunction "SER_10") (pintype "bidirectional"))
    )
  )
)
